# Titan_Servo_v1p01c.net
KiCad netlist of a schematic drawn in EAGLE
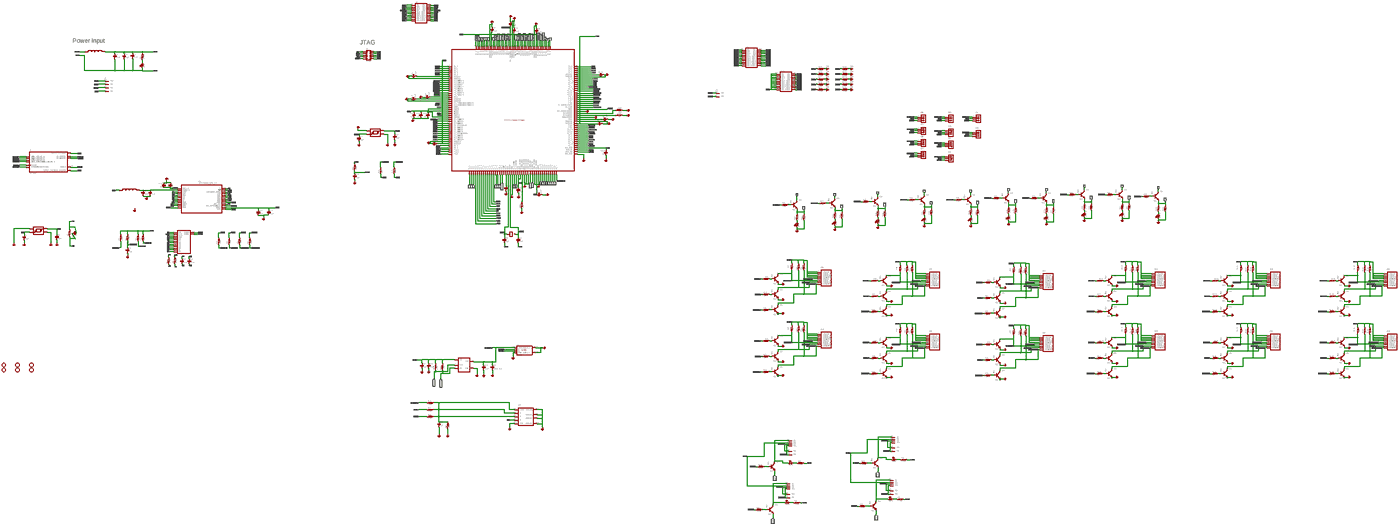
[diagram p0: schematic, sheet 1, overview]
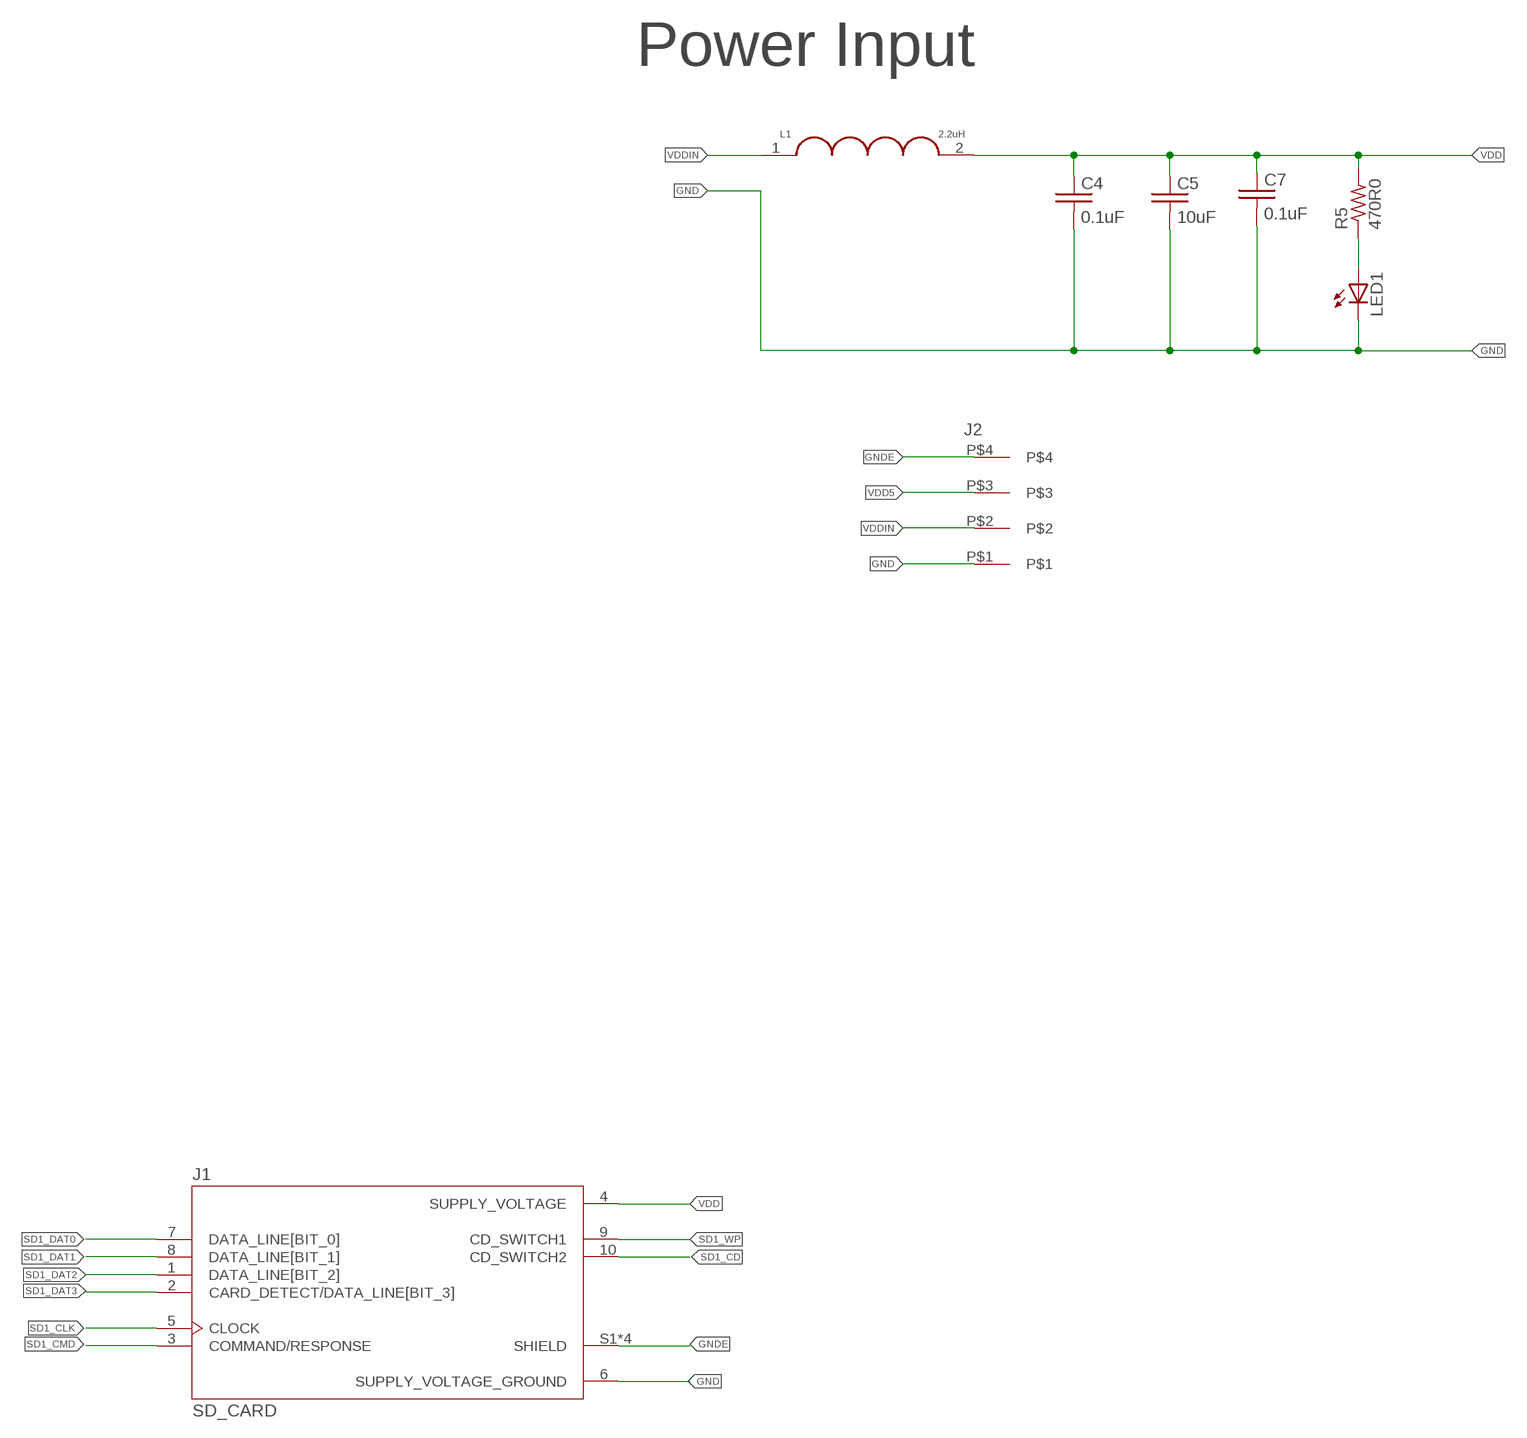
[diagram p1: schematic, sheet 1, part 1 of 9]
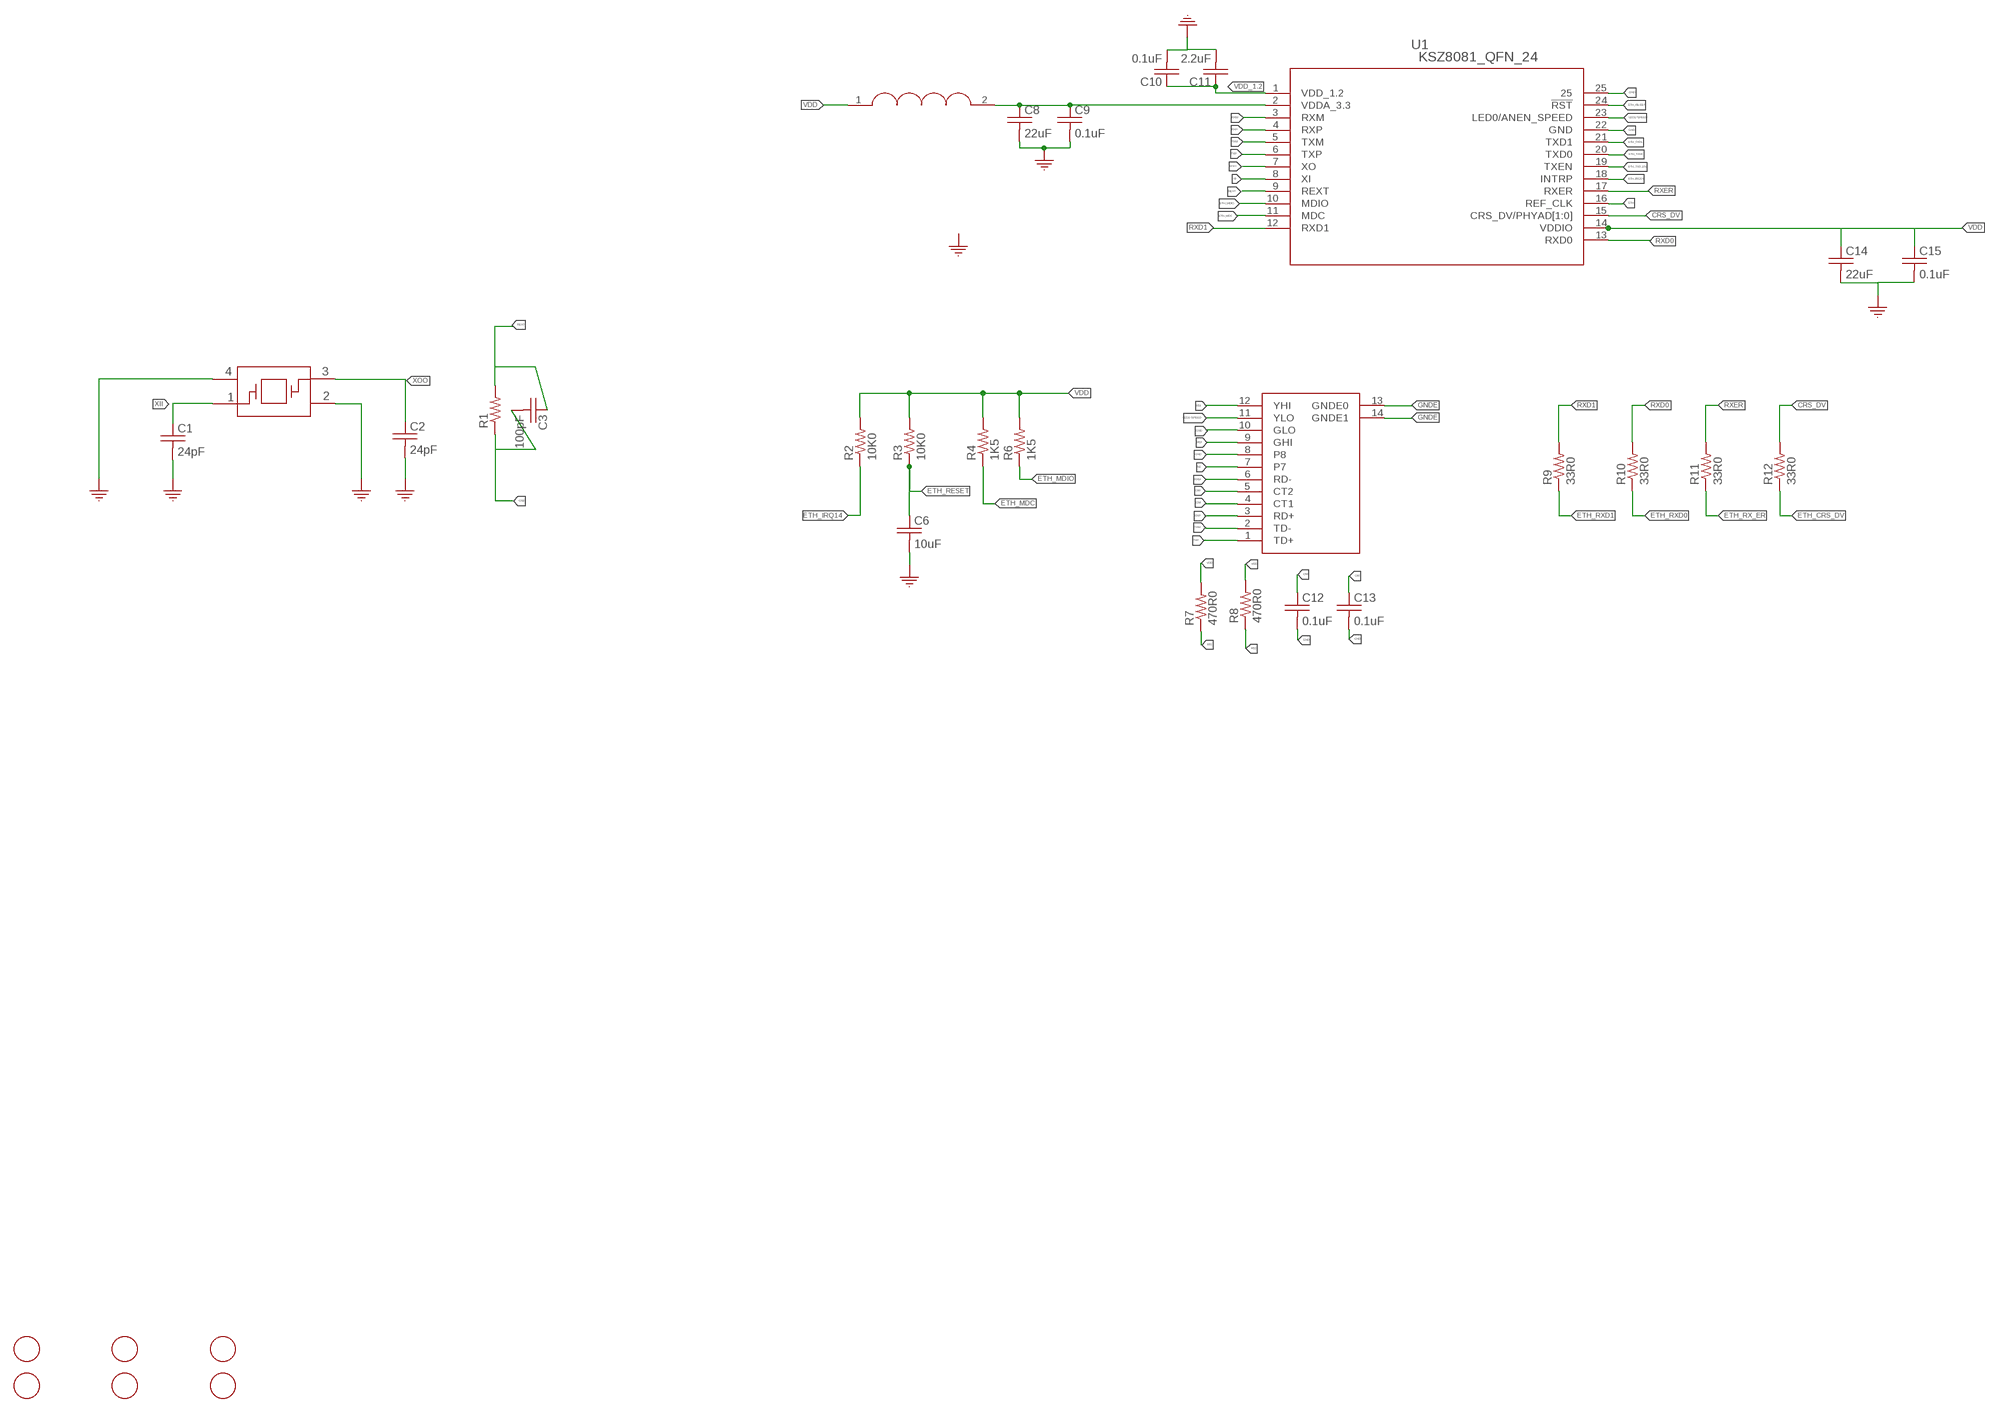
[diagram p2: schematic, sheet 1, part 2 of 9]
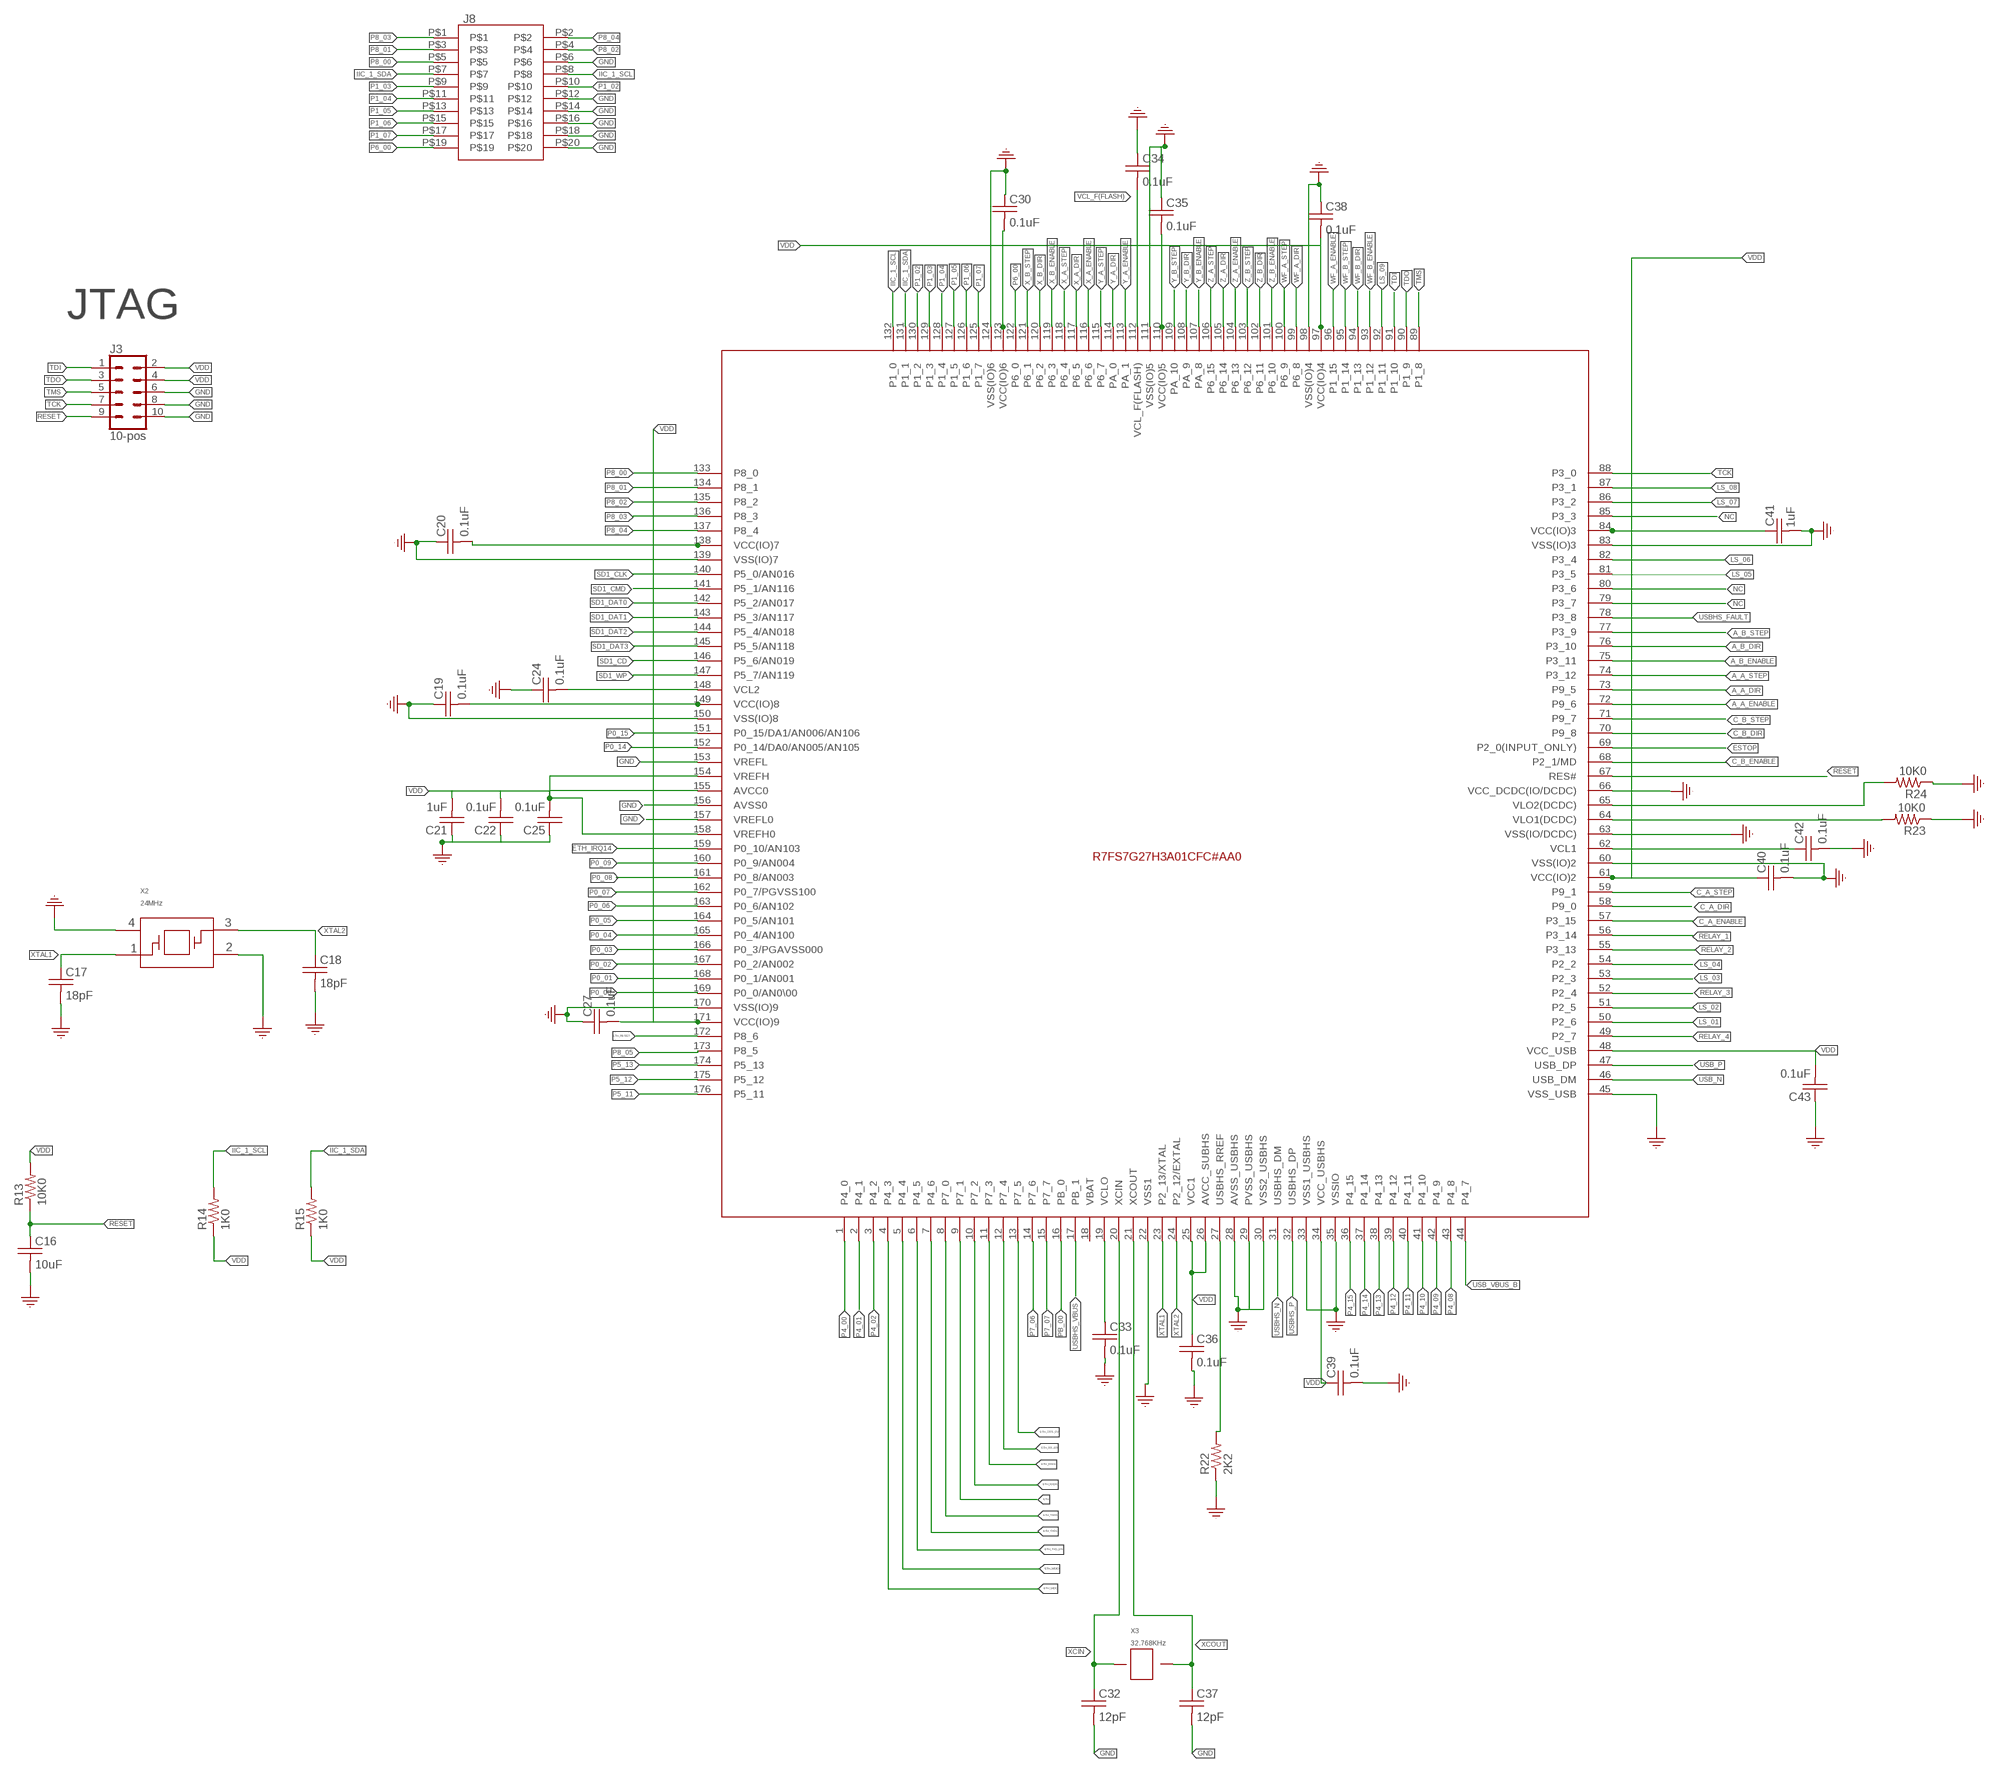
[diagram p3: schematic, sheet 1, part 3 of 9]
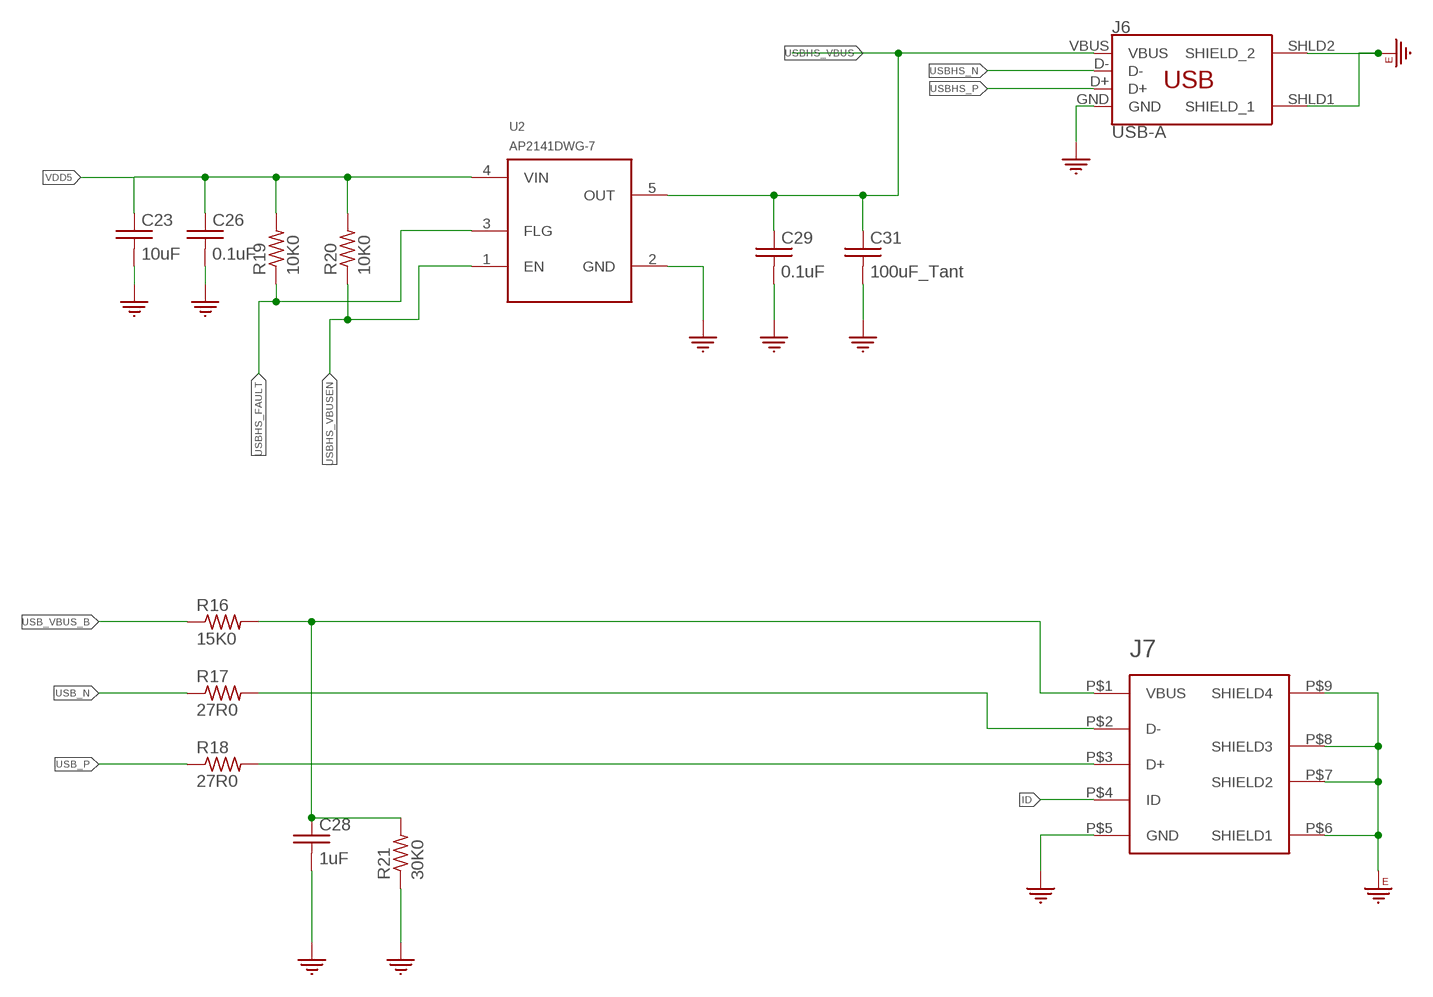
[diagram p4: schematic, sheet 1, part 4 of 9]
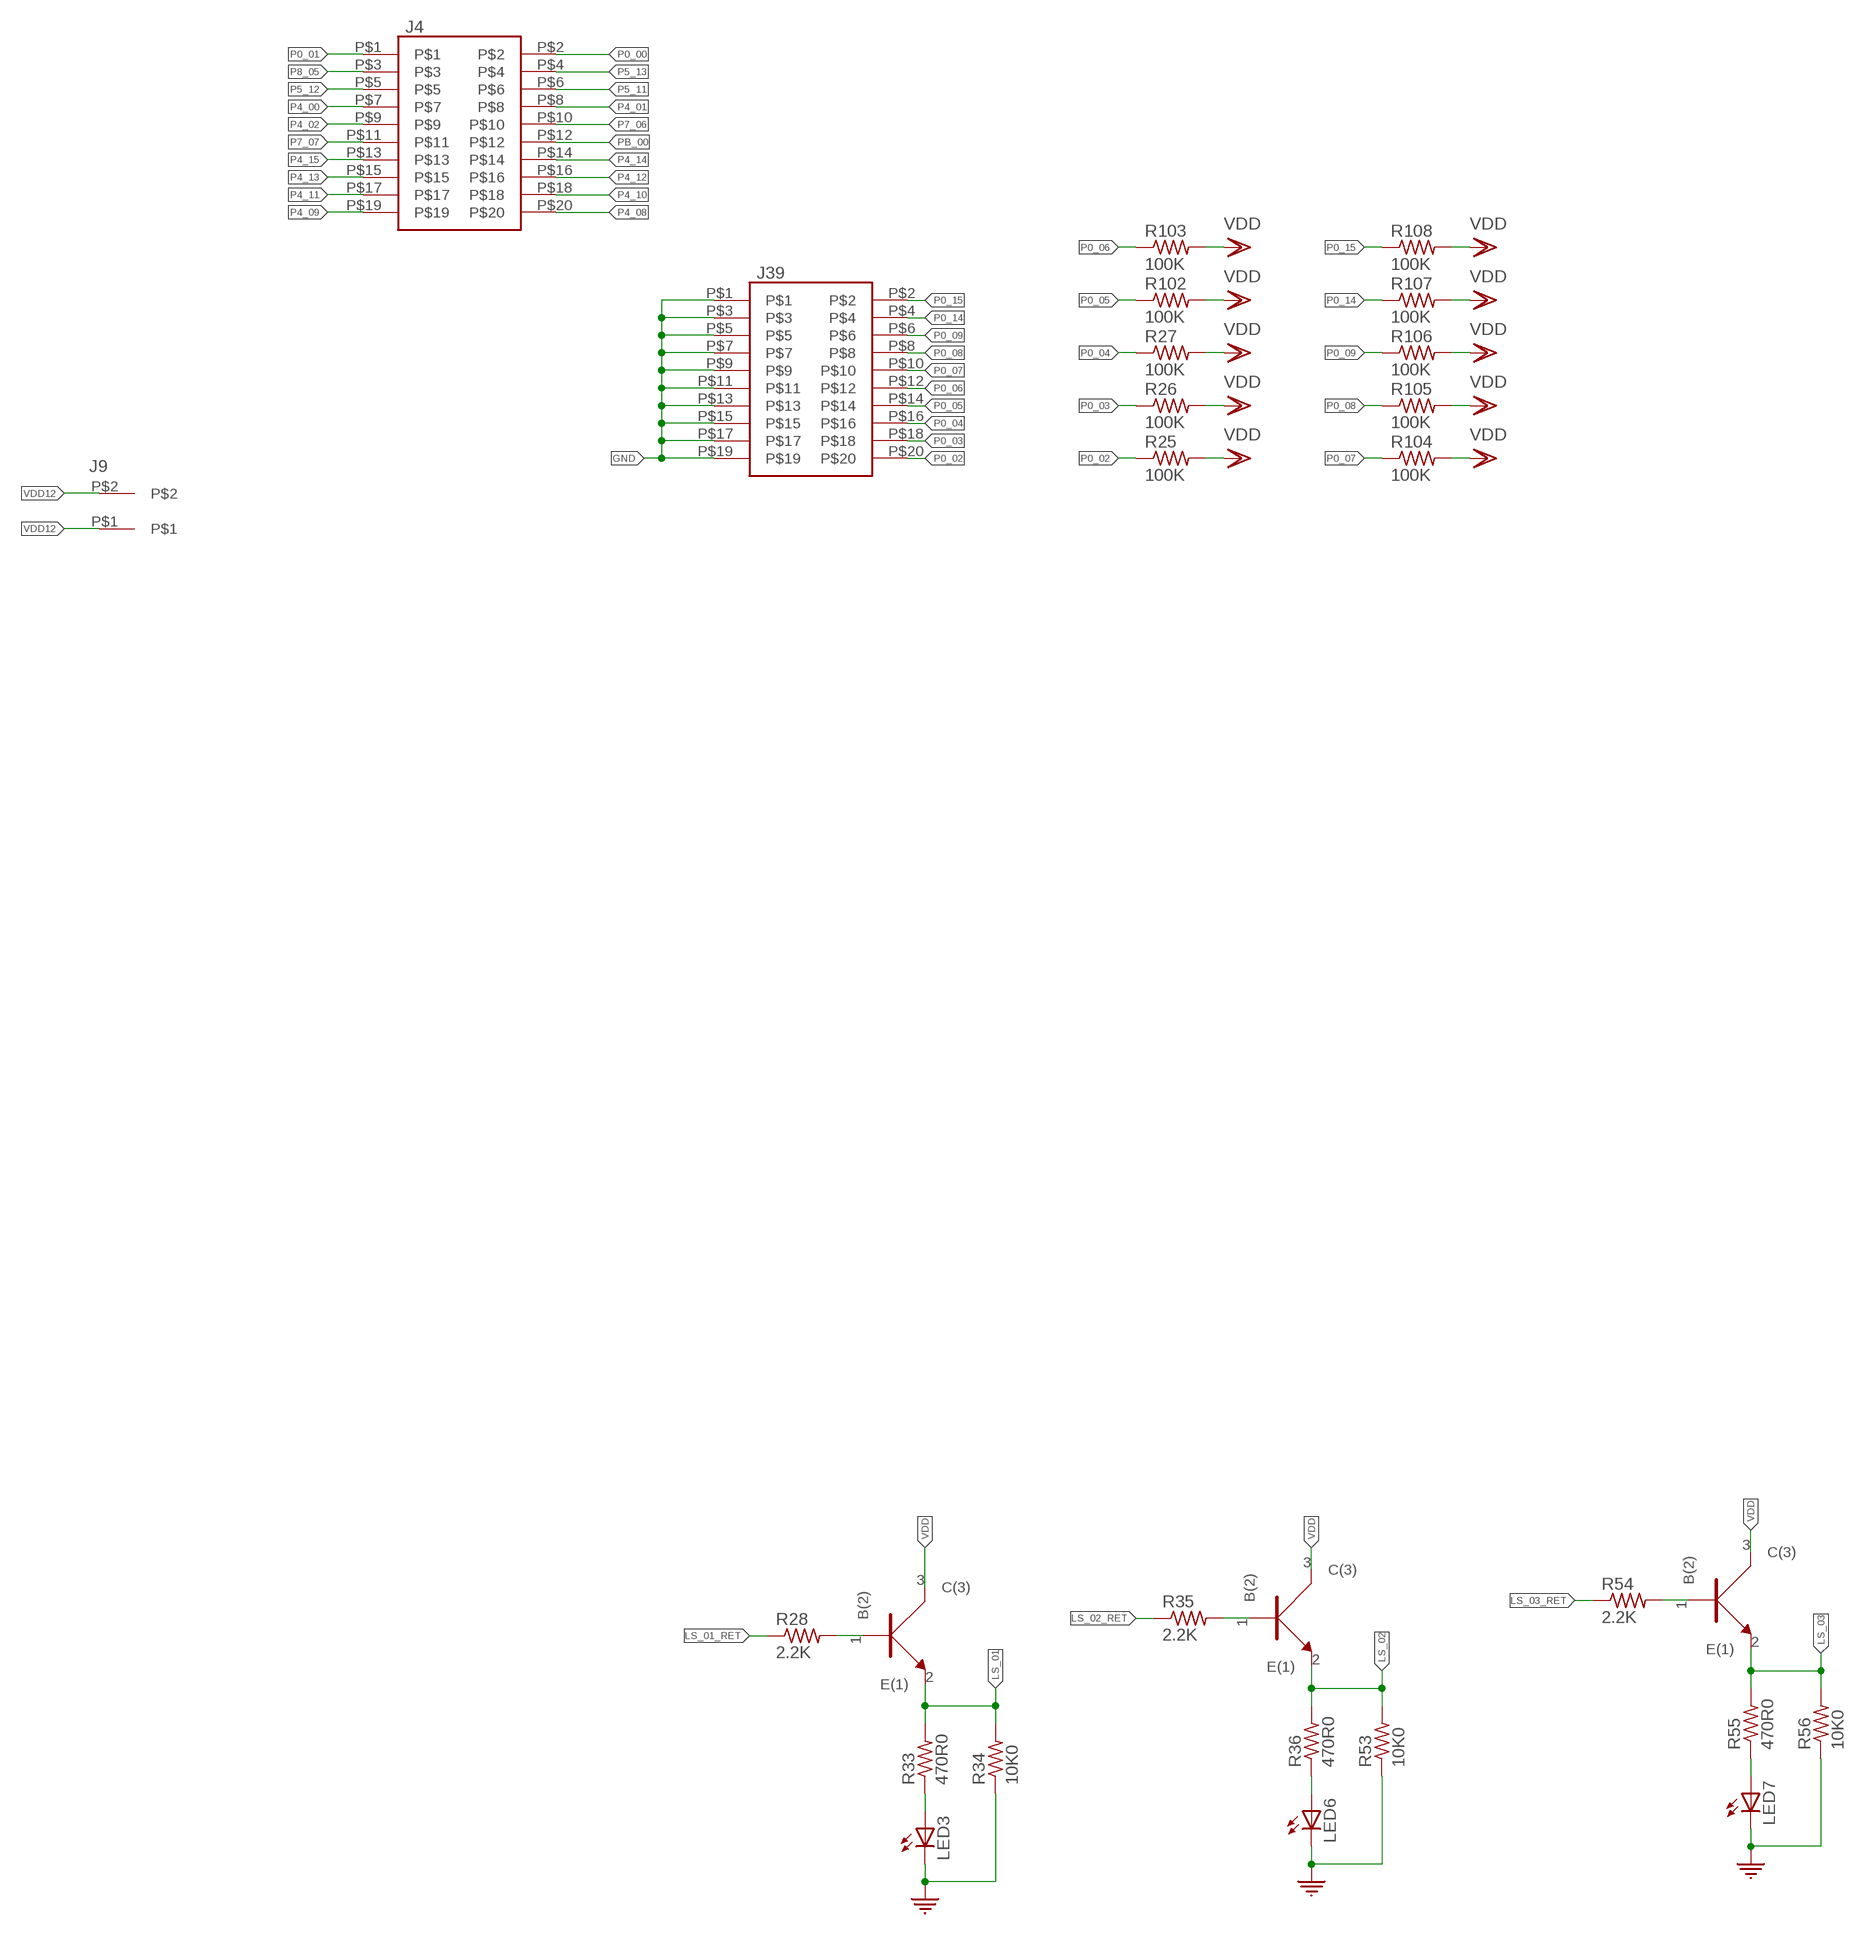
[diagram p5: schematic, sheet 1, part 5 of 9]
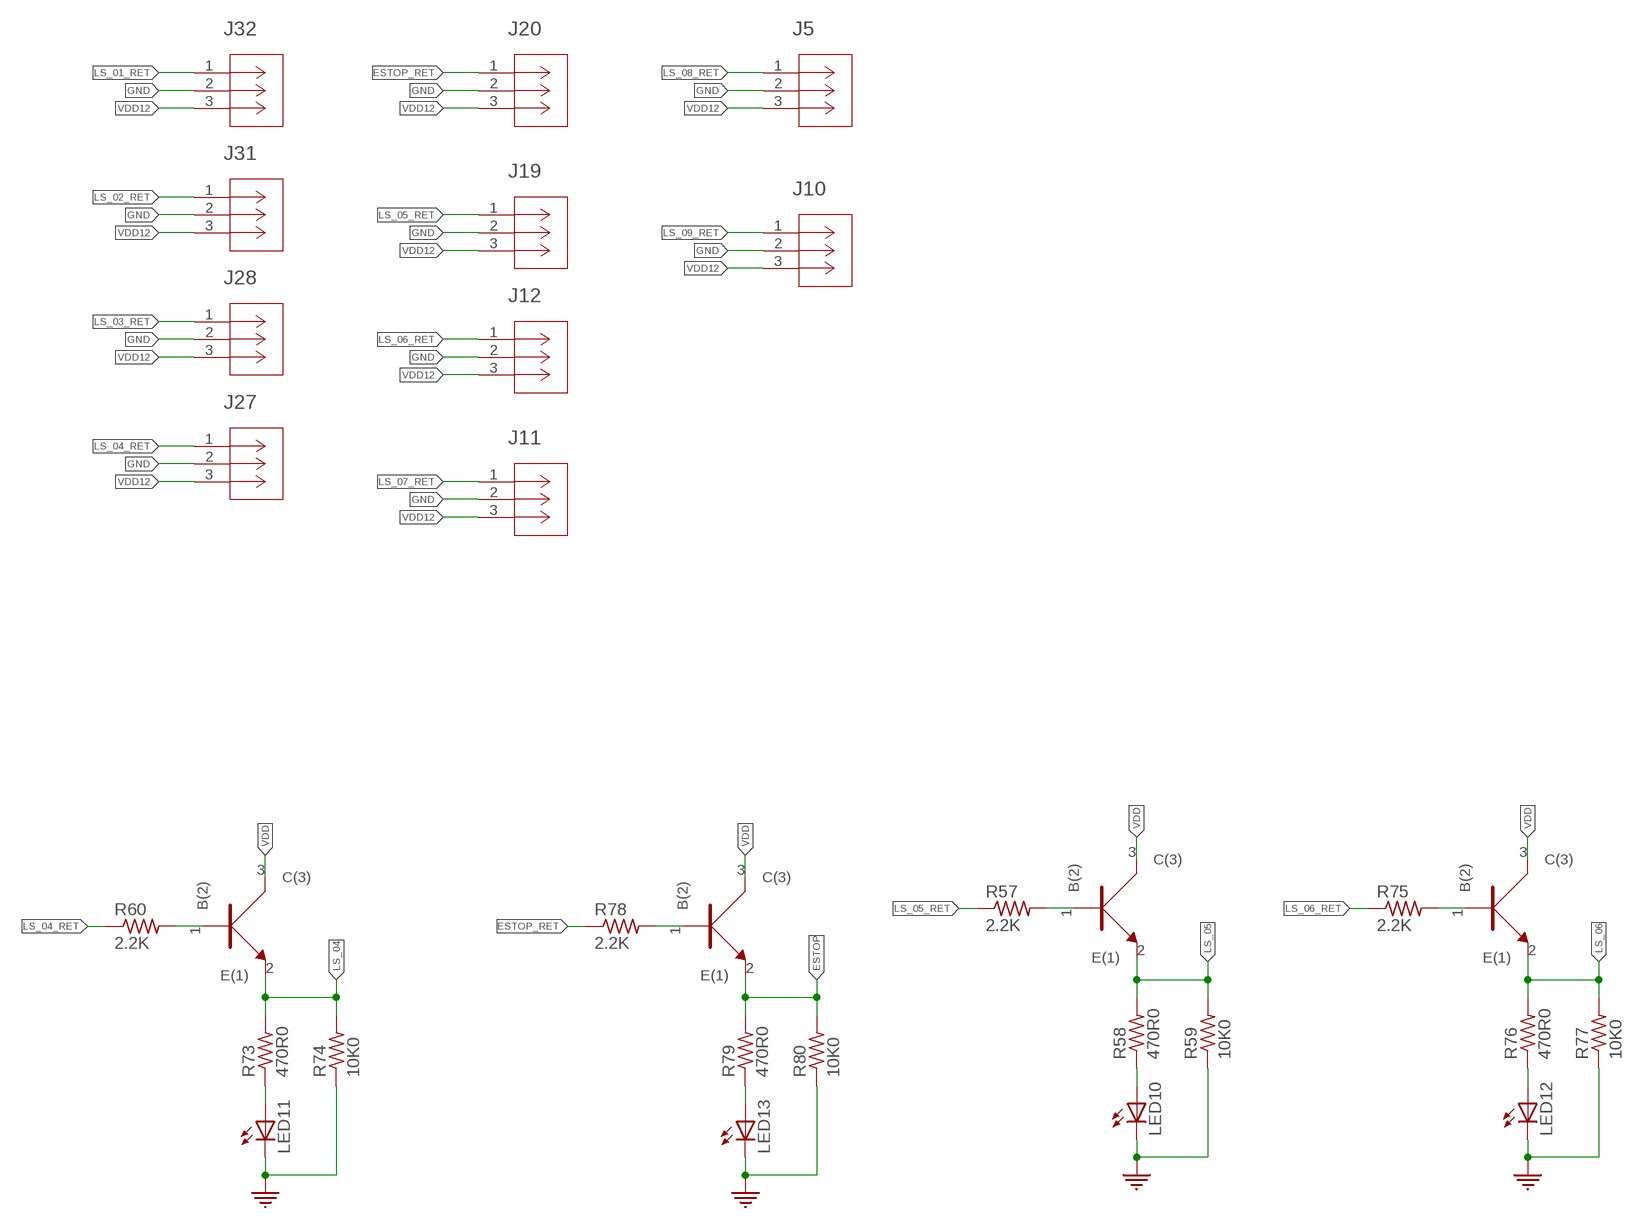
[diagram p6: schematic, sheet 1, part 6 of 9]
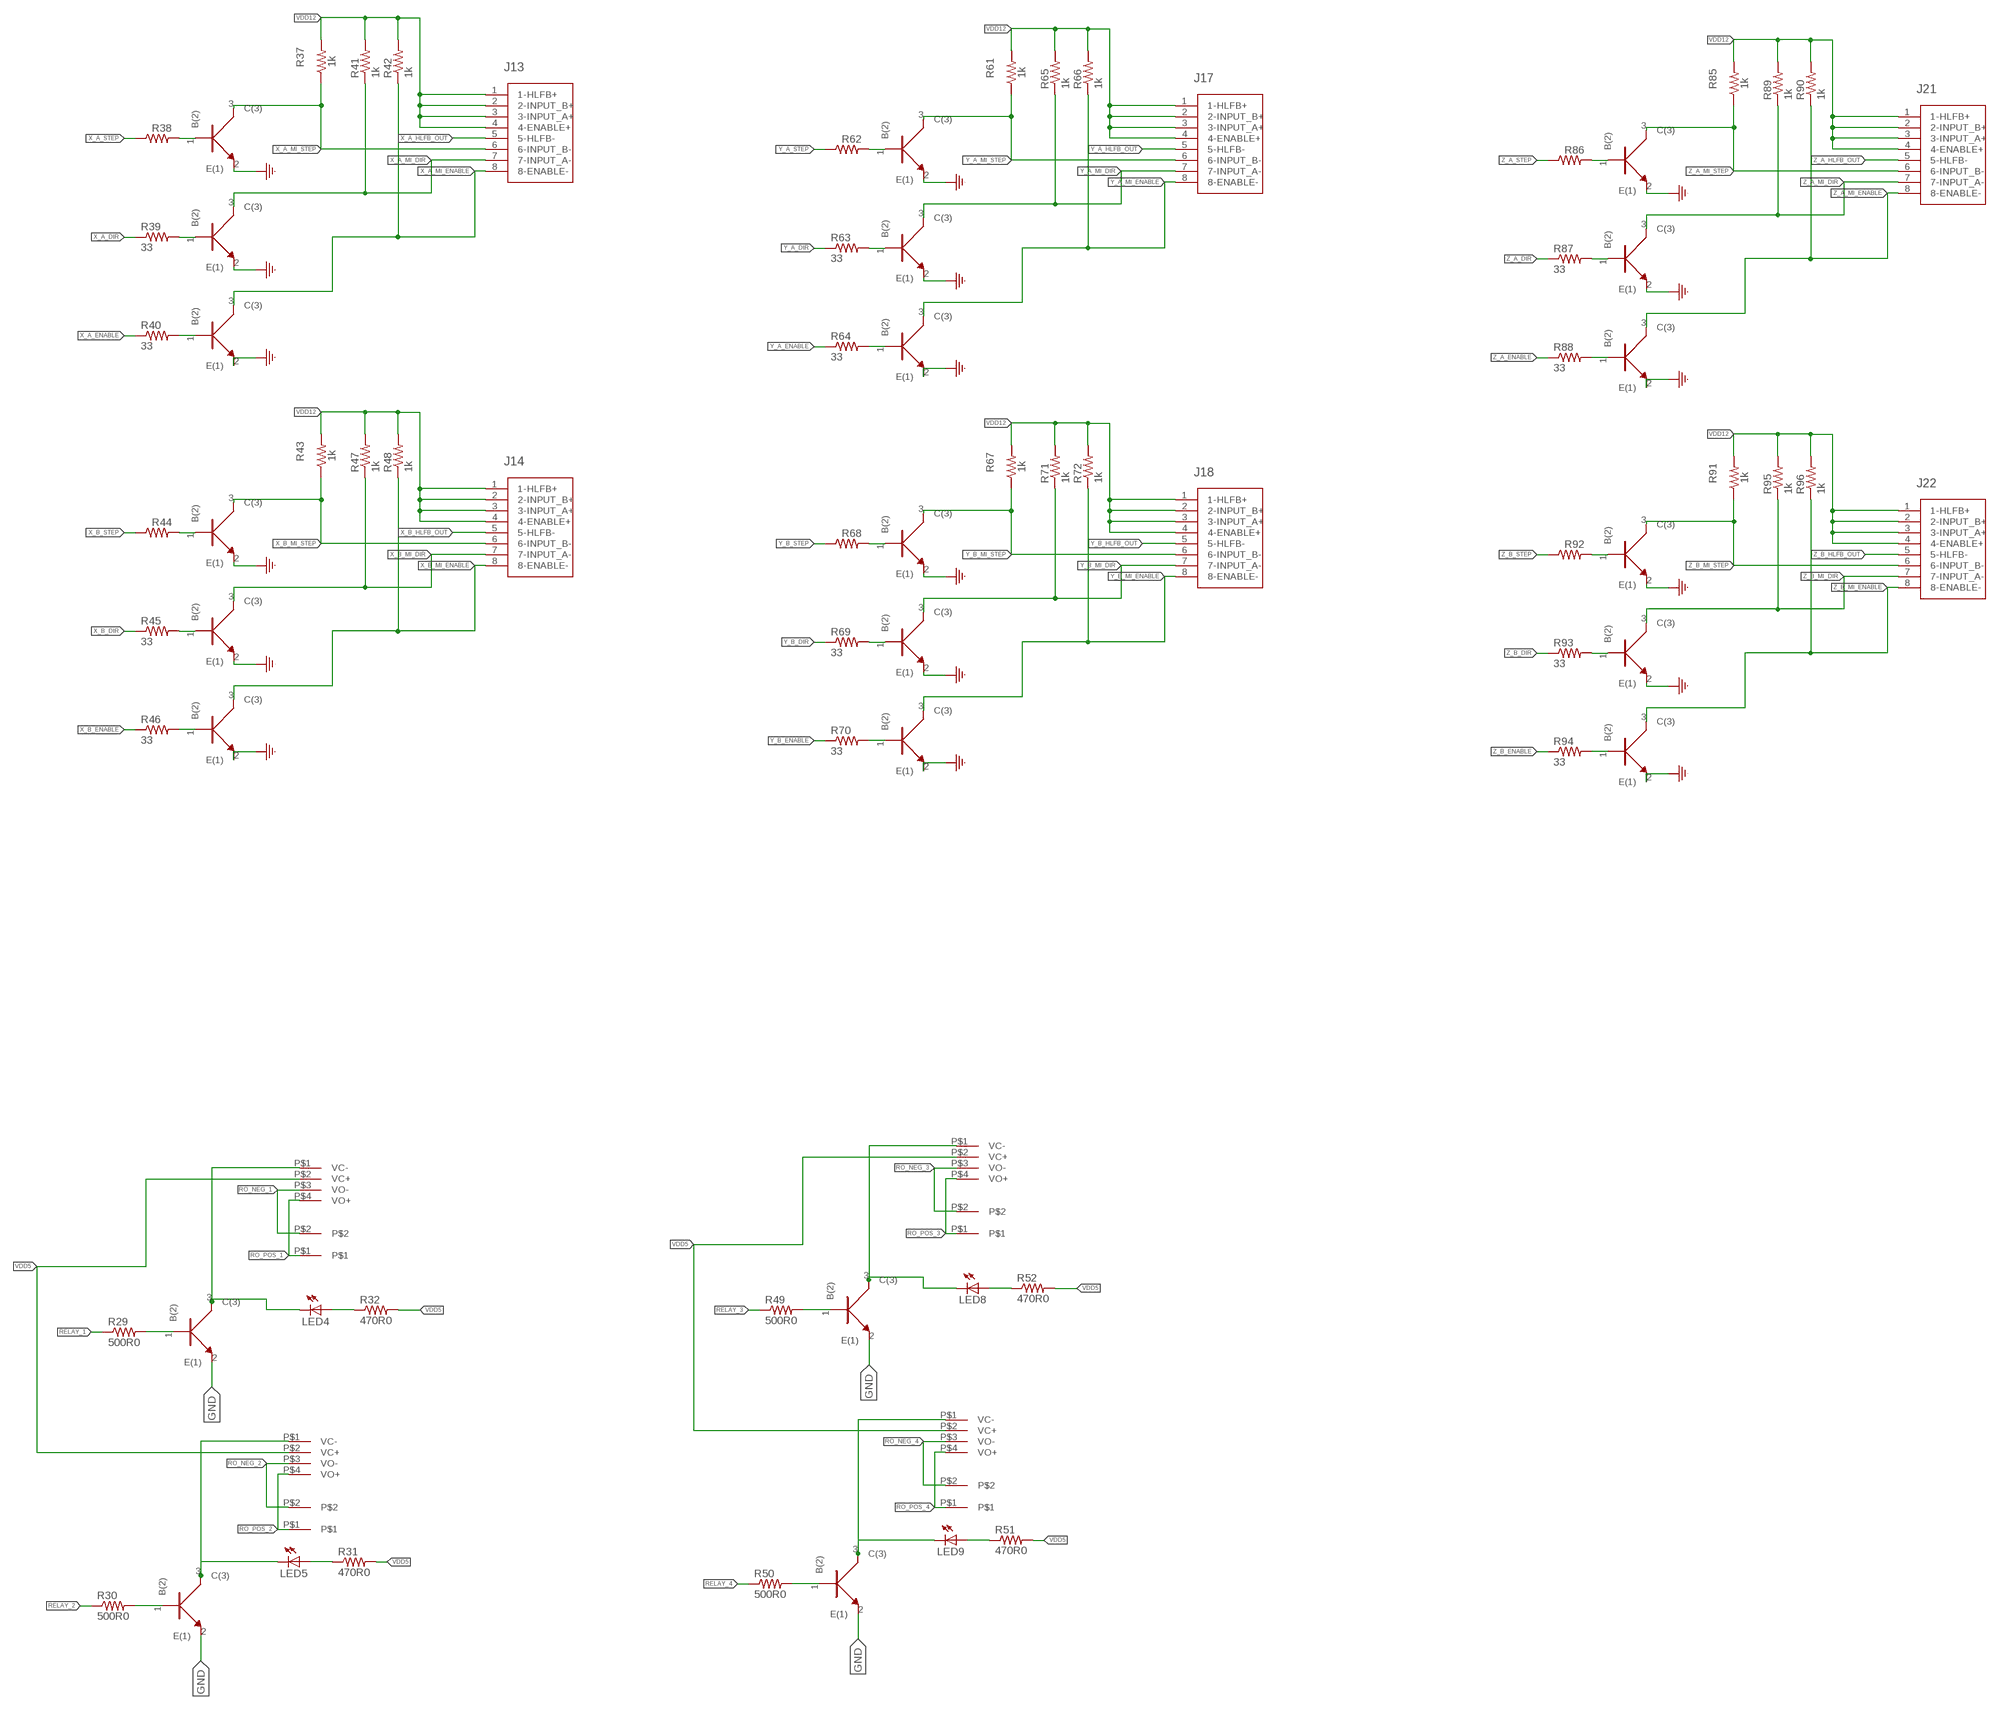
[diagram p7: schematic, sheet 1, part 7 of 9]
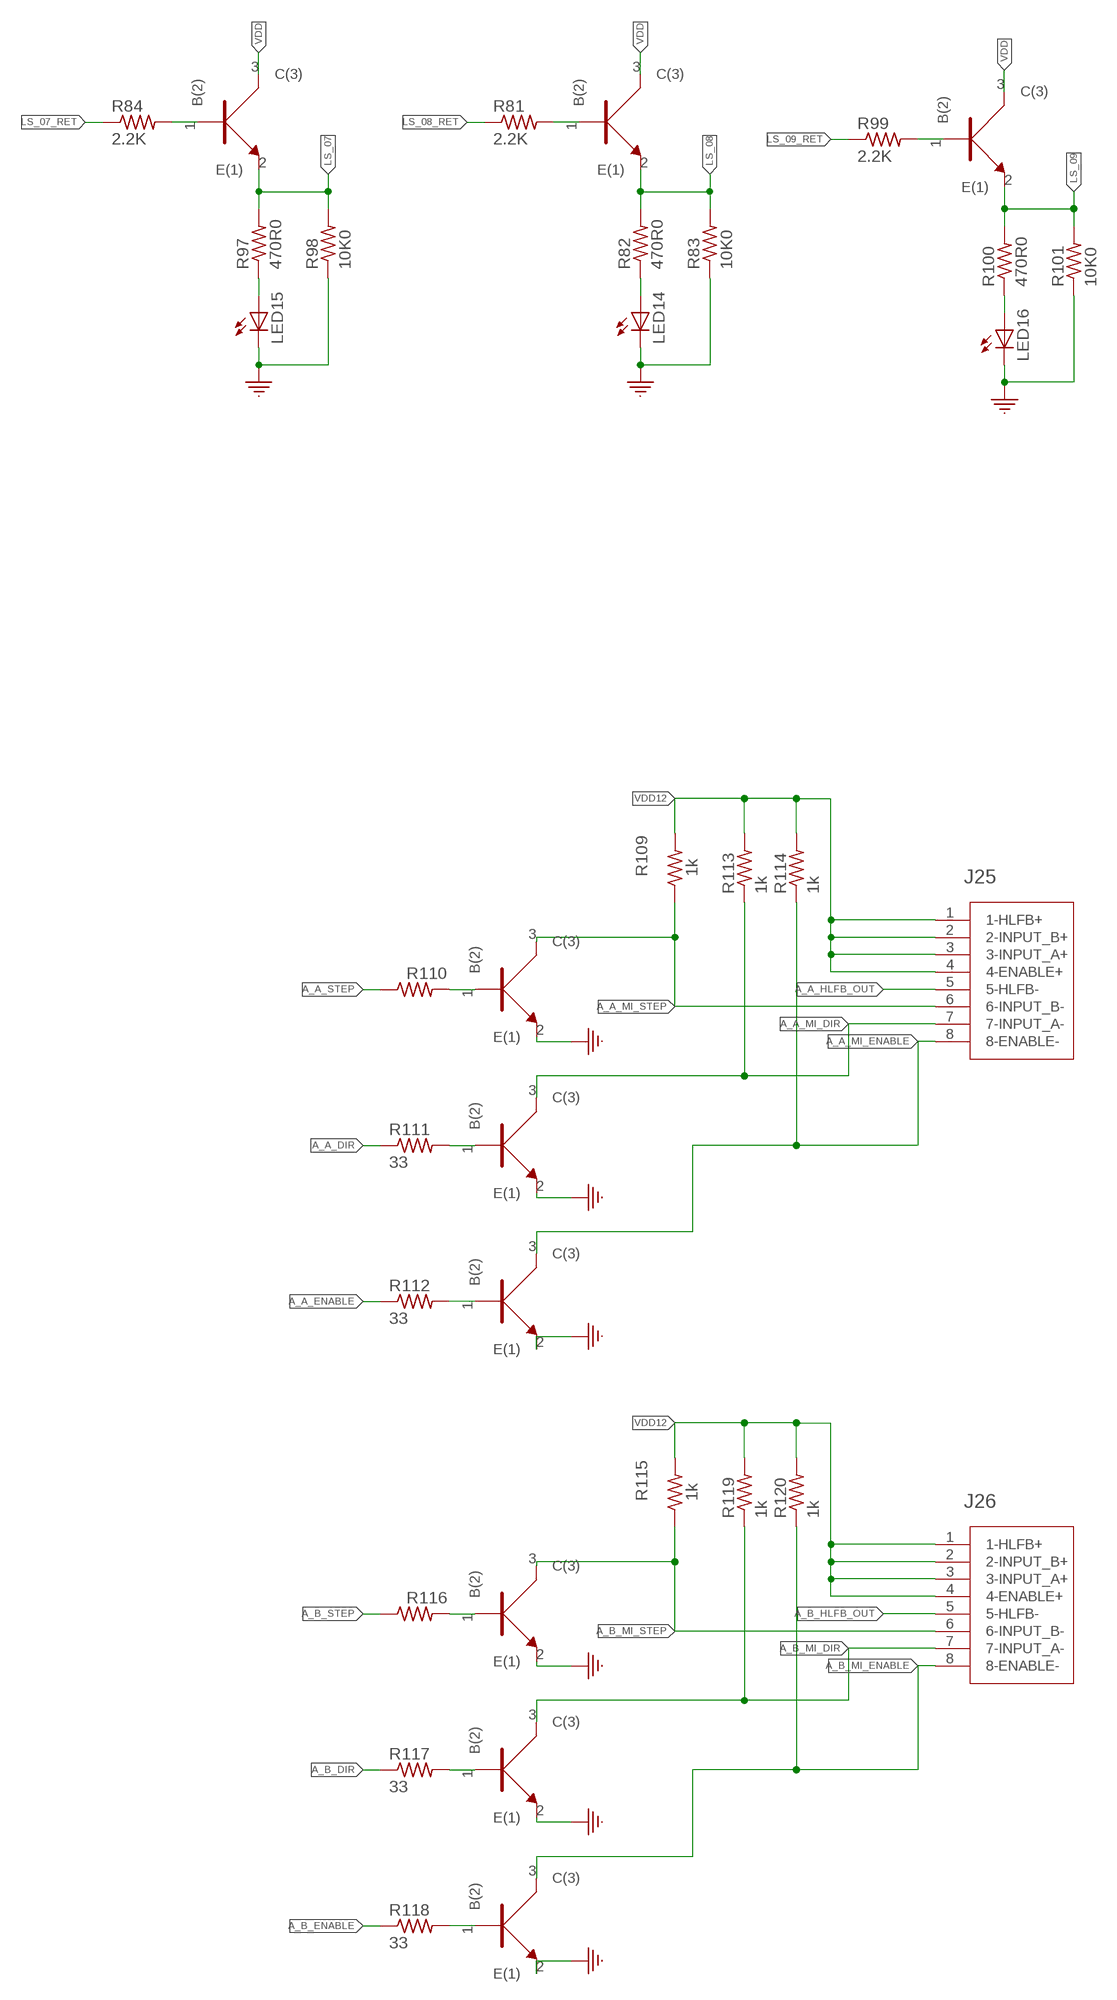
[diagram p8: schematic, sheet 1, part 8 of 9]
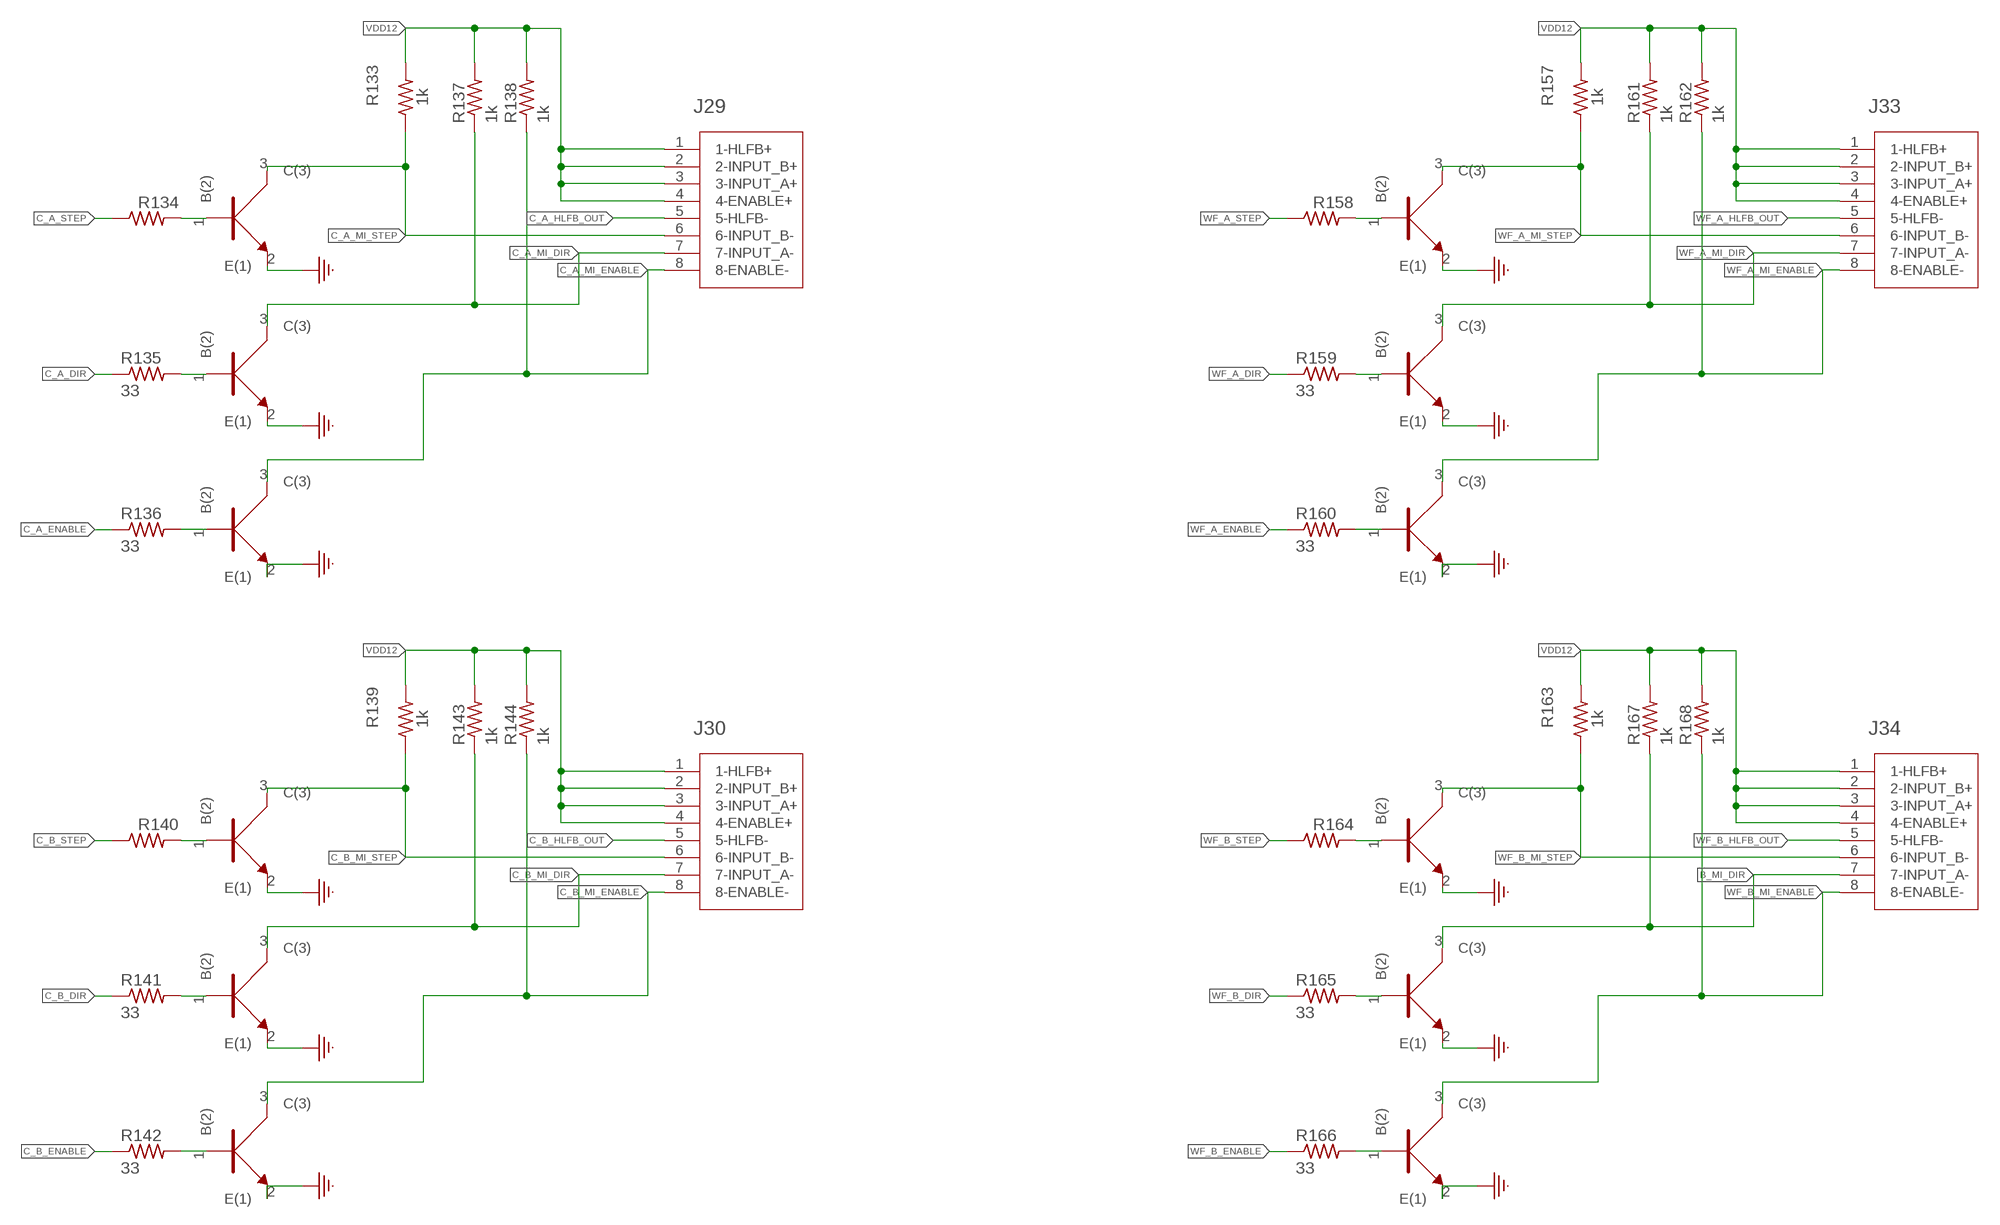
[diagram p9: schematic, sheet 1, part 9 of 9]

(export (version "E")
  (design (tool "Eeschema 10.0.6"))
  (components
    (comp (ref "AFID1")
      (value "FIDUCIAL_1MM")
      (footprint "eagle-import:FIDUCIAL_1MM")
      (libsource (lib "eagle-import") (part "FIDUCIAL_1MM"))
    )
    (comp (ref "AFID2")
      (value "FIDUCIAL_1MM")
      (footprint "eagle-import:FIDUCIAL_1MM")
      (libsource (lib "eagle-import") (part "FIDUCIAL_1MM"))
    )
    (comp (ref "AFID3")
      (value "FIDUCIAL_1MM")
      (footprint "eagle-import:FIDUCIAL_1MM")
      (libsource (lib "eagle-import") (part "FIDUCIAL_1MM"))
    )
    (comp (ref "AFID4")
      (value "FIDUCIAL_1MM")
      (footprint "eagle-import:FIDUCIAL_1MM")
      (libsource (lib "eagle-import") (part "FIDUCIAL_1MM"))
    )
    (comp (ref "AFID5")
      (value "FIDUCIAL_1MM")
      (footprint "eagle-import:FIDUCIAL_1MM")
      (libsource (lib "eagle-import") (part "FIDUCIAL_1MM"))
    )
    (comp (ref "AFID6")
      (value "FIDUCIAL_1MM")
      (footprint "eagle-import:FIDUCIAL_1MM")
      (libsource (lib "eagle-import") (part "FIDUCIAL_1MM"))
    )
    (comp (ref "C1")
      (value "24pF")
      (footprint "eagle-import:0402")
      (fields (field (name "PARTNO") "CC0402GRNPO9BN240"))
      (libsource (lib "eagle-import") (part "C_0402_24PF"))
    )
    (comp (ref "C2")
      (value "24pF")
      (footprint "eagle-import:0402")
      (fields (field (name "PARTNO") "CC0402GRNPO9BN240"))
      (libsource (lib "eagle-import") (part "C_0402_24PF"))
    )
    (comp (ref "C3")
      (value "100pF")
      (footprint "eagle-import:0402")
      (fields (field (name "PARTNO") "CL05C101JB5NNNC"))
      (libsource (lib "eagle-import") (part "C_0402_100PF"))
    )
    (comp (ref "C4")
      (value "0.1uF")
      (footprint "eagle-import:0402")
      (fields (field (name "PARTNO") "CL05F104ZO5NNNC"))
      (libsource (lib "eagle-import") (part "C_0402_0.1UF"))
    )
    (comp (ref "C5")
      (value "10uF")
      (footprint "eagle-import:0402")
      (fields (field (name "PARTNO") "CL05A106MP8NUB8"))
      (libsource (lib "eagle-import") (part "C_0402_10UF"))
    )
    (comp (ref "C6")
      (value "10uF")
      (footprint "eagle-import:0402")
      (fields (field (name "PARTNO") "CL05A106MP8NUB8"))
      (libsource (lib "eagle-import") (part "C_0402_10UF"))
    )
    (comp (ref "C7")
      (value "0.1uF")
      (footprint "eagle-import:0402")
      (fields (field (name "PARTNO") "CL05F104ZO5NNNC"))
      (libsource (lib "eagle-import") (part "C_0402_0.1UF"))
    )
    (comp (ref "C8")
      (value "22uF")
      (footprint "eagle-import:0402")
      (fields (field (name "PARTNO") "CL05A226MQ5N6J8"))
      (libsource (lib "eagle-import") (part "C_0402_22UF"))
    )
    (comp (ref "C9")
      (value "0.1uF")
      (footprint "eagle-import:0402")
      (fields (field (name "PARTNO") "CL05F104ZO5NNNC"))
      (libsource (lib "eagle-import") (part "C_0402_0.1UF"))
    )
    (comp (ref "C10")
      (value "0.1uF")
      (footprint "eagle-import:0402")
      (fields (field (name "PARTNO") "CL05F104ZO5NNNC"))
      (libsource (lib "eagle-import") (part "C_0402_0.1UF"))
    )
    (comp (ref "C11")
      (value "2.2uF")
      (footprint "eagle-import:0402")
      (fields (field (name "PARTNO") "GRM155C81C225ME15D"))
      (libsource (lib "eagle-import") (part "C_0402_2.2UF"))
    )
    (comp (ref "C12")
      (value "0.1uF")
      (footprint "eagle-import:0402")
      (fields (field (name "PARTNO") "CL05F104ZO5NNNC"))
      (libsource (lib "eagle-import") (part "C_0402_0.1UF"))
    )
    (comp (ref "C13")
      (value "0.1uF")
      (footprint "eagle-import:0402")
      (fields (field (name "PARTNO") "CL05F104ZO5NNNC"))
      (libsource (lib "eagle-import") (part "C_0402_0.1UF"))
    )
    (comp (ref "C14")
      (value "22uF")
      (footprint "eagle-import:0402")
      (fields (field (name "PARTNO") "CL05A226MQ5N6J8"))
      (libsource (lib "eagle-import") (part "C_0402_22UF"))
    )
    (comp (ref "C15")
      (value "0.1uF")
      (footprint "eagle-import:0402")
      (fields (field (name "PARTNO") "CL05F104ZO5NNNC"))
      (libsource (lib "eagle-import") (part "C_0402_0.1UF"))
    )
    (comp (ref "C16")
      (value "10uF")
      (footprint "eagle-import:0402")
      (fields (field (name "PARTNO") "CL05A106MP8NUB8"))
      (libsource (lib "eagle-import") (part "C_0402_10UF"))
    )
    (comp (ref "C17")
      (value "18pF")
      (footprint "eagle-import:0402")
      (fields (field (name "PARTNO") "UMK105CG180JV-F"))
      (libsource (lib "eagle-import") (part "C_0402_18PF"))
    )
    (comp (ref "C18")
      (value "18pF")
      (footprint "eagle-import:0402")
      (fields (field (name "PARTNO") "UMK105CG180JV-F"))
      (libsource (lib "eagle-import") (part "C_0402_18PF"))
    )
    (comp (ref "C19")
      (value "0.1uF")
      (footprint "eagle-import:0402")
      (fields (field (name "PARTNO") "CL05F104ZO5NNNC"))
      (libsource (lib "eagle-import") (part "C_0402_0.1UF"))
    )
    (comp (ref "C20")
      (value "0.1uF")
      (footprint "eagle-import:0402")
      (fields (field (name "PARTNO") "CL05F104ZO5NNNC"))
      (libsource (lib "eagle-import") (part "C_0402_0.1UF"))
    )
    (comp (ref "C21")
      (value "1uF")
      (footprint "eagle-import:0402")
      (fields (field (name "PARTNO") "CL05A105KO5NNNC"))
      (libsource (lib "eagle-import") (part "C_0402_1UF"))
    )
    (comp (ref "C22")
      (value "0.1uF")
      (footprint "eagle-import:0402")
      (fields (field (name "PARTNO") "CL05F104ZO5NNNC"))
      (libsource (lib "eagle-import") (part "C_0402_0.1UF"))
    )
    (comp (ref "C23")
      (value "10uF")
      (footprint "eagle-import:0402")
      (fields (field (name "PARTNO") "CL05A106MP8NUB8"))
      (libsource (lib "eagle-import") (part "C_0402_10UF"))
    )
    (comp (ref "C24")
      (value "0.1uF")
      (footprint "eagle-import:0402")
      (fields (field (name "PARTNO") "CL05F104ZO5NNNC"))
      (libsource (lib "eagle-import") (part "C_0402_0.1UF"))
    )
    (comp (ref "C25")
      (value "0.1uF")
      (footprint "eagle-import:0402")
      (fields (field (name "PARTNO") "CL05F104ZO5NNNC"))
      (libsource (lib "eagle-import") (part "C_0402_0.1UF"))
    )
    (comp (ref "C26")
      (value "0.1uF")
      (footprint "eagle-import:0402")
      (fields (field (name "PARTNO") "CL05F104ZO5NNNC"))
      (libsource (lib "eagle-import") (part "C_0402_0.1UF"))
    )
    (comp (ref "C27")
      (value "0.1uF")
      (footprint "eagle-import:0402")
      (fields (field (name "PARTNO") "CL05F104ZO5NNNC"))
      (libsource (lib "eagle-import") (part "C_0402_0.1UF"))
    )
    (comp (ref "C28")
      (value "1uF")
      (footprint "eagle-import:0402")
      (fields (field (name "PARTNO") "CL05A105KO5NNNC"))
      (libsource (lib "eagle-import") (part "C_0402_1UF"))
    )
    (comp (ref "C29")
      (value "0.1uF")
      (footprint "eagle-import:0402")
      (fields (field (name "PARTNO") "CL05F104ZO5NNNC"))
      (libsource (lib "eagle-import") (part "C_0402_0.1UF"))
    )
    (comp (ref "C30")
      (value "0.1uF")
      (footprint "eagle-import:0402")
      (fields (field (name "PARTNO") "CL05F104ZO5NNNC"))
      (libsource (lib "eagle-import") (part "C_0402_0.1UF"))
    )
    (comp (ref "C31")
      (value "100uF_Tant")
      (footprint "eagle-import:C1210")
      (fields (field (name "PARTNO") "TLJT107M010R0900"))
      (libsource (lib "eagle-import") (part "C_1210_100UF_TANT"))
    )
    (comp (ref "C32")
      (value "12pF")
      (footprint "eagle-import:0402")
      (fields (field (name "PARTNO") "CL05C120JB5NNNC"))
      (libsource (lib "eagle-import") (part "C_0402_12PF"))
    )
    (comp (ref "C33")
      (value "0.1uF")
      (footprint "eagle-import:0402")
      (fields (field (name "PARTNO") "CL05F104ZO5NNNC"))
      (libsource (lib "eagle-import") (part "C_0402_0.1UF"))
    )
    (comp (ref "C34")
      (value "0.1uF")
      (footprint "eagle-import:0402")
      (fields (field (name "PARTNO") "CL05F104ZO5NNNC"))
      (libsource (lib "eagle-import") (part "C_0402_0.1UF"))
    )
    (comp (ref "C35")
      (value "0.1uF")
      (footprint "eagle-import:0402")
      (fields (field (name "PARTNO") "CL05F104ZO5NNNC"))
      (libsource (lib "eagle-import") (part "C_0402_0.1UF"))
    )
    (comp (ref "C36")
      (value "0.1uF")
      (footprint "eagle-import:0402")
      (fields (field (name "PARTNO") "CL05F104ZO5NNNC"))
      (libsource (lib "eagle-import") (part "C_0402_0.1UF"))
    )
    (comp (ref "C37")
      (value "12pF")
      (footprint "eagle-import:0402")
      (fields (field (name "PARTNO") "CL05C120JB5NNNC"))
      (libsource (lib "eagle-import") (part "C_0402_12PF"))
    )
    (comp (ref "C38")
      (value "0.1uF")
      (footprint "eagle-import:0402")
      (fields (field (name "PARTNO") "CL05F104ZO5NNNC"))
      (libsource (lib "eagle-import") (part "C_0402_0.1UF"))
    )
    (comp (ref "C39")
      (value "0.1uF")
      (footprint "eagle-import:0402")
      (fields (field (name "PARTNO") "CL05F104ZO5NNNC"))
      (libsource (lib "eagle-import") (part "C_0402_0.1UF"))
    )
    (comp (ref "C40")
      (value "0.1uF")
      (footprint "eagle-import:0402")
      (fields (field (name "PARTNO") "CL05F104ZO5NNNC"))
      (libsource (lib "eagle-import") (part "C_0402_0.1UF"))
    )
    (comp (ref "C41")
      (value "1uF")
      (footprint "eagle-import:0402")
      (fields (field (name "PARTNO") "CL05A105KO5NNNC"))
      (libsource (lib "eagle-import") (part "C_0402_1UF"))
    )
    (comp (ref "C42")
      (value "0.1uF")
      (footprint "eagle-import:0402")
      (fields (field (name "PARTNO") "CL05F104ZO5NNNC"))
      (libsource (lib "eagle-import") (part "C_0402_0.1UF"))
    )
    (comp (ref "C43")
      (value "0.1uF")
      (footprint "eagle-import:0402")
      (fields (field (name "PARTNO") "CL05F104ZO5NNNC"))
      (libsource (lib "eagle-import") (part "C_0402_0.1UF"))
    )
    (comp (ref "FB1")
      (value "FB2_603")
      (footprint "eagle-import:0603")
      (fields (field (name "PARTNO") "BLM18PG121SN1D"))
      (libsource (lib "eagle-import") (part "FB_0603_120_OHM0603"))
    )
    (comp (ref "J1")
      (value "SD_CARD")
      (footprint "eagle-import:SD_CARD")
      (fields (field (name "MF") "Amphenol ICC") (field (name "PARTNO") "114-00841-68"))
      (libsource (lib "eagle-import") (part "SD_CARD_1140084168"))
    )
    (comp (ref "J2")
      (value "4-pos")
      (footprint "eagle-import:1X4_3.81MM_PITCH")
      (fields (field (name "PARTNO") "691322310004"))
      (libsource (lib "eagle-import") (part "3.81MM_1_X_4_RT_ANGLE_PLUG_HEADER"))
    )
    (comp (ref "J3")
      (value "10-pos")
      (footprint "eagle-import:2X5")
      (fields (field (name "PARTNO") "PH2RA-10-UA"))
      (libsource (lib "eagle-import") (part "CONN_05X2_RAPTH"))
    )
    (comp (ref "J4")
      (value "20-pos")
      (footprint "eagle-import:2_X_10_.1_INCH")
      (fields (field (name "PARTNO") "67996-420HLF"))
      (libsource (lib "eagle-import") (part "2_X_10_HEADER_GENERIC"))
    )
    (comp (ref "J5")
      (value "CONN_530470310_PICOBLADE_X_3")
      (footprint "eagle-import:CON_530470310_MOL")
      (fields
        (field (name "MANUFACTURER_PART_NUMBER") "530470310")
        (field (name "COPYRIGHT") "Copyright (C) 2022 Ultra Librarian. All rights reserved.")
      )
      (libsource (lib "eagle-import") (part "CONN_530470310_PICOBLADE_X_3"))
    )
    (comp (ref "J6")
      (value "USB-A")
      (footprint "eagle-import:USB_A_SMT")
      (fields (field (name "PARTNO") "87583-3010RPALF"))
      (libsource (lib "eagle-import") (part "USB_A"))
    )
    (comp (ref "J7")
      (value "USB-B-Micro")
      (footprint "eagle-import:USB_MICRO-B")
      (fields (field (name "PARTNO") "10118192-0002LF"))
      (libsource (lib "eagle-import") (part "USB_MICRO-B"))
    )
    (comp (ref "J8")
      (value "2_X_10_HEADER_GENERIC")
      (footprint "eagle-import:2_X_10_.1_INCH")
      (fields (field (name "PARTNO") "67996-420HLF"))
      (libsource (lib "eagle-import") (part "2_X_10_HEADER_GENERIC"))
    )
    (comp (ref "J9")
      (value "2-pos")
      (footprint "eagle-import:2_3.81MM_PITCH")
      (fields (field (name "PARTNO") "691322310002"))
      (libsource (lib "eagle-import") (part "3.81MM_1_X_2_RT_ANGLE_PLUG_HEADER"))
    )
    (comp (ref "J10")
      (value "CONN_530470310_PICOBLADE_X_3")
      (footprint "eagle-import:CON_530470310_MOL")
      (fields
        (field (name "MANUFACTURER_PART_NUMBER") "530470310")
        (field (name "COPYRIGHT") "Copyright (C) 2022 Ultra Librarian. All rights reserved.")
      )
      (libsource (lib "eagle-import") (part "CONN_530470310_PICOBLADE_X_3"))
    )
    (comp (ref "J11")
      (value "CONN_530470310_PICOBLADE_X_3")
      (footprint "eagle-import:CON_530470310_MOL")
      (fields
        (field (name "MANUFACTURER_PART_NUMBER") "530470310")
        (field (name "COPYRIGHT") "Copyright (C) 2022 Ultra Librarian. All rights reserved.")
      )
      (libsource (lib "eagle-import") (part "CONN_530470310_PICOBLADE_X_3"))
    )
    (comp (ref "J12")
      (value "CONN_530470310_PICOBLADE_X_3")
      (footprint "eagle-import:CON_530470310_MOL")
      (fields
        (field (name "MANUFACTURER_PART_NUMBER") "530470310")
        (field (name "COPYRIGHT") "Copyright (C) 2022 Ultra Librarian. All rights reserved.")
      )
      (libsource (lib "eagle-import") (part "CONN_530470310_PICOBLADE_X_3"))
    )
    (comp (ref "J13")
      (value "TEKNIC_MOTOR_8PIN")
      (footprint "eagle-import:CON_39281083")
      (fields
        (field (name "MANUFACTURER_PART_NUMBER") "39281083")
        (field (name "COPYRIGHT") "Copyright (C) 2022 Ultra Librarian. All rights reserved.")
      )
      (libsource (lib "eagle-import") (part "TEKNIC_MOTOR_8PIN"))
    )
    (comp (ref "J14")
      (value "TEKNIC_MOTOR_8PIN")
      (footprint "eagle-import:CON_39281083")
      (fields
        (field (name "MANUFACTURER_PART_NUMBER") "39281083")
        (field (name "COPYRIGHT") "Copyright (C) 2022 Ultra Librarian. All rights reserved.")
      )
      (libsource (lib "eagle-import") (part "TEKNIC_MOTOR_8PIN"))
    )
    (comp (ref "J15")
      (value "2-pos")
      (footprint "eagle-import:2_3.81MM_PITCH")
      (fields (field (name "PARTNO") "691322310002"))
      (libsource (lib "eagle-import") (part "3.81MM_1_X_2_RT_ANGLE_PLUG_HEADER"))
    )
    (comp (ref "J16")
      (value "2-pos")
      (footprint "eagle-import:2_3.81MM_PITCH")
      (fields (field (name "PARTNO") "691322310002"))
      (libsource (lib "eagle-import") (part "3.81MM_1_X_2_RT_ANGLE_PLUG_HEADER"))
    )
    (comp (ref "J17")
      (value "TEKNIC_MOTOR_8PIN")
      (footprint "eagle-import:CON_39281083")
      (fields
        (field (name "MANUFACTURER_PART_NUMBER") "39281083")
        (field (name "COPYRIGHT") "Copyright (C) 2022 Ultra Librarian. All rights reserved.")
      )
      (libsource (lib "eagle-import") (part "TEKNIC_MOTOR_8PIN"))
    )
    (comp (ref "J18")
      (value "TEKNIC_MOTOR_8PIN")
      (footprint "eagle-import:CON_39281083")
      (fields
        (field (name "MANUFACTURER_PART_NUMBER") "39281083")
        (field (name "COPYRIGHT") "Copyright (C) 2022 Ultra Librarian. All rights reserved.")
      )
      (libsource (lib "eagle-import") (part "TEKNIC_MOTOR_8PIN"))
    )
    (comp (ref "J19")
      (value "CONN_530470310_PICOBLADE_X_3")
      (footprint "eagle-import:CON_530470310_MOL")
      (fields
        (field (name "MANUFACTURER_PART_NUMBER") "530470310")
        (field (name "COPYRIGHT") "Copyright (C) 2022 Ultra Librarian. All rights reserved.")
      )
      (libsource (lib "eagle-import") (part "CONN_530470310_PICOBLADE_X_3"))
    )
    (comp (ref "J20")
      (value "CONN_530470310_PICOBLADE_X_3")
      (footprint "eagle-import:CON_530470310_MOL")
      (fields
        (field (name "MANUFACTURER_PART_NUMBER") "530470310")
        (field (name "COPYRIGHT") "Copyright (C) 2022 Ultra Librarian. All rights reserved.")
      )
      (libsource (lib "eagle-import") (part "CONN_530470310_PICOBLADE_X_3"))
    )
    (comp (ref "J21")
      (value "TEKNIC_MOTOR_8PIN")
      (footprint "eagle-import:CON_39281083")
      (fields
        (field (name "MANUFACTURER_PART_NUMBER") "39281083")
        (field (name "COPYRIGHT") "Copyright (C) 2022 Ultra Librarian. All rights reserved.")
      )
      (libsource (lib "eagle-import") (part "TEKNIC_MOTOR_8PIN"))
    )
    (comp (ref "J22")
      (value "TEKNIC_MOTOR_8PIN")
      (footprint "eagle-import:CON_39281083")
      (fields
        (field (name "MANUFACTURER_PART_NUMBER") "39281083")
        (field (name "COPYRIGHT") "Copyright (C) 2022 Ultra Librarian. All rights reserved.")
      )
      (libsource (lib "eagle-import") (part "TEKNIC_MOTOR_8PIN"))
    )
    (comp (ref "J23")
      (value "2-pos")
      (footprint "eagle-import:2_3.81MM_PITCH")
      (fields (field (name "PARTNO") "691322310002"))
      (libsource (lib "eagle-import") (part "3.81MM_1_X_2_RT_ANGLE_PLUG_HEADER"))
    )
    (comp (ref "J24")
      (value "2-pos")
      (footprint "eagle-import:2_3.81MM_PITCH")
      (fields (field (name "PARTNO") "691322310002"))
      (libsource (lib "eagle-import") (part "3.81MM_1_X_2_RT_ANGLE_PLUG_HEADER"))
    )
    (comp (ref "J25")
      (value "TEKNIC_MOTOR_8PIN")
      (footprint "eagle-import:CON_39281083")
      (fields
        (field (name "MANUFACTURER_PART_NUMBER") "39281083")
        (field (name "COPYRIGHT") "Copyright (C) 2022 Ultra Librarian. All rights reserved.")
      )
      (libsource (lib "eagle-import") (part "TEKNIC_MOTOR_8PIN"))
    )
    (comp (ref "J26")
      (value "TEKNIC_MOTOR_8PIN")
      (footprint "eagle-import:CON_39281083")
      (fields
        (field (name "MANUFACTURER_PART_NUMBER") "39281083")
        (field (name "COPYRIGHT") "Copyright (C) 2022 Ultra Librarian. All rights reserved.")
      )
      (libsource (lib "eagle-import") (part "TEKNIC_MOTOR_8PIN"))
    )
    (comp (ref "J27")
      (value "CONN_530470310_PICOBLADE_X_3")
      (footprint "eagle-import:CON_530470310_MOL")
      (fields
        (field (name "MANUFACTURER_PART_NUMBER") "530470310")
        (field (name "COPYRIGHT") "Copyright (C) 2022 Ultra Librarian. All rights reserved.")
      )
      (libsource (lib "eagle-import") (part "CONN_530470310_PICOBLADE_X_3"))
    )
    (comp (ref "J28")
      (value "CONN_530470310_PICOBLADE_X_3")
      (footprint "eagle-import:CON_530470310_MOL")
      (fields
        (field (name "MANUFACTURER_PART_NUMBER") "530470310")
        (field (name "COPYRIGHT") "Copyright (C) 2022 Ultra Librarian. All rights reserved.")
      )
      (libsource (lib "eagle-import") (part "CONN_530470310_PICOBLADE_X_3"))
    )
    (comp (ref "J29")
      (value "TEKNIC_MOTOR_8PIN")
      (footprint "eagle-import:CON_39281083")
      (fields
        (field (name "MANUFACTURER_PART_NUMBER") "39281083")
        (field (name "COPYRIGHT") "Copyright (C) 2022 Ultra Librarian. All rights reserved.")
      )
      (libsource (lib "eagle-import") (part "TEKNIC_MOTOR_8PIN"))
    )
    (comp (ref "J30")
      (value "TEKNIC_MOTOR_8PIN")
      (footprint "eagle-import:CON_39281083")
      (fields
        (field (name "MANUFACTURER_PART_NUMBER") "39281083")
        (field (name "COPYRIGHT") "Copyright (C) 2022 Ultra Librarian. All rights reserved.")
      )
      (libsource (lib "eagle-import") (part "TEKNIC_MOTOR_8PIN"))
    )
    (comp (ref "J31")
      (value "CONN_530470310_PICOBLADE_X_3")
      (footprint "eagle-import:CON_530470310_MOL")
      (fields
        (field (name "MANUFACTURER_PART_NUMBER") "530470310")
        (field (name "COPYRIGHT") "Copyright (C) 2022 Ultra Librarian. All rights reserved.")
      )
      (libsource (lib "eagle-import") (part "CONN_530470310_PICOBLADE_X_3"))
    )
    (comp (ref "J32")
      (value "CONN_530470310_PICOBLADE_X_3")
      (footprint "eagle-import:CON_530470310_MOL")
      (fields
        (field (name "MANUFACTURER_PART_NUMBER") "530470310")
        (field (name "COPYRIGHT") "Copyright (C) 2022 Ultra Librarian. All rights reserved.")
      )
      (libsource (lib "eagle-import") (part "CONN_530470310_PICOBLADE_X_3"))
    )
    (comp (ref "J33")
      (value "TEKNIC_MOTOR_8PIN")
      (footprint "eagle-import:CON_39281083")
      (fields
        (field (name "MANUFACTURER_PART_NUMBER") "39281083")
        (field (name "COPYRIGHT") "Copyright (C) 2022 Ultra Librarian. All rights reserved.")
      )
      (libsource (lib "eagle-import") (part "TEKNIC_MOTOR_8PIN"))
    )
    (comp (ref "J34")
      (value "TEKNIC_MOTOR_8PIN")
      (footprint "eagle-import:CON_39281083")
      (fields
        (field (name "MANUFACTURER_PART_NUMBER") "39281083")
        (field (name "COPYRIGHT") "Copyright (C) 2022 Ultra Librarian. All rights reserved.")
      )
      (libsource (lib "eagle-import") (part "TEKNIC_MOTOR_8PIN"))
    )
    (comp (ref "J39")
      (value "2_X_10_HEADER_GENERIC")
      (footprint "eagle-import:2_X_10_.1_INCH")
      (fields (field (name "PARTNO") "67996-420HLF"))
      (libsource (lib "eagle-import") (part "2_X_10_HEADER_GENERIC"))
    )
    (comp (ref "L1")
      (value "2.2uH")
      (footprint "eagle-import:1008")
      (fields (field (name "PARTNO") "LQM2HPN2R2MG0L"))
      (libsource (lib "eagle-import") (part "INDUCTOR_1008_2.2_MH_1.3A"))
    )
    (comp (ref "LED1")
      (value "Green")
      (footprint "eagle-import:0805")
      (fields (field (name "PARTNO") "LG R971-KN-1"))
      (libsource (lib "eagle-import") (part "LED_0805_GREEN"))
    )
    (comp (ref "LED3")
      (value "Green")
      (footprint "eagle-import:0805")
      (fields (field (name "PARTNO") "LG R971-KN-1"))
      (libsource (lib "eagle-import") (part "LED_0805_GREEN"))
    )
    (comp (ref "LED4")
      (value "Green")
      (footprint "eagle-import:0805")
      (fields (field (name "PARTNO") "LG R971-KN-1"))
      (libsource (lib "eagle-import") (part "LED_0805_GREEN"))
    )
    (comp (ref "LED5")
      (value "Green")
      (footprint "eagle-import:0805")
      (fields (field (name "PARTNO") "LG R971-KN-1"))
      (libsource (lib "eagle-import") (part "LED_0805_GREEN"))
    )
    (comp (ref "LED6")
      (value "Green")
      (footprint "eagle-import:0805")
      (fields (field (name "PARTNO") "LG R971-KN-1"))
      (libsource (lib "eagle-import") (part "LED_0805_GREEN"))
    )
    (comp (ref "LED7")
      (value "Green")
      (footprint "eagle-import:0805")
      (fields (field (name "PARTNO") "LG R971-KN-1"))
      (libsource (lib "eagle-import") (part "LED_0805_GREEN"))
    )
    (comp (ref "LED8")
      (value "Green")
      (footprint "eagle-import:0805")
      (fields (field (name "PARTNO") "LG R971-KN-1"))
      (libsource (lib "eagle-import") (part "LED_0805_GREEN"))
    )
    (comp (ref "LED9")
      (value "Green")
      (footprint "eagle-import:0805")
      (fields (field (name "PARTNO") "LG R971-KN-1"))
      (libsource (lib "eagle-import") (part "LED_0805_GREEN"))
    )
    (comp (ref "LED10")
      (value "Green")
      (footprint "eagle-import:0805")
      (fields (field (name "PARTNO") "LG R971-KN-1"))
      (libsource (lib "eagle-import") (part "LED_0805_GREEN"))
    )
    (comp (ref "LED11")
      (value "Green")
      (footprint "eagle-import:0805")
      (fields (field (name "PARTNO") "LG R971-KN-1"))
      (libsource (lib "eagle-import") (part "LED_0805_GREEN"))
    )
    (comp (ref "LED12")
      (value "Green")
      (footprint "eagle-import:0805")
      (fields (field (name "PARTNO") "LG R971-KN-1"))
      (libsource (lib "eagle-import") (part "LED_0805_GREEN"))
    )
    (comp (ref "LED13")
      (value "Green")
      (footprint "eagle-import:0805")
      (fields (field (name "PARTNO") "LG R971-KN-1"))
      (libsource (lib "eagle-import") (part "LED_0805_GREEN"))
    )
    (comp (ref "LED14")
      (value "Green")
      (footprint "eagle-import:0805")
      (fields (field (name "PARTNO") "LG R971-KN-1"))
      (libsource (lib "eagle-import") (part "LED_0805_GREEN"))
    )
    (comp (ref "LED15")
      (value "Green")
      (footprint "eagle-import:0805")
      (fields (field (name "PARTNO") "LG R971-KN-1"))
      (libsource (lib "eagle-import") (part "LED_0805_GREEN"))
    )
    (comp (ref "LED16")
      (value "Green")
      (footprint "eagle-import:0805")
      (fields (field (name "PARTNO") "LG R971-KN-1"))
      (libsource (lib "eagle-import") (part "LED_0805_GREEN"))
    )
    (comp (ref "R1")
      (value "6K49")
      (footprint "eagle-import:0402")
      (fields (field (name "PARTNO") "RMCF0402FT6K49"))
      (libsource (lib "eagle-import") (part "R_0402_6K49"))
    )
    (comp (ref "R2")
      (value "10K0")
      (footprint "eagle-import:0402")
      (fields (field (name "PARTNO") "RMCF0402JT10K0"))
      (libsource (lib "eagle-import") (part "R_0402_10K0"))
    )
    (comp (ref "R3")
      (value "10K0")
      (footprint "eagle-import:0402")
      (fields (field (name "PARTNO") "RMCF0402JT10K0"))
      (libsource (lib "eagle-import") (part "R_0402_10K0"))
    )
    (comp (ref "R4")
      (value "1K5")
      (footprint "eagle-import:0402")
      (fields (field (name "PARTNO") "RMCF0402JT1K50"))
      (libsource (lib "eagle-import") (part "R_0402_1K5"))
    )
    (comp (ref "R5")
      (value "470R0")
      (footprint "eagle-import:0402")
      (fields (field (name "PARTNO") "RMCF0402JT470R"))
      (libsource (lib "eagle-import") (part "R_0402_470R0"))
    )
    (comp (ref "R6")
      (value "1K5")
      (footprint "eagle-import:0402")
      (fields (field (name "PARTNO") "RMCF0402JT1K50"))
      (libsource (lib "eagle-import") (part "R_0402_1K5"))
    )
    (comp (ref "R7")
      (value "470R0")
      (footprint "eagle-import:0402")
      (fields (field (name "PARTNO") "RMCF0402JT470R"))
      (libsource (lib "eagle-import") (part "R_0402_470R0"))
    )
    (comp (ref "R8")
      (value "470R0")
      (footprint "eagle-import:0402")
      (fields (field (name "PARTNO") "RMCF0402JT470R"))
      (libsource (lib "eagle-import") (part "R_0402_470R0"))
    )
    (comp (ref "R9")
      (value "33R0")
      (footprint "eagle-import:0402")
      (fields (field (name "PARTNO") "RMCF0402JT33R0"))
      (libsource (lib "eagle-import") (part "R_0402_33R0"))
    )
    (comp (ref "R10")
      (value "33R0")
      (footprint "eagle-import:0402")
      (fields (field (name "PARTNO") "RMCF0402JT33R0"))
      (libsource (lib "eagle-import") (part "R_0402_33R0"))
    )
    (comp (ref "R11")
      (value "33R0")
      (footprint "eagle-import:0402")
      (fields (field (name "PARTNO") "RMCF0402JT33R0"))
      (libsource (lib "eagle-import") (part "R_0402_33R0"))
    )
    (comp (ref "R12")
      (value "33R0")
      (footprint "eagle-import:0402")
      (fields (field (name "PARTNO") "RMCF0402JT33R0"))
      (libsource (lib "eagle-import") (part "R_0402_33R0"))
    )
    (comp (ref "R13")
      (value "10K0")
      (footprint "eagle-import:0402")
      (fields (field (name "PARTNO") "RMCF0402JT10K0"))
      (libsource (lib "eagle-import") (part "R_0402_10K0"))
    )
    (comp (ref "R14")
      (value "1K0")
      (footprint "eagle-import:0402")
      (fields (field (name "PARTNO") "CRG0402J1K0"))
      (libsource (lib "eagle-import") (part "R_0402_1K0"))
    )
    (comp (ref "R15")
      (value "1K0")
      (footprint "eagle-import:0402")
      (fields (field (name "PARTNO") "CRG0402J1K0"))
      (libsource (lib "eagle-import") (part "R_0402_1K0"))
    )
    (comp (ref "R16")
      (value "15K0")
      (footprint "eagle-import:0402")
      (fields (field (name "PARTNO") "RMCF0402JT15K0"))
      (libsource (lib "eagle-import") (part "R_0402_15K0"))
    )
    (comp (ref "R17")
      (value "27R0")
      (footprint "eagle-import:0402")
      (fields (field (name "PARTNO") "RMCF0402JT27R0"))
      (libsource (lib "eagle-import") (part "R_0402_27R0"))
    )
    (comp (ref "R18")
      (value "27R0")
      (footprint "eagle-import:0402")
      (fields (field (name "PARTNO") "RMCF0402JT27R0"))
      (libsource (lib "eagle-import") (part "R_0402_27R0"))
    )
    (comp (ref "R19")
      (value "10K0")
      (footprint "eagle-import:0402")
      (fields (field (name "PARTNO") "RMCF0402JT10K0"))
      (libsource (lib "eagle-import") (part "R_0402_10K0"))
    )
    (comp (ref "R20")
      (value "10K0")
      (footprint "eagle-import:0402")
      (fields (field (name "PARTNO") "RMCF0402JT10K0"))
      (libsource (lib "eagle-import") (part "R_0402_10K0"))
    )
    (comp (ref "R21")
      (value "30K0")
      (footprint "eagle-import:0402")
      (fields (field (name "PARTNO") "RC0402JR-0730KL"))
      (libsource (lib "eagle-import") (part "R_0402_30K0"))
    )
    (comp (ref "R22")
      (value "2K2")
      (footprint "eagle-import:0402")
      (fields (field (name "PARTNO") "RMCF0402JT2K20"))
      (libsource (lib "eagle-import") (part "R_0402_2K2"))
    )
    (comp (ref "R23")
      (value "10K0")
      (footprint "eagle-import:0402")
      (fields (field (name "PARTNO") "RMCF0402JT10K0"))
      (libsource (lib "eagle-import") (part "R_0402_10K0"))
    )
    (comp (ref "R24")
      (value "10K0")
      (footprint "eagle-import:0402")
      (fields (field (name "PARTNO") "RMCF0402JT10K0"))
      (libsource (lib "eagle-import") (part "R_0402_10K0"))
    )
    (comp (ref "R25")
      (value "100K")
      (footprint "eagle-import:0402")
      (libsource (lib "eagle-import") (part "R_0402"))
    )
    (comp (ref "R26")
      (value "100K")
      (footprint "eagle-import:0402")
      (libsource (lib "eagle-import") (part "R_0402"))
    )
    (comp (ref "R27")
      (value "100K")
      (footprint "eagle-import:0402")
      (libsource (lib "eagle-import") (part "R_0402"))
    )
    (comp (ref "R28")
      (value "2.2K")
      (footprint "eagle-import:0402")
      (libsource (lib "eagle-import") (part "R_0402"))
    )
    (comp (ref "R29")
      (value "500R0")
      (footprint "eagle-import:0402")
      (libsource (lib "eagle-import") (part "R_0402"))
    )
    (comp (ref "R30")
      (value "500R0")
      (footprint "eagle-import:0402")
      (libsource (lib "eagle-import") (part "R_0402"))
    )
    (comp (ref "R31")
      (value "470R0")
      (footprint "eagle-import:0402")
      (fields (field (name "PARTNO") "RMCF0402JT470R"))
      (libsource (lib "eagle-import") (part "R_0402_470R0"))
    )
    (comp (ref "R32")
      (value "470R0")
      (footprint "eagle-import:0402")
      (fields (field (name "PARTNO") "RMCF0402JT470R"))
      (libsource (lib "eagle-import") (part "R_0402_470R0"))
    )
    (comp (ref "R33")
      (value "470R0")
      (footprint "eagle-import:0402")
      (fields (field (name "PARTNO") "RMCF0402JT470R"))
      (libsource (lib "eagle-import") (part "R_0402_470R0"))
    )
    (comp (ref "R34")
      (value "10K0")
      (footprint "eagle-import:0402")
      (fields (field (name "PARTNO") "RMCF0402JT10K0"))
      (libsource (lib "eagle-import") (part "R_0402_10K0"))
    )
    (comp (ref "R35")
      (value "2.2K")
      (footprint "eagle-import:0402")
      (libsource (lib "eagle-import") (part "R_0402"))
    )
    (comp (ref "R36")
      (value "470R0")
      (footprint "eagle-import:0402")
      (fields (field (name "PARTNO") "RMCF0402JT470R"))
      (libsource (lib "eagle-import") (part "R_0402_470R0"))
    )
    (comp (ref "R37")
      (value "1k")
      (footprint "eagle-import:0805")
      (libsource (lib "eagle-import") (part "R_0805"))
    )
    (comp (ref "R38")
      (value "33")
      (footprint "eagle-import:0805")
      (libsource (lib "eagle-import") (part "R_0805"))
    )
    (comp (ref "R39")
      (value "33")
      (footprint "eagle-import:0805")
      (libsource (lib "eagle-import") (part "R_0805"))
    )
    (comp (ref "R40")
      (value "33")
      (footprint "eagle-import:0805")
      (libsource (lib "eagle-import") (part "R_0805"))
    )
    (comp (ref "R41")
      (value "1k")
      (footprint "eagle-import:0805")
      (libsource (lib "eagle-import") (part "R_0805"))
    )
    (comp (ref "R42")
      (value "1k")
      (footprint "eagle-import:0805")
      (libsource (lib "eagle-import") (part "R_0805"))
    )
    (comp (ref "R43")
      (value "1k")
      (footprint "eagle-import:0805")
      (libsource (lib "eagle-import") (part "R_0805"))
    )
    (comp (ref "R44")
      (value "33")
      (footprint "eagle-import:0805")
      (libsource (lib "eagle-import") (part "R_0805"))
    )
    (comp (ref "R45")
      (value "33")
      (footprint "eagle-import:0805")
      (libsource (lib "eagle-import") (part "R_0805"))
    )
    (comp (ref "R46")
      (value "33")
      (footprint "eagle-import:0805")
      (libsource (lib "eagle-import") (part "R_0805"))
    )
    (comp (ref "R47")
      (value "1k")
      (footprint "eagle-import:0805")
      (libsource (lib "eagle-import") (part "R_0805"))
    )
    (comp (ref "R48")
      (value "1k")
      (footprint "eagle-import:0805")
      (libsource (lib "eagle-import") (part "R_0805"))
    )
    (comp (ref "R49")
      (value "500R0")
      (footprint "eagle-import:0402")
      (libsource (lib "eagle-import") (part "R_0402"))
    )
    (comp (ref "R50")
      (value "500R0")
      (footprint "eagle-import:0402")
      (libsource (lib "eagle-import") (part "R_0402"))
    )
    (comp (ref "R51")
      (value "470R0")
      (footprint "eagle-import:0402")
      (fields (field (name "PARTNO") "RMCF0402JT470R"))
      (libsource (lib "eagle-import") (part "R_0402_470R0"))
    )
    (comp (ref "R52")
      (value "470R0")
      (footprint "eagle-import:0402")
      (fields (field (name "PARTNO") "RMCF0402JT470R"))
      (libsource (lib "eagle-import") (part "R_0402_470R0"))
    )
    (comp (ref "R53")
      (value "10K0")
      (footprint "eagle-import:0402")
      (fields (field (name "PARTNO") "RMCF0402JT10K0"))
      (libsource (lib "eagle-import") (part "R_0402_10K0"))
    )
    (comp (ref "R54")
      (value "2.2K")
      (footprint "eagle-import:0402")
      (libsource (lib "eagle-import") (part "R_0402"))
    )
    (comp (ref "R55")
      (value "470R0")
      (footprint "eagle-import:0402")
      (fields (field (name "PARTNO") "RMCF0402JT470R"))
      (libsource (lib "eagle-import") (part "R_0402_470R0"))
    )
    (comp (ref "R56")
      (value "10K0")
      (footprint "eagle-import:0402")
      (fields (field (name "PARTNO") "RMCF0402JT10K0"))
      (libsource (lib "eagle-import") (part "R_0402_10K0"))
    )
    (comp (ref "R57")
      (value "2.2K")
      (footprint "eagle-import:0402")
      (libsource (lib "eagle-import") (part "R_0402"))
    )
    (comp (ref "R58")
      (value "470R0")
      (footprint "eagle-import:0402")
      (fields (field (name "PARTNO") "RMCF0402JT470R"))
      (libsource (lib "eagle-import") (part "R_0402_470R0"))
    )
    (comp (ref "R59")
      (value "10K0")
      (footprint "eagle-import:0402")
      (fields (field (name "PARTNO") "RMCF0402JT10K0"))
      (libsource (lib "eagle-import") (part "R_0402_10K0"))
    )
    (comp (ref "R60")
      (value "2.2K")
      (footprint "eagle-import:0402")
      (libsource (lib "eagle-import") (part "R_0402"))
    )
    (comp (ref "R61")
      (value "1k")
      (footprint "eagle-import:0805")
      (libsource (lib "eagle-import") (part "R_0805"))
    )
    (comp (ref "R62")
      (value "33")
      (footprint "eagle-import:0805")
      (libsource (lib "eagle-import") (part "R_0805"))
    )
    (comp (ref "R63")
      (value "33")
      (footprint "eagle-import:0805")
      (libsource (lib "eagle-import") (part "R_0805"))
    )
    (comp (ref "R64")
      (value "33")
      (footprint "eagle-import:0805")
      (libsource (lib "eagle-import") (part "R_0805"))
    )
    (comp (ref "R65")
      (value "1k")
      (footprint "eagle-import:0805")
      (libsource (lib "eagle-import") (part "R_0805"))
    )
    (comp (ref "R66")
      (value "1k")
      (footprint "eagle-import:0805")
      (libsource (lib "eagle-import") (part "R_0805"))
    )
    (comp (ref "R67")
      (value "1k")
      (footprint "eagle-import:0805")
      (libsource (lib "eagle-import") (part "R_0805"))
    )
    (comp (ref "R68")
      (value "33")
      (footprint "eagle-import:0805")
      (libsource (lib "eagle-import") (part "R_0805"))
    )
    (comp (ref "R69")
      (value "33")
      (footprint "eagle-import:0805")
      (libsource (lib "eagle-import") (part "R_0805"))
    )
    (comp (ref "R70")
      (value "33")
      (footprint "eagle-import:0805")
      (libsource (lib "eagle-import") (part "R_0805"))
    )
    (comp (ref "R71")
      (value "1k")
      (footprint "eagle-import:0805")
      (libsource (lib "eagle-import") (part "R_0805"))
    )
    (comp (ref "R72")
      (value "1k")
      (footprint "eagle-import:0805")
      (libsource (lib "eagle-import") (part "R_0805"))
    )
    (comp (ref "R73")
      (value "470R0")
      (footprint "eagle-import:0402")
      (fields (field (name "PARTNO") "RMCF0402JT470R"))
      (libsource (lib "eagle-import") (part "R_0402_470R0"))
    )
    (comp (ref "R74")
      (value "10K0")
      (footprint "eagle-import:0402")
      (fields (field (name "PARTNO") "RMCF0402JT10K0"))
      (libsource (lib "eagle-import") (part "R_0402_10K0"))
    )
    (comp (ref "R75")
      (value "2.2K")
      (footprint "eagle-import:0402")
      (libsource (lib "eagle-import") (part "R_0402"))
    )
    (comp (ref "R76")
      (value "470R0")
      (footprint "eagle-import:0402")
      (fields (field (name "PARTNO") "RMCF0402JT470R"))
      (libsource (lib "eagle-import") (part "R_0402_470R0"))
    )
    (comp (ref "R77")
      (value "10K0")
      (footprint "eagle-import:0402")
      (fields (field (name "PARTNO") "RMCF0402JT10K0"))
      (libsource (lib "eagle-import") (part "R_0402_10K0"))
    )
    (comp (ref "R78")
      (value "2.2K")
      (footprint "eagle-import:0402")
      (libsource (lib "eagle-import") (part "R_0402"))
    )
    (comp (ref "R79")
      (value "470R0")
      (footprint "eagle-import:0402")
      (fields (field (name "PARTNO") "RMCF0402JT470R"))
      (libsource (lib "eagle-import") (part "R_0402_470R0"))
    )
    (comp (ref "R80")
      (value "10K0")
      (footprint "eagle-import:0402")
      (fields (field (name "PARTNO") "RMCF0402JT10K0"))
      (libsource (lib "eagle-import") (part "R_0402_10K0"))
    )
    (comp (ref "R81")
      (value "2.2K")
      (footprint "eagle-import:0402")
      (libsource (lib "eagle-import") (part "R_0402"))
    )
    (comp (ref "R82")
      (value "470R0")
      (footprint "eagle-import:0402")
      (fields (field (name "PARTNO") "RMCF0402JT470R"))
      (libsource (lib "eagle-import") (part "R_0402_470R0"))
    )
    (comp (ref "R83")
      (value "10K0")
      (footprint "eagle-import:0402")
      (fields (field (name "PARTNO") "RMCF0402JT10K0"))
      (libsource (lib "eagle-import") (part "R_0402_10K0"))
    )
    (comp (ref "R84")
      (value "2.2K")
      (footprint "eagle-import:0402")
      (libsource (lib "eagle-import") (part "R_0402"))
    )
    (comp (ref "R85")
      (value "1k")
      (footprint "eagle-import:0805")
      (libsource (lib "eagle-import") (part "R_0805"))
    )
    (comp (ref "R86")
      (value "33")
      (footprint "eagle-import:0805")
      (libsource (lib "eagle-import") (part "R_0805"))
    )
    (comp (ref "R87")
      (value "33")
      (footprint "eagle-import:0805")
      (libsource (lib "eagle-import") (part "R_0805"))
    )
    (comp (ref "R88")
      (value "33")
      (footprint "eagle-import:0805")
      (libsource (lib "eagle-import") (part "R_0805"))
    )
    (comp (ref "R89")
      (value "1k")
      (footprint "eagle-import:0805")
      (libsource (lib "eagle-import") (part "R_0805"))
    )
    (comp (ref "R90")
      (value "1k")
      (footprint "eagle-import:0805")
      (libsource (lib "eagle-import") (part "R_0805"))
    )
    (comp (ref "R91")
      (value "1k")
      (footprint "eagle-import:0805")
      (libsource (lib "eagle-import") (part "R_0805"))
    )
    (comp (ref "R92")
      (value "33")
      (footprint "eagle-import:0805")
      (libsource (lib "eagle-import") (part "R_0805"))
    )
    (comp (ref "R93")
      (value "33")
      (footprint "eagle-import:0805")
      (libsource (lib "eagle-import") (part "R_0805"))
    )
    (comp (ref "R94")
      (value "33")
      (footprint "eagle-import:0805")
      (libsource (lib "eagle-import") (part "R_0805"))
    )
    (comp (ref "R95")
      (value "1k")
      (footprint "eagle-import:0805")
      (libsource (lib "eagle-import") (part "R_0805"))
    )
    (comp (ref "R96")
      (value "1k")
      (footprint "eagle-import:0805")
      (libsource (lib "eagle-import") (part "R_0805"))
    )
    (comp (ref "R97")
      (value "470R0")
      (footprint "eagle-import:0402")
      (fields (field (name "PARTNO") "RMCF0402JT470R"))
      (libsource (lib "eagle-import") (part "R_0402_470R0"))
    )
    (comp (ref "R98")
      (value "10K0")
      (footprint "eagle-import:0402")
      (fields (field (name "PARTNO") "RMCF0402JT10K0"))
      (libsource (lib "eagle-import") (part "R_0402_10K0"))
    )
    (comp (ref "R99")
      (value "2.2K")
      (footprint "eagle-import:0402")
      (libsource (lib "eagle-import") (part "R_0402"))
    )
    (comp (ref "R100")
      (value "470R0")
      (footprint "eagle-import:0402")
      (fields (field (name "PARTNO") "RMCF0402JT470R"))
      (libsource (lib "eagle-import") (part "R_0402_470R0"))
    )
    (comp (ref "R101")
      (value "10K0")
      (footprint "eagle-import:0402")
      (fields (field (name "PARTNO") "RMCF0402JT10K0"))
      (libsource (lib "eagle-import") (part "R_0402_10K0"))
    )
    (comp (ref "R102")
      (value "100K")
      (footprint "eagle-import:0402")
      (libsource (lib "eagle-import") (part "R_0402"))
    )
    (comp (ref "R103")
      (value "100K")
      (footprint "eagle-import:0402")
      (libsource (lib "eagle-import") (part "R_0402"))
    )
    (comp (ref "R104")
      (value "100K")
      (footprint "eagle-import:0402")
      (libsource (lib "eagle-import") (part "R_0402"))
    )
    (comp (ref "R105")
      (value "100K")
      (footprint "eagle-import:0402")
      (libsource (lib "eagle-import") (part "R_0402"))
    )
    (comp (ref "R106")
      (value "100K")
      (footprint "eagle-import:0402")
      (libsource (lib "eagle-import") (part "R_0402"))
    )
    (comp (ref "R107")
      (value "100K")
      (footprint "eagle-import:0402")
      (libsource (lib "eagle-import") (part "R_0402"))
    )
    (comp (ref "R108")
      (value "100K")
      (footprint "eagle-import:0402")
      (libsource (lib "eagle-import") (part "R_0402"))
    )
    (comp (ref "R109")
      (value "1k")
      (footprint "eagle-import:0805")
      (libsource (lib "eagle-import") (part "R_0805"))
    )
    (comp (ref "R110")
      (value "33")
      (footprint "eagle-import:0805")
      (libsource (lib "eagle-import") (part "R_0805"))
    )
    (comp (ref "R111")
      (value "33")
      (footprint "eagle-import:0805")
      (libsource (lib "eagle-import") (part "R_0805"))
    )
    (comp (ref "R112")
      (value "33")
      (footprint "eagle-import:0805")
      (libsource (lib "eagle-import") (part "R_0805"))
    )
    (comp (ref "R113")
      (value "1k")
      (footprint "eagle-import:0805")
      (libsource (lib "eagle-import") (part "R_0805"))
    )
    (comp (ref "R114")
      (value "1k")
      (footprint "eagle-import:0805")
      (libsource (lib "eagle-import") (part "R_0805"))
    )
    (comp (ref "R115")
      (value "1k")
      (footprint "eagle-import:0805")
      (libsource (lib "eagle-import") (part "R_0805"))
    )
    (comp (ref "R116")
      (value "33")
      (footprint "eagle-import:0805")
      (libsource (lib "eagle-import") (part "R_0805"))
    )
    (comp (ref "R117")
      (value "33")
      (footprint "eagle-import:0805")
      (libsource (lib "eagle-import") (part "R_0805"))
    )
    (comp (ref "R118")
      (value "33")
      (footprint "eagle-import:0805")
      (libsource (lib "eagle-import") (part "R_0805"))
    )
    (comp (ref "R119")
      (value "1k")
      (footprint "eagle-import:0805")
      (libsource (lib "eagle-import") (part "R_0805"))
    )
    (comp (ref "R120")
      (value "1k")
      (footprint "eagle-import:0805")
      (libsource (lib "eagle-import") (part "R_0805"))
    )
    (comp (ref "R133")
      (value "1k")
      (footprint "eagle-import:0805")
      (libsource (lib "eagle-import") (part "R_0805"))
    )
    (comp (ref "R134")
      (value "33")
      (footprint "eagle-import:0805")
      (libsource (lib "eagle-import") (part "R_0805"))
    )
    (comp (ref "R135")
      (value "33")
      (footprint "eagle-import:0805")
      (libsource (lib "eagle-import") (part "R_0805"))
    )
    (comp (ref "R136")
      (value "33")
      (footprint "eagle-import:0805")
      (libsource (lib "eagle-import") (part "R_0805"))
    )
    (comp (ref "R137")
      (value "1k")
      (footprint "eagle-import:0805")
      (libsource (lib "eagle-import") (part "R_0805"))
    )
    (comp (ref "R138")
      (value "1k")
      (footprint "eagle-import:0805")
      (libsource (lib "eagle-import") (part "R_0805"))
    )
    (comp (ref "R139")
      (value "1k")
      (footprint "eagle-import:0805")
      (libsource (lib "eagle-import") (part "R_0805"))
    )
    (comp (ref "R140")
      (value "33")
      (footprint "eagle-import:0805")
      (libsource (lib "eagle-import") (part "R_0805"))
    )
    (comp (ref "R141")
      (value "33")
      (footprint "eagle-import:0805")
      (libsource (lib "eagle-import") (part "R_0805"))
    )
    (comp (ref "R142")
      (value "33")
      (footprint "eagle-import:0805")
      (libsource (lib "eagle-import") (part "R_0805"))
    )
    (comp (ref "R143")
      (value "1k")
      (footprint "eagle-import:0805")
      (libsource (lib "eagle-import") (part "R_0805"))
    )
    (comp (ref "R144")
      (value "1k")
      (footprint "eagle-import:0805")
      (libsource (lib "eagle-import") (part "R_0805"))
    )
    (comp (ref "R157")
      (value "1k")
      (footprint "eagle-import:0805")
      (libsource (lib "eagle-import") (part "R_0805"))
    )
    (comp (ref "R158")
      (value "33")
      (footprint "eagle-import:0805")
      (libsource (lib "eagle-import") (part "R_0805"))
    )
    (comp (ref "R159")
      (value "33")
      (footprint "eagle-import:0805")
      (libsource (lib "eagle-import") (part "R_0805"))
    )
    (comp (ref "R160")
      (value "33")
      (footprint "eagle-import:0805")
      (libsource (lib "eagle-import") (part "R_0805"))
    )
    (comp (ref "R161")
      (value "1k")
      (footprint "eagle-import:0805")
      (libsource (lib "eagle-import") (part "R_0805"))
    )
    (comp (ref "R162")
      (value "1k")
      (footprint "eagle-import:0805")
      (libsource (lib "eagle-import") (part "R_0805"))
    )
    (comp (ref "R163")
      (value "1k")
      (footprint "eagle-import:0805")
      (libsource (lib "eagle-import") (part "R_0805"))
    )
    (comp (ref "R164")
      (value "33")
      (footprint "eagle-import:0805")
      (libsource (lib "eagle-import") (part "R_0805"))
    )
    (comp (ref "R165")
      (value "33")
      (footprint "eagle-import:0805")
      (libsource (lib "eagle-import") (part "R_0805"))
    )
    (comp (ref "R166")
      (value "33")
      (footprint "eagle-import:0805")
      (libsource (lib "eagle-import") (part "R_0805"))
    )
    (comp (ref "R167")
      (value "1k")
      (footprint "eagle-import:0805")
      (libsource (lib "eagle-import") (part "R_0805"))
    )
    (comp (ref "R168")
      (value "1k")
      (footprint "eagle-import:0805")
      (libsource (lib "eagle-import") (part "R_0805"))
    )
    (comp (ref "RJ1")
      (value "RJ45")
      (footprint "eagle-import:RJ45_TH_ELEC")
      (fields (field (name "PARTNO") "13F-64GYD2PL2NL"))
      (libsource (lib "eagle-import") (part "RJ45_WITH_ELEC"))
    )
    (comp (ref "U$1")
      (value "RELAY_KYOTO_KF0604D")
      (footprint "eagle-import:RELAY_KYOTO_KF0604D")
      (libsource (lib "eagle-import") (part "RELAY_KYOTO_KF0604D"))
    )
    (comp (ref "U$2")
      (value "RELAY_KYOTO_KF0604D")
      (footprint "eagle-import:RELAY_KYOTO_KF0604D")
      (libsource (lib "eagle-import") (part "RELAY_KYOTO_KF0604D"))
    )
    (comp (ref "U$7")
      (value "RELAY_KYOTO_KF0604D")
      (footprint "eagle-import:RELAY_KYOTO_KF0604D")
      (libsource (lib "eagle-import") (part "RELAY_KYOTO_KF0604D"))
    )
    (comp (ref "U$8")
      (value "RELAY_KYOTO_KF0604D")
      (footprint "eagle-import:RELAY_KYOTO_KF0604D")
      (libsource (lib "eagle-import") (part "RELAY_KYOTO_KF0604D"))
    )
    (comp (ref "U1")
      (value "KSZ8081_QFN_24")
      (footprint "eagle-import:QFN-24-M")
      (fields (field (name "PARTNO") "KSZ8081RNACA"))
      (libsource (lib "eagle-import") (part "KSZ8081RNACAQFN-24-M"))
    )
    (comp (ref "U2")
      (value "AP2151DWG-7")
      (footprint "eagle-import:SOT-23-5")
      (fields (field (name "PARTNO") "AP2151WG-7"))
      (libsource (lib "eagle-import") (part "AP2151DWG-7"))
    )
    (comp (ref "U3")
      (value "S7G2LQFP176")
      (footprint "eagle-import:LQFP176_24X24")
      (fields (field (name "PARTNO") "R7FS7G27H3A01CFC#AA0"))
      (libsource (lib "eagle-import") (part "RENESAS_S7G2_X_176"))
    )
    (comp (ref "U5")
      (value "NPN")
      (footprint "eagle-import:SOT323")
      (fields (field (name "PARTNO") "BC846BW_NPN"))
      (libsource (lib "eagle-import") (part "BC846BW"))
    )
    (comp (ref "U6")
      (value "NPN")
      (footprint "eagle-import:SOT323")
      (fields (field (name "PARTNO") "BC846BW_NPN"))
      (libsource (lib "eagle-import") (part "BC846BW"))
    )
    (comp (ref "U7")
      (value "NPN")
      (footprint "eagle-import:SOT323")
      (fields (field (name "PARTNO") "BC846BW_NPN"))
      (libsource (lib "eagle-import") (part "BC846BW"))
    )
    (comp (ref "U8")
      (value "NPN")
      (footprint "eagle-import:SOT323")
      (fields (field (name "PARTNO") "BC846BW_NPN"))
      (libsource (lib "eagle-import") (part "BC846BW"))
    )
    (comp (ref "U9")
      (value "NPN")
      (footprint "eagle-import:SOT323")
      (fields (field (name "PARTNO") "BC846BW_NPN"))
      (libsource (lib "eagle-import") (part "BC846BW"))
    )
    (comp (ref "U10")
      (value "NPN")
      (footprint "eagle-import:SOT323")
      (fields (field (name "PARTNO") "BC846BW_NPN"))
      (libsource (lib "eagle-import") (part "BC846BW"))
    )
    (comp (ref "U11")
      (value "NPN")
      (footprint "eagle-import:SOT323")
      (fields (field (name "PARTNO") "BC846BW_NPN"))
      (libsource (lib "eagle-import") (part "BC846BW"))
    )
    (comp (ref "U12")
      (value "NPN")
      (footprint "eagle-import:SOT323")
      (fields (field (name "PARTNO") "BC846BW_NPN"))
      (libsource (lib "eagle-import") (part "BC846BW"))
    )
    (comp (ref "U13")
      (value "NPN")
      (footprint "eagle-import:SOT323")
      (fields (field (name "PARTNO") "BC846BW_NPN"))
      (libsource (lib "eagle-import") (part "BC846BW"))
    )
    (comp (ref "U14")
      (value "NPN")
      (footprint "eagle-import:SOT323")
      (fields (field (name "PARTNO") "BC846BW_NPN"))
      (libsource (lib "eagle-import") (part "BC846BW"))
    )
    (comp (ref "U15")
      (value "NPN")
      (footprint "eagle-import:SOT323")
      (fields (field (name "PARTNO") "BC846BW_NPN"))
      (libsource (lib "eagle-import") (part "BC846BW"))
    )
    (comp (ref "U16")
      (value "NPN")
      (footprint "eagle-import:SOT323")
      (fields (field (name "PARTNO") "BC846BW_NPN"))
      (libsource (lib "eagle-import") (part "BC846BW"))
    )
    (comp (ref "U17")
      (value "NPN")
      (footprint "eagle-import:SOT323")
      (fields (field (name "PARTNO") "BC846BW_NPN"))
      (libsource (lib "eagle-import") (part "BC846BW"))
    )
    (comp (ref "U18")
      (value "NPN")
      (footprint "eagle-import:SOT323")
      (fields (field (name "PARTNO") "BC846BW_NPN"))
      (libsource (lib "eagle-import") (part "BC846BW"))
    )
    (comp (ref "U19")
      (value "NPN")
      (footprint "eagle-import:SOT323")
      (fields (field (name "PARTNO") "BC846BW_NPN"))
      (libsource (lib "eagle-import") (part "BC846BW"))
    )
    (comp (ref "U20")
      (value "NPN")
      (footprint "eagle-import:SOT323")
      (fields (field (name "PARTNO") "BC846BW_NPN"))
      (libsource (lib "eagle-import") (part "BC846BW"))
    )
    (comp (ref "U21")
      (value "NPN")
      (footprint "eagle-import:SOT323")
      (fields (field (name "PARTNO") "BC846BW_NPN"))
      (libsource (lib "eagle-import") (part "BC846BW"))
    )
    (comp (ref "U22")
      (value "NPN")
      (footprint "eagle-import:SOT323")
      (fields (field (name "PARTNO") "BC846BW_NPN"))
      (libsource (lib "eagle-import") (part "BC846BW"))
    )
    (comp (ref "U23")
      (value "NPN")
      (footprint "eagle-import:SOT323")
      (fields (field (name "PARTNO") "BC846BW_NPN"))
      (libsource (lib "eagle-import") (part "BC846BW"))
    )
    (comp (ref "U24")
      (value "NPN")
      (footprint "eagle-import:SOT323")
      (fields (field (name "PARTNO") "BC846BW_NPN"))
      (libsource (lib "eagle-import") (part "BC846BW"))
    )
    (comp (ref "U25")
      (value "NPN")
      (footprint "eagle-import:SOT323")
      (fields (field (name "PARTNO") "BC846BW_NPN"))
      (libsource (lib "eagle-import") (part "BC846BW"))
    )
    (comp (ref "U26")
      (value "NPN")
      (footprint "eagle-import:SOT323")
      (fields (field (name "PARTNO") "BC846BW_NPN"))
      (libsource (lib "eagle-import") (part "BC846BW"))
    )
    (comp (ref "U27")
      (value "NPN")
      (footprint "eagle-import:SOT323")
      (fields (field (name "PARTNO") "BC846BW_NPN"))
      (libsource (lib "eagle-import") (part "BC846BW"))
    )
    (comp (ref "U28")
      (value "NPN")
      (footprint "eagle-import:SOT323")
      (fields (field (name "PARTNO") "BC846BW_NPN"))
      (libsource (lib "eagle-import") (part "BC846BW"))
    )
    (comp (ref "U29")
      (value "NPN")
      (footprint "eagle-import:SOT323")
      (fields (field (name "PARTNO") "BC846BW_NPN"))
      (libsource (lib "eagle-import") (part "BC846BW"))
    )
    (comp (ref "U30")
      (value "NPN")
      (footprint "eagle-import:SOT323")
      (fields (field (name "PARTNO") "BC846BW_NPN"))
      (libsource (lib "eagle-import") (part "BC846BW"))
    )
    (comp (ref "U34")
      (value "NPN")
      (footprint "eagle-import:SOT323")
      (fields (field (name "PARTNO") "BC846BW_NPN"))
      (libsource (lib "eagle-import") (part "BC846BW"))
    )
    (comp (ref "U35")
      (value "NPN")
      (footprint "eagle-import:SOT323")
      (fields (field (name "PARTNO") "BC846BW_NPN"))
      (libsource (lib "eagle-import") (part "BC846BW"))
    )
    (comp (ref "U36")
      (value "NPN")
      (footprint "eagle-import:SOT323")
      (fields (field (name "PARTNO") "BC846BW_NPN"))
      (libsource (lib "eagle-import") (part "BC846BW"))
    )
    (comp (ref "U37")
      (value "NPN")
      (footprint "eagle-import:SOT323")
      (fields (field (name "PARTNO") "BC846BW_NPN"))
      (libsource (lib "eagle-import") (part "BC846BW"))
    )
    (comp (ref "U38")
      (value "NPN")
      (footprint "eagle-import:SOT323")
      (fields (field (name "PARTNO") "BC846BW_NPN"))
      (libsource (lib "eagle-import") (part "BC846BW"))
    )
    (comp (ref "U39")
      (value "NPN")
      (footprint "eagle-import:SOT323")
      (fields (field (name "PARTNO") "BC846BW_NPN"))
      (libsource (lib "eagle-import") (part "BC846BW"))
    )
    (comp (ref "U46")
      (value "NPN")
      (footprint "eagle-import:SOT323")
      (fields (field (name "PARTNO") "BC846BW_NPN"))
      (libsource (lib "eagle-import") (part "BC846BW"))
    )
    (comp (ref "U47")
      (value "NPN")
      (footprint "eagle-import:SOT323")
      (fields (field (name "PARTNO") "BC846BW_NPN"))
      (libsource (lib "eagle-import") (part "BC846BW"))
    )
    (comp (ref "U48")
      (value "NPN")
      (footprint "eagle-import:SOT323")
      (fields (field (name "PARTNO") "BC846BW_NPN"))
      (libsource (lib "eagle-import") (part "BC846BW"))
    )
    (comp (ref "U49")
      (value "NPN")
      (footprint "eagle-import:SOT323")
      (fields (field (name "PARTNO") "BC846BW_NPN"))
      (libsource (lib "eagle-import") (part "BC846BW"))
    )
    (comp (ref "U50")
      (value "NPN")
      (footprint "eagle-import:SOT323")
      (fields (field (name "PARTNO") "BC846BW_NPN"))
      (libsource (lib "eagle-import") (part "BC846BW"))
    )
    (comp (ref "U51")
      (value "NPN")
      (footprint "eagle-import:SOT323")
      (fields (field (name "PARTNO") "BC846BW_NPN"))
      (libsource (lib "eagle-import") (part "BC846BW"))
    )
    (comp (ref "U58")
      (value "NPN")
      (footprint "eagle-import:SOT323")
      (fields (field (name "PARTNO") "BC846BW_NPN"))
      (libsource (lib "eagle-import") (part "BC846BW"))
    )
    (comp (ref "U59")
      (value "NPN")
      (footprint "eagle-import:SOT323")
      (fields (field (name "PARTNO") "BC846BW_NPN"))
      (libsource (lib "eagle-import") (part "BC846BW"))
    )
    (comp (ref "U60")
      (value "NPN")
      (footprint "eagle-import:SOT323")
      (fields (field (name "PARTNO") "BC846BW_NPN"))
      (libsource (lib "eagle-import") (part "BC846BW"))
    )
    (comp (ref "U61")
      (value "NPN")
      (footprint "eagle-import:SOT323")
      (fields (field (name "PARTNO") "BC846BW_NPN"))
      (libsource (lib "eagle-import") (part "BC846BW"))
    )
    (comp (ref "U62")
      (value "NPN")
      (footprint "eagle-import:SOT323")
      (fields (field (name "PARTNO") "BC846BW_NPN"))
      (libsource (lib "eagle-import") (part "BC846BW"))
    )
    (comp (ref "U63")
      (value "NPN")
      (footprint "eagle-import:SOT323")
      (fields (field (name "PARTNO") "BC846BW_NPN"))
      (libsource (lib "eagle-import") (part "BC846BW"))
    )
    (comp (ref "U70")
      (value "NPN")
      (footprint "eagle-import:SOT323")
      (fields (field (name "PARTNO") "BC846BW_NPN"))
      (libsource (lib "eagle-import") (part "BC846BW"))
    )
    (comp (ref "U71")
      (value "NPN")
      (footprint "eagle-import:SOT323")
      (fields (field (name "PARTNO") "BC846BW_NPN"))
      (libsource (lib "eagle-import") (part "BC846BW"))
    )
    (comp (ref "U72")
      (value "NPN")
      (footprint "eagle-import:SOT323")
      (fields (field (name "PARTNO") "BC846BW_NPN"))
      (libsource (lib "eagle-import") (part "BC846BW"))
    )
    (comp (ref "U73")
      (value "NPN")
      (footprint "eagle-import:SOT323")
      (fields (field (name "PARTNO") "BC846BW_NPN"))
      (libsource (lib "eagle-import") (part "BC846BW"))
    )
    (comp (ref "U74")
      (value "NPN")
      (footprint "eagle-import:SOT323")
      (fields (field (name "PARTNO") "BC846BW_NPN"))
      (libsource (lib "eagle-import") (part "BC846BW"))
    )
    (comp (ref "U75")
      (value "NPN")
      (footprint "eagle-import:SOT323")
      (fields (field (name "PARTNO") "BC846BW_NPN"))
      (libsource (lib "eagle-import") (part "BC846BW"))
    )
    (comp (ref "X1")
      (value "25MHz")
      (footprint "eagle-import:SMD_3225")
      (fields (field (name "PARTNO") "FA-238 25.0000MB-B3"))
      (libsource (lib "eagle-import") (part "XTAL_25_MHZ"))
    )
    (comp (ref "X2")
      (value "24MHz")
      (footprint "eagle-import:SMD_3225")
      (fields (field (name "PARTNO") "FA-238 24.0000MB-C3 "))
      (libsource (lib "eagle-import") (part "XTAL_24_MHZ"))
    )
    (comp (ref "X3")
      (value "32.768KHz")
      (footprint "eagle-import:SMD_X_2_PADS")
      (fields (field (name "PARTNO") "ABS07-32.768KHZ-T"))
      (libsource (lib "eagle-import") (part "XTAL_32.768KHZ"))
    )
  )
  (nets
    (net (code "1") (name "A_A_DIR") (class "Default")
      (node (ref "R111") (pin "1") (pinfunction "1_1") (pintype "passive"))
      (node (ref "U3") (pin "73") (pinfunction "P9_5_73") (pintype "bidirectional"))
    )
    (net (code "2") (name "A_A_ENABLE") (class "Default")
      (node (ref "R112") (pin "1") (pinfunction "1_1") (pintype "passive"))
      (node (ref "U3") (pin "72") (pinfunction "P9_6_72") (pintype "bidirectional"))
    )
    (net (code "3") (name "A_A_HLFB_OUT") (class "Default")
      (node (ref "J25") (pin "5") (pinfunction "5-HLFB-_5") (pintype "passive"))
    )
    (net (code "4") (name "A_A_MI_DIR") (class "Default")
      (node (ref "J25") (pin "7") (pinfunction "7-INPUT_A-_7") (pintype "passive"))
      (node (ref "R113") (pin "1") (pinfunction "1_1") (pintype "passive"))
      (node (ref "U47") (pin "3") (pinfunction "C(3)_3") (pintype "input"))
    )
    (net (code "5") (name "A_A_MI_ENABLE") (class "Default")
      (node (ref "J25") (pin "8") (pinfunction "8-ENABLE-_8") (pintype "passive"))
      (node (ref "R114") (pin "1") (pinfunction "1_1") (pintype "passive"))
      (node (ref "U48") (pin "3") (pinfunction "C(3)_3") (pintype "input"))
    )
    (net (code "6") (name "A_A_MI_STEP") (class "Default")
      (node (ref "J25") (pin "6") (pinfunction "6-INPUT_B-_6") (pintype "passive"))
      (node (ref "R109") (pin "1") (pinfunction "1_1") (pintype "passive"))
      (node (ref "U46") (pin "3") (pinfunction "C(3)_3") (pintype "input"))
    )
    (net (code "7") (name "A_A_STEP") (class "Default")
      (node (ref "R110") (pin "1") (pinfunction "1_1") (pintype "passive"))
      (node (ref "U3") (pin "74") (pinfunction "P3_12_74") (pintype "bidirectional"))
    )
    (net (code "8") (name "A_B_DIR") (class "Default")
      (node (ref "R117") (pin "1") (pinfunction "1_1") (pintype "passive"))
      (node (ref "U3") (pin "76") (pinfunction "P3_10_76") (pintype "bidirectional"))
    )
    (net (code "9") (name "A_B_ENABLE") (class "Default")
      (node (ref "R118") (pin "1") (pinfunction "1_1") (pintype "passive"))
      (node (ref "U3") (pin "75") (pinfunction "P3_11_75") (pintype "bidirectional"))
    )
    (net (code "10") (name "A_B_HLFB_OUT") (class "Default")
      (node (ref "J26") (pin "5") (pinfunction "5-HLFB-_5") (pintype "passive"))
    )
    (net (code "11") (name "A_B_MI_DIR") (class "Default")
      (node (ref "J26") (pin "7") (pinfunction "7-INPUT_A-_7") (pintype "passive"))
      (node (ref "R119") (pin "1") (pinfunction "1_1") (pintype "passive"))
      (node (ref "U50") (pin "3") (pinfunction "C(3)_3") (pintype "input"))
    )
    (net (code "12") (name "A_B_MI_ENABLE") (class "Default")
      (node (ref "J26") (pin "8") (pinfunction "8-ENABLE-_8") (pintype "passive"))
      (node (ref "R120") (pin "1") (pinfunction "1_1") (pintype "passive"))
      (node (ref "U51") (pin "3") (pinfunction "C(3)_3") (pintype "input"))
    )
    (net (code "13") (name "A_B_MI_STEP") (class "Default")
      (node (ref "J26") (pin "6") (pinfunction "6-INPUT_B-_6") (pintype "passive"))
      (node (ref "R115") (pin "1") (pinfunction "1_1") (pintype "passive"))
      (node (ref "U49") (pin "3") (pinfunction "C(3)_3") (pintype "input"))
    )
    (net (code "14") (name "A_B_STEP") (class "Default")
      (node (ref "R116") (pin "1") (pinfunction "1_1") (pintype "passive"))
      (node (ref "U3") (pin "77") (pinfunction "P3_9_77") (pintype "bidirectional"))
    )
    (net (code "15") (name "B_MI_DIR") (class "Default")
      (node (ref "J34") (pin "7") (pinfunction "7-INPUT_A-_7") (pintype "passive"))
      (node (ref "R167") (pin "1") (pinfunction "1_1") (pintype "passive"))
      (node (ref "U74") (pin "3") (pinfunction "C(3)_3") (pintype "input"))
    )
    (net (code "16") (name "C58") (class "Default")
      (node (ref "C12") (pin "P$1") (pinfunction "1_P$1") (pintype "passive"))
      (node (ref "RJ1") (pin "4") (pinfunction "CT1_4") (pintype "bidirectional"))
    )
    (net (code "17") (name "C60") (class "Default")
      (node (ref "C13") (pin "P$1") (pinfunction "1_P$1") (pintype "passive"))
      (node (ref "RJ1") (pin "5") (pinfunction "CT2_5") (pintype "bidirectional"))
    )
    (net (code "18") (name "CRS_DV") (class "Default")
      (node (ref "R12") (pin "P$2") (pinfunction "2_P$2") (pintype "passive"))
      (node (ref "U1") (pin "15") (pinfunction "CRS_DV/PHYAD[1:0]_15") (pintype "bidirectional"))
    )
    (net (code "19") (name "C_A_DIR") (class "Default")
      (node (ref "R135") (pin "1") (pinfunction "1_1") (pintype "passive"))
      (node (ref "U3") (pin "58") (pinfunction "P9_0_58") (pintype "bidirectional"))
    )
    (net (code "20") (name "C_A_ENABLE") (class "Default")
      (node (ref "R136") (pin "1") (pinfunction "1_1") (pintype "passive"))
      (node (ref "U3") (pin "57") (pinfunction "P3_15_57") (pintype "bidirectional"))
    )
    (net (code "21") (name "C_A_HLFB_OUT") (class "Default")
      (node (ref "J29") (pin "5") (pinfunction "5-HLFB-_5") (pintype "passive"))
    )
    (net (code "22") (name "C_A_MI_DIR") (class "Default")
      (node (ref "J29") (pin "7") (pinfunction "7-INPUT_A-_7") (pintype "passive"))
      (node (ref "R137") (pin "1") (pinfunction "1_1") (pintype "passive"))
      (node (ref "U59") (pin "3") (pinfunction "C(3)_3") (pintype "input"))
    )
    (net (code "23") (name "C_A_MI_ENABLE") (class "Default")
      (node (ref "J29") (pin "8") (pinfunction "8-ENABLE-_8") (pintype "passive"))
      (node (ref "R138") (pin "1") (pinfunction "1_1") (pintype "passive"))
      (node (ref "U60") (pin "3") (pinfunction "C(3)_3") (pintype "input"))
    )
    (net (code "24") (name "C_A_MI_STEP") (class "Default")
      (node (ref "J29") (pin "6") (pinfunction "6-INPUT_B-_6") (pintype "passive"))
      (node (ref "R133") (pin "1") (pinfunction "1_1") (pintype "passive"))
      (node (ref "U58") (pin "3") (pinfunction "C(3)_3") (pintype "input"))
    )
    (net (code "25") (name "C_A_STEP") (class "Default")
      (node (ref "R134") (pin "1") (pinfunction "1_1") (pintype "passive"))
      (node (ref "U3") (pin "59") (pinfunction "P9_1_59") (pintype "bidirectional"))
    )
    (net (code "26") (name "C_B_DIR") (class "Default")
      (node (ref "R141") (pin "1") (pinfunction "1_1") (pintype "passive"))
      (node (ref "U3") (pin "70") (pinfunction "P9_8_70") (pintype "bidirectional"))
    )
    (net (code "27") (name "C_B_ENABLE") (class "Default")
      (node (ref "R142") (pin "1") (pinfunction "1_1") (pintype "passive"))
      (node (ref "U3") (pin "68") (pinfunction "P2_1/MD_68") (pintype "bidirectional"))
    )
    (net (code "28") (name "C_B_HLFB_OUT") (class "Default")
      (node (ref "J30") (pin "5") (pinfunction "5-HLFB-_5") (pintype "passive"))
    )
    (net (code "29") (name "C_B_MI_DIR") (class "Default")
      (node (ref "J30") (pin "7") (pinfunction "7-INPUT_A-_7") (pintype "passive"))
      (node (ref "R143") (pin "1") (pinfunction "1_1") (pintype "passive"))
      (node (ref "U62") (pin "3") (pinfunction "C(3)_3") (pintype "input"))
    )
    (net (code "30") (name "C_B_MI_ENABLE") (class "Default")
      (node (ref "J30") (pin "8") (pinfunction "8-ENABLE-_8") (pintype "passive"))
      (node (ref "R144") (pin "1") (pinfunction "1_1") (pintype "passive"))
      (node (ref "U63") (pin "3") (pinfunction "C(3)_3") (pintype "input"))
    )
    (net (code "31") (name "C_B_MI_STEP") (class "Default")
      (node (ref "J30") (pin "6") (pinfunction "6-INPUT_B-_6") (pintype "passive"))
      (node (ref "R139") (pin "1") (pinfunction "1_1") (pintype "passive"))
      (node (ref "U61") (pin "3") (pinfunction "C(3)_3") (pintype "input"))
    )
    (net (code "32") (name "C_B_STEP") (class "Default")
      (node (ref "R140") (pin "1") (pinfunction "1_1") (pintype "passive"))
      (node (ref "U3") (pin "71") (pinfunction "P9_7_71") (pintype "bidirectional"))
    )
    (net (code "33") (name "ESTOP") (class "Default")
      (node (ref "R79") (pin "P$2") (pinfunction "2_P$2") (pintype "passive"))
      (node (ref "R80") (pin "P$2") (pinfunction "2_P$2") (pintype "passive"))
      (node (ref "U21") (pin "2") (pinfunction "E(1)_2") (pintype "output"))
      (node (ref "U3") (pin "69") (pinfunction "P2_0(INPUT_ONLY)_69") (pintype "bidirectional"))
    )
    (net (code "34") (name "ESTOP_RET") (class "Default")
      (node (ref "J20") (pin "1") (pinfunction "1_1") (pintype "passive"))
      (node (ref "R78") (pin "P$1") (pinfunction "1_P$1") (pintype "passive"))
    )
    (net (code "35") (name "ETH") (class "Default")
      (node (ref "U1") (pin "16") (pinfunction "REF_CLK_16") (pintype "bidirectional"))
      (node (ref "U3") (pin "9") (pinfunction "P7_1_9") (pintype "bidirectional"))
    )
    (net (code "36") (name "ETH_CRS_DV") (class "Default")
      (node (ref "R12") (pin "P$1") (pinfunction "1_P$1") (pintype "passive"))
      (node (ref "U3") (pin "13") (pinfunction "P7_5_13") (pintype "bidirectional"))
    )
    (net (code "37") (name "ETH_IRQ14") (class "Default")
      (node (ref "R2") (pin "P$1") (pinfunction "1_P$1") (pintype "passive"))
      (node (ref "U1") (pin "18") (pinfunction "INTRP_18") (pintype "bidirectional"))
      (node (ref "U3") (pin "159") (pinfunction "P0_10/AN103_159") (pintype "bidirectional"))
    )
    (net (code "38") (name "ETH_MDC") (class "Default")
      (node (ref "R4") (pin "P$1") (pinfunction "1_P$1") (pintype "passive"))
      (node (ref "U1") (pin "11") (pinfunction "MDC_11") (pintype "input"))
      (node (ref "U3") (pin "4") (pinfunction "P4_3_4") (pintype "bidirectional"))
    )
    (net (code "39") (name "ETH_MDIO") (class "Default")
      (node (ref "R6") (pin "P$1") (pinfunction "1_P$1") (pintype "passive"))
      (node (ref "U1") (pin "10") (pinfunction "MDIO_10") (pintype "bidirectional"))
      (node (ref "U3") (pin "5") (pinfunction "P4_4_5") (pintype "bidirectional"))
    )
    (net (code "40") (name "ETH_RESET") (class "Default")
      (node (ref "C6") (pin "P$1") (pinfunction "1_P$1") (pintype "passive"))
      (node (ref "R3") (pin "P$1") (pinfunction "1_P$1") (pintype "passive"))
      (node (ref "U1") (pin "24") (pinfunction "~{RST}_24") (pintype "input"))
      (node (ref "U3") (pin "172") (pinfunction "P8_6_172") (pintype "bidirectional"))
    )
    (net (code "41") (name "ETH_RXD0") (class "Default")
      (node (ref "R10") (pin "P$1") (pinfunction "1_P$1") (pintype "passive"))
      (node (ref "U3") (pin "10") (pinfunction "P7_2_10") (pintype "bidirectional"))
    )
    (net (code "42") (name "ETH_RXD1") (class "Default")
      (node (ref "R9") (pin "P$1") (pinfunction "1_P$1") (pintype "passive"))
      (node (ref "U3") (pin "11") (pinfunction "P7_3_11") (pintype "bidirectional"))
    )
    (net (code "43") (name "ETH_RX_ER") (class "Default")
      (node (ref "R11") (pin "P$1") (pinfunction "1_P$1") (pintype "passive"))
      (node (ref "U3") (pin "12") (pinfunction "P7_4_12") (pintype "bidirectional"))
    )
    (net (code "44") (name "ETH_TXD0") (class "Default")
      (node (ref "U1") (pin "20") (pinfunction "TXD0_20") (pintype "input"))
      (node (ref "U3") (pin "8") (pinfunction "P7_0_8") (pintype "bidirectional"))
    )
    (net (code "45") (name "ETH_TXD1") (class "Default")
      (node (ref "U1") (pin "21") (pinfunction "TXD1_21") (pintype "bidirectional"))
      (node (ref "U3") (pin "7") (pinfunction "P4_6_7") (pintype "bidirectional"))
    )
    (net (code "46") (name "ETH_TXD_EN") (class "Default")
      (node (ref "U1") (pin "19") (pinfunction "TXEN_19") (pintype "input"))
      (node (ref "U3") (pin "6") (pinfunction "P4_5_6") (pintype "bidirectional"))
    )
    (net (code "47") (name "GND") (class "Default")
      (node (ref "C1") (pin "P$2") (pinfunction "2_P$2") (pintype "passive"))
      (node (ref "C10") (pin "P$2") (pinfunction "2_P$2") (pintype "passive"))
      (node (ref "C11") (pin "P$2") (pinfunction "2_P$2") (pintype "passive"))
      (node (ref "C12") (pin "P$2") (pinfunction "2_P$2") (pintype "passive"))
      (node (ref "C13") (pin "P$2") (pinfunction "2_P$2") (pintype "passive"))
      (node (ref "C14") (pin "P$2") (pinfunction "2_P$2") (pintype "passive"))
      (node (ref "C15") (pin "P$2") (pinfunction "2_P$2") (pintype "passive"))
      (node (ref "C16") (pin "P$2") (pinfunction "2_P$2") (pintype "passive"))
      (node (ref "C17") (pin "P$2") (pinfunction "2_P$2") (pintype "passive"))
      (node (ref "C18") (pin "P$2") (pinfunction "2_P$2") (pintype "passive"))
      (node (ref "C19") (pin "P$1") (pinfunction "1_P$1") (pintype "passive"))
      (node (ref "C2") (pin "P$2") (pinfunction "2_P$2") (pintype "passive"))
      (node (ref "C20") (pin "P$1") (pinfunction "1_P$1") (pintype "passive"))
      (node (ref "C21") (pin "P$1") (pinfunction "1_P$1") (pintype "passive"))
      (node (ref "C22") (pin "P$1") (pinfunction "1_P$1") (pintype "passive"))
      (node (ref "C23") (pin "P$2") (pinfunction "2_P$2") (pintype "passive"))
      (node (ref "C24") (pin "P$1") (pinfunction "1_P$1") (pintype "passive"))
      (node (ref "C25") (pin "P$1") (pinfunction "1_P$1") (pintype "passive"))
      (node (ref "C26") (pin "P$2") (pinfunction "2_P$2") (pintype "passive"))
      (node (ref "C27") (pin "P$1") (pinfunction "1_P$1") (pintype "passive"))
      (node (ref "C28") (pin "P$2") (pinfunction "2_P$2") (pintype "passive"))
      (node (ref "C29") (pin "P$2") (pinfunction "2_P$2") (pintype "passive"))
      (node (ref "C3") (pin "P$2") (pinfunction "2_P$2") (pintype "passive"))
      (node (ref "C30") (pin "P$1") (pinfunction "1_P$1") (pintype "passive"))
      (node (ref "C31") (pin "2") (pinfunction "2_2") (pintype "passive"))
      (node (ref "C32") (pin "P$2") (pinfunction "2_P$2") (pintype "passive"))
      (node (ref "C33") (pin "P$2") (pinfunction "2_P$2") (pintype "passive"))
      (node (ref "C34") (pin "P$1") (pinfunction "1_P$1") (pintype "passive"))
      (node (ref "C35") (pin "P$1") (pinfunction "1_P$1") (pintype "passive"))
      (node (ref "C36") (pin "P$2") (pinfunction "2_P$2") (pintype "passive"))
      (node (ref "C37") (pin "P$2") (pinfunction "2_P$2") (pintype "passive"))
      (node (ref "C38") (pin "P$1") (pinfunction "1_P$1") (pintype "passive"))
      (node (ref "C39") (pin "P$2") (pinfunction "2_P$2") (pintype "passive"))
      (node (ref "C4") (pin "P$2") (pinfunction "2_P$2") (pintype "passive"))
      (node (ref "C40") (pin "P$2") (pinfunction "2_P$2") (pintype "passive"))
      (node (ref "C41") (pin "P$2") (pinfunction "2_P$2") (pintype "passive"))
      (node (ref "C42") (pin "P$2") (pinfunction "2_P$2") (pintype "passive"))
      (node (ref "C43") (pin "P$1") (pinfunction "1_P$1") (pintype "passive"))
      (node (ref "C5") (pin "P$2") (pinfunction "2_P$2") (pintype "passive"))
      (node (ref "C6") (pin "P$2") (pinfunction "2_P$2") (pintype "passive"))
      (node (ref "C7") (pin "P$2") (pinfunction "2_P$2") (pintype "passive"))
      (node (ref "C8") (pin "P$2") (pinfunction "2_P$2") (pintype "passive"))
      (node (ref "C9") (pin "P$2") (pinfunction "2_P$2") (pintype "passive"))
      (node (ref "J1") (pin "6") (pinfunction "SUPPLY_VOLTAGE_GROUND_6") (pintype "power_in"))
      (node (ref "J10") (pin "2") (pinfunction "2_2") (pintype "passive"))
      (node (ref "J11") (pin "2") (pinfunction "2_2") (pintype "passive"))
      (node (ref "J12") (pin "2") (pinfunction "2_2") (pintype "passive"))
      (node (ref "J19") (pin "2") (pinfunction "2_2") (pintype "passive"))
      (node (ref "J2") (pin "P$1") (pinfunction "P$1_P$1") (pintype "bidirectional"))
      (node (ref "J20") (pin "2") (pinfunction "2_2") (pintype "passive"))
      (node (ref "J27") (pin "2") (pinfunction "2_2") (pintype "passive"))
      (node (ref "J28") (pin "2") (pinfunction "2_2") (pintype "passive"))
      (node (ref "J3") (pin "10") (pinfunction "10_10") (pintype "passive"))
      (node (ref "J3") (pin "6") (pinfunction "6_6") (pintype "passive"))
      (node (ref "J3") (pin "8") (pinfunction "8_8") (pintype "passive"))
      (node (ref "J31") (pin "2") (pinfunction "2_2") (pintype "passive"))
      (node (ref "J32") (pin "2") (pinfunction "2_2") (pintype "passive"))
      (node (ref "J39") (pin "P$1") (pinfunction "P$1_P$1") (pintype "bidirectional"))
      (node (ref "J39") (pin "P$11") (pinfunction "P$11_P$11") (pintype "bidirectional"))
      (node (ref "J39") (pin "P$13") (pinfunction "P$13_P$13") (pintype "bidirectional"))
      (node (ref "J39") (pin "P$15") (pinfunction "P$15_P$15") (pintype "bidirectional"))
      (node (ref "J39") (pin "P$17") (pinfunction "P$17_P$17") (pintype "bidirectional"))
      (node (ref "J39") (pin "P$19") (pinfunction "P$19_P$19") (pintype "bidirectional"))
      (node (ref "J39") (pin "P$3") (pinfunction "P$3_P$3") (pintype "bidirectional"))
      (node (ref "J39") (pin "P$5") (pinfunction "P$5_P$5") (pintype "bidirectional"))
      (node (ref "J39") (pin "P$7") (pinfunction "P$7_P$7") (pintype "bidirectional"))
      (node (ref "J39") (pin "P$9") (pinfunction "P$9_P$9") (pintype "bidirectional"))
      (node (ref "J5") (pin "2") (pinfunction "2_2") (pintype "passive"))
      (node (ref "J6") (pin "GND") (pinfunction "GND_GND") (pintype "power_in"))
      (node (ref "J7") (pin "P$5") (pinfunction "GND_P$5") (pintype "bidirectional"))
      (node (ref "J8") (pin "P$12") (pinfunction "P$12_P$12") (pintype "bidirectional"))
      (node (ref "J8") (pin "P$14") (pinfunction "P$14_P$14") (pintype "bidirectional"))
      (node (ref "J8") (pin "P$16") (pinfunction "P$16_P$16") (pintype "bidirectional"))
      (node (ref "J8") (pin "P$18") (pinfunction "P$18_P$18") (pintype "bidirectional"))
      (node (ref "J8") (pin "P$20") (pinfunction "P$20_P$20") (pintype "bidirectional"))
      (node (ref "J8") (pin "P$6") (pinfunction "P$6_P$6") (pintype "bidirectional"))
      (node (ref "LED1") (pin "2") (pinfunction "C_2") (pintype "passive"))
      (node (ref "LED10") (pin "2") (pinfunction "C_2") (pintype "passive"))
      (node (ref "LED11") (pin "2") (pinfunction "C_2") (pintype "passive"))
      (node (ref "LED12") (pin "2") (pinfunction "C_2") (pintype "passive"))
      (node (ref "LED13") (pin "2") (pinfunction "C_2") (pintype "passive"))
      (node (ref "LED14") (pin "2") (pinfunction "C_2") (pintype "passive"))
      (node (ref "LED15") (pin "2") (pinfunction "C_2") (pintype "passive"))
      (node (ref "LED16") (pin "2") (pinfunction "C_2") (pintype "passive"))
      (node (ref "LED3") (pin "2") (pinfunction "C_2") (pintype "passive"))
      (node (ref "LED6") (pin "2") (pinfunction "C_2") (pintype "passive"))
      (node (ref "LED7") (pin "2") (pinfunction "C_2") (pintype "passive"))
      (node (ref "R1") (pin "P$1") (pinfunction "1_P$1") (pintype "passive"))
      (node (ref "R101") (pin "P$1") (pinfunction "1_P$1") (pintype "passive"))
      (node (ref "R21") (pin "P$1") (pinfunction "1_P$1") (pintype "passive"))
      (node (ref "R22") (pin "P$1") (pinfunction "1_P$1") (pintype "passive"))
      (node (ref "R23") (pin "P$1") (pinfunction "1_P$1") (pintype "passive"))
      (node (ref "R24") (pin "P$1") (pinfunction "1_P$1") (pintype "passive"))
      (node (ref "R34") (pin "P$1") (pinfunction "1_P$1") (pintype "passive"))
      (node (ref "R53") (pin "P$1") (pinfunction "1_P$1") (pintype "passive"))
      (node (ref "R56") (pin "P$1") (pinfunction "1_P$1") (pintype "passive"))
      (node (ref "R59") (pin "P$1") (pinfunction "1_P$1") (pintype "passive"))
      (node (ref "R74") (pin "P$1") (pinfunction "1_P$1") (pintype "passive"))
      (node (ref "R77") (pin "P$1") (pinfunction "1_P$1") (pintype "passive"))
      (node (ref "R80") (pin "P$1") (pinfunction "1_P$1") (pintype "passive"))
      (node (ref "R83") (pin "P$1") (pinfunction "1_P$1") (pintype "passive"))
      (node (ref "R98") (pin "P$1") (pinfunction "1_P$1") (pintype "passive"))
      (node (ref "RJ1") (pin "10") (pinfunction "GLO_10") (pintype "bidirectional"))
      (node (ref "RJ1") (pin "8") (pinfunction "P8_8") (pintype "bidirectional"))
      (node (ref "U1") (pin "22") (pinfunction "GND_22") (pintype "power_in"))
      (node (ref "U1") (pin "25") (pinfunction "25_25") (pintype "passive"))
      (node (ref "U10") (pin "2") (pinfunction "E(1)_2") (pintype "output"))
      (node (ref "U11") (pin "2") (pinfunction "E(1)_2") (pintype "output"))
      (node (ref "U12") (pin "2") (pinfunction "E(1)_2") (pintype "output"))
      (node (ref "U13") (pin "2") (pinfunction "E(1)_2") (pintype "output"))
      (node (ref "U14") (pin "2") (pinfunction "E(1)_2") (pintype "output"))
      (node (ref "U15") (pin "2") (pinfunction "E(1)_2") (pintype "output"))
      (node (ref "U16") (pin "2") (pinfunction "E(1)_2") (pintype "output"))
      (node (ref "U17") (pin "2") (pinfunction "E(1)_2") (pintype "output"))
      (node (ref "U2") (pin "2") (pinfunction "GND_2") (pintype "input"))
      (node (ref "U22") (pin "2") (pinfunction "E(1)_2") (pintype "output"))
      (node (ref "U23") (pin "2") (pinfunction "E(1)_2") (pintype "output"))
      (node (ref "U24") (pin "2") (pinfunction "E(1)_2") (pintype "output"))
      (node (ref "U25") (pin "2") (pinfunction "E(1)_2") (pintype "output"))
      (node (ref "U26") (pin "2") (pinfunction "E(1)_2") (pintype "output"))
      (node (ref "U27") (pin "2") (pinfunction "E(1)_2") (pintype "output"))
      (node (ref "U3") (pin "111") (pinfunction "VSS(IO)5_111") (pintype "bidirectional"))
      (node (ref "U3") (pin "124") (pinfunction "VSS(IO)6_124") (pintype "bidirectional"))
      (node (ref "U3") (pin "139") (pinfunction "VSS(IO)7_139") (pintype "bidirectional"))
      (node (ref "U3") (pin "150") (pinfunction "VSS(IO)8_150") (pintype "bidirectional"))
      (node (ref "U3") (pin "153") (pinfunction "VREFL_153") (pintype "bidirectional"))
      (node (ref "U3") (pin "156") (pinfunction "AVSS0_156") (pintype "bidirectional"))
      (node (ref "U3") (pin "157") (pinfunction "VREFL0_157") (pintype "bidirectional"))
      (node (ref "U3") (pin "170") (pinfunction "VSS(IO)9_170") (pintype "bidirectional"))
      (node (ref "U3") (pin "22") (pinfunction "VSS1_22") (pintype "bidirectional"))
      (node (ref "U3") (pin "28") (pinfunction "AVSS_USBHS_28") (pintype "bidirectional"))
      (node (ref "U3") (pin "29") (pinfunction "PVSS_USBHS_29") (pintype "bidirectional"))
      (node (ref "U3") (pin "30") (pinfunction "VSS2_USBHS_30") (pintype "bidirectional"))
      (node (ref "U3") (pin "33") (pinfunction "VSS1_USBHS_33") (pintype "bidirectional"))
      (node (ref "U3") (pin "35") (pinfunction "VSSIO_35") (pintype "bidirectional"))
      (node (ref "U3") (pin "45") (pinfunction "VSS_USB_45") (pintype "bidirectional"))
      (node (ref "U3") (pin "60") (pinfunction "VSS(IO)2_60") (pintype "bidirectional"))
      (node (ref "U3") (pin "63") (pinfunction "VSS(IO/DCDC)_63") (pintype "bidirectional"))
      (node (ref "U3") (pin "66") (pinfunction "VCC_DCDC(IO/DCDC)_66") (pintype "bidirectional"))
      (node (ref "U3") (pin "83") (pinfunction "VSS(IO)3_83") (pintype "bidirectional"))
      (node (ref "U3") (pin "98") (pinfunction "VSS(IO)4_98") (pintype "bidirectional"))
      (node (ref "U34") (pin "2") (pinfunction "E(1)_2") (pintype "output"))
      (node (ref "U35") (pin "2") (pinfunction "E(1)_2") (pintype "output"))
      (node (ref "U36") (pin "2") (pinfunction "E(1)_2") (pintype "output"))
      (node (ref "U37") (pin "2") (pinfunction "E(1)_2") (pintype "output"))
      (node (ref "U38") (pin "2") (pinfunction "E(1)_2") (pintype "output"))
      (node (ref "U39") (pin "2") (pinfunction "E(1)_2") (pintype "output"))
      (node (ref "U46") (pin "2") (pinfunction "E(1)_2") (pintype "output"))
      (node (ref "U47") (pin "2") (pinfunction "E(1)_2") (pintype "output"))
      (node (ref "U48") (pin "2") (pinfunction "E(1)_2") (pintype "output"))
      (node (ref "U49") (pin "2") (pinfunction "E(1)_2") (pintype "output"))
      (node (ref "U50") (pin "2") (pinfunction "E(1)_2") (pintype "output"))
      (node (ref "U51") (pin "2") (pinfunction "E(1)_2") (pintype "output"))
      (node (ref "U58") (pin "2") (pinfunction "E(1)_2") (pintype "output"))
      (node (ref "U59") (pin "2") (pinfunction "E(1)_2") (pintype "output"))
      (node (ref "U6") (pin "2") (pinfunction "E(1)_2") (pintype "output"))
      (node (ref "U60") (pin "2") (pinfunction "E(1)_2") (pintype "output"))
      (node (ref "U61") (pin "2") (pinfunction "E(1)_2") (pintype "output"))
      (node (ref "U62") (pin "2") (pinfunction "E(1)_2") (pintype "output"))
      (node (ref "U63") (pin "2") (pinfunction "E(1)_2") (pintype "output"))
      (node (ref "U7") (pin "2") (pinfunction "E(1)_2") (pintype "output"))
      (node (ref "U70") (pin "2") (pinfunction "E(1)_2") (pintype "output"))
      (node (ref "U71") (pin "2") (pinfunction "E(1)_2") (pintype "output"))
      (node (ref "U72") (pin "2") (pinfunction "E(1)_2") (pintype "output"))
      (node (ref "U73") (pin "2") (pinfunction "E(1)_2") (pintype "output"))
      (node (ref "U74") (pin "2") (pinfunction "E(1)_2") (pintype "output"))
      (node (ref "U75") (pin "2") (pinfunction "E(1)_2") (pintype "output"))
      (node (ref "X1") (pin "2") (pinfunction "2_2") (pintype "bidirectional"))
      (node (ref "X1") (pin "4") (pinfunction "4_4") (pintype "bidirectional"))
      (node (ref "X2") (pin "2") (pinfunction "2_2") (pintype "bidirectional"))
      (node (ref "X2") (pin "4") (pinfunction "4_4") (pintype "bidirectional"))
    )
    (net (code "48") (name "GNDE") (class "Default")
      (node (ref "J1") (pin "S1") (pinfunction "SHIELD_S1") (pintype "passive"))
      (node (ref "J1") (pin "S2") (pinfunction "SHIELD_S2") (pintype "passive"))
      (node (ref "J1") (pin "S3") (pinfunction "SHIELD_S3") (pintype "passive"))
      (node (ref "J1") (pin "S4") (pinfunction "SHIELD_S4") (pintype "passive"))
      (node (ref "J2") (pin "P$4") (pinfunction "P$4_P$4") (pintype "bidirectional"))
      (node (ref "J6") (pin "SHLD1") (pinfunction "SHIELD_1_SHLD1") (pintype "bidirectional"))
      (node (ref "J6") (pin "SHLD2") (pinfunction "SHIELD_2_SHLD2") (pintype "bidirectional"))
      (node (ref "J7") (pin "P$6") (pinfunction "SHIELD1_P$6") (pintype "bidirectional"))
      (node (ref "J7") (pin "P$7") (pinfunction "SHIELD2_P$7") (pintype "bidirectional"))
      (node (ref "J7") (pin "P$8") (pinfunction "SHIELD3_P$8") (pintype "bidirectional"))
      (node (ref "J7") (pin "P$9") (pinfunction "SHIELD4_P$9") (pintype "bidirectional"))
      (node (ref "RJ1") (pin "13") (pinfunction "GNDE0_13") (pintype "bidirectional"))
      (node (ref "RJ1") (pin "14") (pinfunction "GNDE1_14") (pintype "bidirectional"))
    )
    (net (code "49") (name "ID") (class "Default")
      (node (ref "J7") (pin "P$4") (pinfunction "ID_P$4") (pintype "bidirectional"))
    )
    (net (code "50") (name "IIC_1_SCL") (class "Default")
      (node (ref "J8") (pin "P$8") (pinfunction "P$8_P$8") (pintype "bidirectional"))
      (node (ref "R14") (pin "P$2") (pinfunction "2_P$2") (pintype "passive"))
      (node (ref "U3") (pin "132") (pinfunction "P1_0_132") (pintype "bidirectional"))
    )
    (net (code "51") (name "IIC_1_SDA") (class "Default")
      (node (ref "J8") (pin "P$7") (pinfunction "P$7_P$7") (pintype "bidirectional"))
      (node (ref "R15") (pin "P$2") (pinfunction "2_P$2") (pintype "passive"))
      (node (ref "U3") (pin "131") (pinfunction "P1_1_131") (pintype "bidirectional"))
    )
    (net (code "52") (name "LED1{slash}SPEED") (class "Default")
      (node (ref "RJ1") (pin "11") (pinfunction "YLO_11") (pintype "bidirectional"))
      (node (ref "U1") (pin "23") (pinfunction "LED0/ANEN_SPEED_23") (pintype "bidirectional"))
    )
    (net (code "53") (name "LS_01") (class "Default")
      (node (ref "R33") (pin "P$2") (pinfunction "2_P$2") (pintype "passive"))
      (node (ref "R34") (pin "P$2") (pinfunction "2_P$2") (pintype "passive"))
      (node (ref "U3") (pin "50") (pinfunction "P2_6_50") (pintype "bidirectional"))
      (node (ref "U5") (pin "2") (pinfunction "E(1)_2") (pintype "output"))
    )
    (net (code "54") (name "LS_01_RET") (class "Default")
      (node (ref "J32") (pin "1") (pinfunction "1_1") (pintype "passive"))
      (node (ref "R28") (pin "P$1") (pinfunction "1_P$1") (pintype "passive"))
    )
    (net (code "55") (name "LS_02") (class "Default")
      (node (ref "R36") (pin "P$2") (pinfunction "2_P$2") (pintype "passive"))
      (node (ref "R53") (pin "P$2") (pinfunction "2_P$2") (pintype "passive"))
      (node (ref "U3") (pin "51") (pinfunction "P2_5_51") (pintype "bidirectional"))
      (node (ref "U8") (pin "2") (pinfunction "E(1)_2") (pintype "output"))
    )
    (net (code "56") (name "LS_02_RET") (class "Default")
      (node (ref "J31") (pin "1") (pinfunction "1_1") (pintype "passive"))
      (node (ref "R35") (pin "P$1") (pinfunction "1_P$1") (pintype "passive"))
    )
    (net (code "57") (name "LS_03") (class "Default")
      (node (ref "R55") (pin "P$2") (pinfunction "2_P$2") (pintype "passive"))
      (node (ref "R56") (pin "P$2") (pinfunction "2_P$2") (pintype "passive"))
      (node (ref "U3") (pin "53") (pinfunction "P2_3_53") (pintype "bidirectional"))
      (node (ref "U9") (pin "2") (pinfunction "E(1)_2") (pintype "output"))
    )
    (net (code "58") (name "LS_03_RET") (class "Default")
      (node (ref "J28") (pin "1") (pinfunction "1_1") (pintype "passive"))
      (node (ref "R54") (pin "P$1") (pinfunction "1_P$1") (pintype "passive"))
    )
    (net (code "59") (name "LS_04") (class "Default")
      (node (ref "R73") (pin "P$2") (pinfunction "2_P$2") (pintype "passive"))
      (node (ref "R74") (pin "P$2") (pinfunction "2_P$2") (pintype "passive"))
      (node (ref "U19") (pin "2") (pinfunction "E(1)_2") (pintype "output"))
      (node (ref "U3") (pin "54") (pinfunction "P2_2_54") (pintype "bidirectional"))
    )
    (net (code "60") (name "LS_04_RET") (class "Default")
      (node (ref "J27") (pin "1") (pinfunction "1_1") (pintype "passive"))
      (node (ref "R60") (pin "P$1") (pinfunction "1_P$1") (pintype "passive"))
    )
    (net (code "61") (name "LS_05") (class "Default")
      (node (ref "R58") (pin "P$2") (pinfunction "2_P$2") (pintype "passive"))
      (node (ref "R59") (pin "P$2") (pinfunction "2_P$2") (pintype "passive"))
      (node (ref "U18") (pin "2") (pinfunction "E(1)_2") (pintype "output"))
      (node (ref "U3") (pin "81") (pinfunction "P3_5_81") (pintype "bidirectional"))
    )
    (net (code "62") (name "LS_05_RET") (class "Default")
      (node (ref "J19") (pin "1") (pinfunction "1_1") (pintype "passive"))
      (node (ref "R57") (pin "P$1") (pinfunction "1_P$1") (pintype "passive"))
    )
    (net (code "63") (name "LS_06") (class "Default")
      (node (ref "R76") (pin "P$2") (pinfunction "2_P$2") (pintype "passive"))
      (node (ref "R77") (pin "P$2") (pinfunction "2_P$2") (pintype "passive"))
      (node (ref "U20") (pin "2") (pinfunction "E(1)_2") (pintype "output"))
      (node (ref "U3") (pin "82") (pinfunction "P3_4_82") (pintype "bidirectional"))
    )
    (net (code "64") (name "LS_06_RET") (class "Default")
      (node (ref "J12") (pin "1") (pinfunction "1_1") (pintype "passive"))
      (node (ref "R75") (pin "P$1") (pinfunction "1_P$1") (pintype "passive"))
    )
    (net (code "65") (name "LS_07") (class "Default")
      (node (ref "R97") (pin "P$2") (pinfunction "2_P$2") (pintype "passive"))
      (node (ref "R98") (pin "P$2") (pinfunction "2_P$2") (pintype "passive"))
      (node (ref "U29") (pin "2") (pinfunction "E(1)_2") (pintype "output"))
      (node (ref "U3") (pin "86") (pinfunction "P3_2_86") (pintype "bidirectional"))
    )
    (net (code "66") (name "LS_07_RET") (class "Default")
      (node (ref "J11") (pin "1") (pinfunction "1_1") (pintype "passive"))
      (node (ref "R84") (pin "P$1") (pinfunction "1_P$1") (pintype "passive"))
    )
    (net (code "67") (name "LS_08") (class "Default")
      (node (ref "R82") (pin "P$2") (pinfunction "2_P$2") (pintype "passive"))
      (node (ref "R83") (pin "P$2") (pinfunction "2_P$2") (pintype "passive"))
      (node (ref "U28") (pin "2") (pinfunction "E(1)_2") (pintype "output"))
      (node (ref "U3") (pin "87") (pinfunction "P3_1_87") (pintype "bidirectional"))
    )
    (net (code "68") (name "LS_08_RET") (class "Default")
      (node (ref "J5") (pin "1") (pinfunction "1_1") (pintype "passive"))
      (node (ref "R81") (pin "P$1") (pinfunction "1_P$1") (pintype "passive"))
    )
    (net (code "69") (name "LS_09") (class "Default")
      (node (ref "R100") (pin "P$2") (pinfunction "2_P$2") (pintype "passive"))
      (node (ref "R101") (pin "P$2") (pinfunction "2_P$2") (pintype "passive"))
      (node (ref "U3") (pin "92") (pinfunction "P1_11_92") (pintype "bidirectional"))
      (node (ref "U30") (pin "2") (pinfunction "E(1)_2") (pintype "output"))
    )
    (net (code "70") (name "LS_09_RET") (class "Default")
      (node (ref "J10") (pin "1") (pinfunction "1_1") (pintype "passive"))
      (node (ref "R99") (pin "P$1") (pinfunction "1_P$1") (pintype "passive"))
    )
    (net (code "71") (name "NC") (class "Default")
      (node (ref "RJ1") (pin "7") (pinfunction "P7_7") (pintype "bidirectional"))
      (node (ref "U3") (pin "79") (pinfunction "P3_7_79") (pintype "bidirectional"))
      (node (ref "U3") (pin "80") (pinfunction "P3_6_80") (pintype "bidirectional"))
      (node (ref "U3") (pin "85") (pinfunction "P3_3_85") (pintype "bidirectional"))
    )
    (net (code "72") (name "Net-(C8-1)") (class "Default")
      (node (ref "C8") (pin "P$1") (pinfunction "1_P$1") (pintype "passive"))
      (node (ref "C9") (pin "P$1") (pinfunction "1_P$1") (pintype "passive"))
      (node (ref "FB1") (pin "2") (pinfunction "P$2_2") (pintype "bidirectional"))
      (node (ref "U1") (pin "2") (pinfunction "VDDA_3.3_2") (pintype "power_in"))
    )
    (net (code "73") (name "Net-(C24-2)") (class "Default")
      (node (ref "C24") (pin "P$2") (pinfunction "2_P$2") (pintype "passive"))
      (node (ref "U3") (pin "148") (pinfunction "VCL2_148") (pintype "bidirectional"))
    )
    (net (code "74") (name "Net-(C28-1)") (class "Default")
      (node (ref "C28") (pin "P$1") (pinfunction "1_P$1") (pintype "passive"))
      (node (ref "J7") (pin "P$1") (pinfunction "VBUS_P$1") (pintype "bidirectional"))
      (node (ref "R16") (pin "P$2") (pinfunction "2_P$2") (pintype "passive"))
      (node (ref "R21") (pin "P$2") (pinfunction "2_P$2") (pintype "passive"))
    )
    (net (code "75") (name "Net-(C33-1)") (class "Default")
      (node (ref "C33") (pin "P$1") (pinfunction "1_P$1") (pintype "passive"))
      (node (ref "U3") (pin "19") (pinfunction "VCLO_19") (pintype "bidirectional"))
    )
    (net (code "76") (name "Net-(C42-1)") (class "Default")
      (node (ref "C42") (pin "P$1") (pinfunction "1_P$1") (pintype "passive"))
      (node (ref "U3") (pin "62") (pinfunction "VCL1_62") (pintype "bidirectional"))
    )
    (net (code "77") (name "Net-(J7-D+)") (class "Default")
      (node (ref "J7") (pin "P$3") (pinfunction "D+_P$3") (pintype "bidirectional"))
      (node (ref "R18") (pin "P$2") (pinfunction "2_P$2") (pintype "passive"))
    )
    (net (code "78") (name "Net-(J7-D-)") (class "Default")
      (node (ref "J7") (pin "P$2") (pinfunction "D-_P$2") (pintype "bidirectional"))
      (node (ref "R17") (pin "P$2") (pinfunction "2_P$2") (pintype "passive"))
    )
    (net (code "79") (name "Net-(LED1-A)") (class "Default")
      (node (ref "LED1") (pin "1") (pinfunction "A_1") (pintype "passive"))
      (node (ref "R5") (pin "P$1") (pinfunction "1_P$1") (pintype "passive"))
    )
    (net (code "80") (name "Net-(LED3-A)") (class "Default")
      (node (ref "LED3") (pin "1") (pinfunction "A_1") (pintype "passive"))
      (node (ref "R33") (pin "P$1") (pinfunction "1_P$1") (pintype "passive"))
    )
    (net (code "81") (name "Net-(LED4-A)") (class "Default")
      (node (ref "LED4") (pin "1") (pinfunction "A_1") (pintype "passive"))
      (node (ref "R32") (pin "P$1") (pinfunction "1_P$1") (pintype "passive"))
    )
    (net (code "82") (name "Net-(LED4-C)") (class "Default")
      (node (ref "LED4") (pin "2") (pinfunction "C_2") (pintype "passive"))
      (node (ref "U$1") (pin "P$1") (pinfunction "VC-_P$1") (pintype "bidirectional"))
      (node (ref "U6") (pin "3") (pinfunction "C(3)_3") (pintype "input"))
    )
    (net (code "83") (name "Net-(LED5-A)") (class "Default")
      (node (ref "LED5") (pin "1") (pinfunction "A_1") (pintype "passive"))
      (node (ref "R31") (pin "P$1") (pinfunction "1_P$1") (pintype "passive"))
    )
    (net (code "84") (name "Net-(LED5-C)") (class "Default")
      (node (ref "LED5") (pin "2") (pinfunction "C_2") (pintype "passive"))
      (node (ref "U$2") (pin "P$1") (pinfunction "VC-_P$1") (pintype "bidirectional"))
      (node (ref "U7") (pin "3") (pinfunction "C(3)_3") (pintype "input"))
    )
    (net (code "85") (name "Net-(LED6-A)") (class "Default")
      (node (ref "LED6") (pin "1") (pinfunction "A_1") (pintype "passive"))
      (node (ref "R36") (pin "P$1") (pinfunction "1_P$1") (pintype "passive"))
    )
    (net (code "86") (name "Net-(LED7-A)") (class "Default")
      (node (ref "LED7") (pin "1") (pinfunction "A_1") (pintype "passive"))
      (node (ref "R55") (pin "P$1") (pinfunction "1_P$1") (pintype "passive"))
    )
    (net (code "87") (name "Net-(LED8-A)") (class "Default")
      (node (ref "LED8") (pin "1") (pinfunction "A_1") (pintype "passive"))
      (node (ref "R52") (pin "P$1") (pinfunction "1_P$1") (pintype "passive"))
    )
    (net (code "88") (name "Net-(LED8-C)") (class "Default")
      (node (ref "LED8") (pin "2") (pinfunction "C_2") (pintype "passive"))
      (node (ref "U$7") (pin "P$1") (pinfunction "VC-_P$1") (pintype "bidirectional"))
      (node (ref "U16") (pin "3") (pinfunction "C(3)_3") (pintype "input"))
    )
    (net (code "89") (name "Net-(LED9-A)") (class "Default")
      (node (ref "LED9") (pin "1") (pinfunction "A_1") (pintype "passive"))
      (node (ref "R51") (pin "P$1") (pinfunction "1_P$1") (pintype "passive"))
    )
    (net (code "90") (name "Net-(LED9-C)") (class "Default")
      (node (ref "LED9") (pin "2") (pinfunction "C_2") (pintype "passive"))
      (node (ref "U$8") (pin "P$1") (pinfunction "VC-_P$1") (pintype "bidirectional"))
      (node (ref "U17") (pin "3") (pinfunction "C(3)_3") (pintype "input"))
    )
    (net (code "91") (name "Net-(LED10-A)") (class "Default")
      (node (ref "LED10") (pin "1") (pinfunction "A_1") (pintype "passive"))
      (node (ref "R58") (pin "P$1") (pinfunction "1_P$1") (pintype "passive"))
    )
    (net (code "92") (name "Net-(LED11-A)") (class "Default")
      (node (ref "LED11") (pin "1") (pinfunction "A_1") (pintype "passive"))
      (node (ref "R73") (pin "P$1") (pinfunction "1_P$1") (pintype "passive"))
    )
    (net (code "93") (name "Net-(LED12-A)") (class "Default")
      (node (ref "LED12") (pin "1") (pinfunction "A_1") (pintype "passive"))
      (node (ref "R76") (pin "P$1") (pinfunction "1_P$1") (pintype "passive"))
    )
    (net (code "94") (name "Net-(LED13-A)") (class "Default")
      (node (ref "LED13") (pin "1") (pinfunction "A_1") (pintype "passive"))
      (node (ref "R79") (pin "P$1") (pinfunction "1_P$1") (pintype "passive"))
    )
    (net (code "95") (name "Net-(LED14-A)") (class "Default")
      (node (ref "LED14") (pin "1") (pinfunction "A_1") (pintype "passive"))
      (node (ref "R82") (pin "P$1") (pinfunction "1_P$1") (pintype "passive"))
    )
    (net (code "96") (name "Net-(LED15-A)") (class "Default")
      (node (ref "LED15") (pin "1") (pinfunction "A_1") (pintype "passive"))
      (node (ref "R97") (pin "P$1") (pinfunction "1_P$1") (pintype "passive"))
    )
    (net (code "97") (name "Net-(LED16-A)") (class "Default")
      (node (ref "LED16") (pin "1") (pinfunction "A_1") (pintype "passive"))
      (node (ref "R100") (pin "P$1") (pinfunction "1_P$1") (pintype "passive"))
    )
    (net (code "98") (name "Net-(R22-2)") (class "Default")
      (node (ref "R22") (pin "P$2") (pinfunction "2_P$2") (pintype "passive"))
      (node (ref "U3") (pin "27") (pinfunction "USBHS_RREF_27") (pintype "bidirectional"))
    )
    (net (code "99") (name "Net-(R23-2)") (class "Default")
      (node (ref "R23") (pin "P$2") (pinfunction "2_P$2") (pintype "passive"))
      (node (ref "U3") (pin "64") (pinfunction "VLO1(DCDC)_64") (pintype "bidirectional"))
    )
    (net (code "100") (name "Net-(R24-2)") (class "Default")
      (node (ref "R24") (pin "P$2") (pinfunction "2_P$2") (pintype "passive"))
      (node (ref "U3") (pin "65") (pinfunction "VLO2(DCDC)_65") (pintype "bidirectional"))
    )
    (net (code "101") (name "Net-(R28-2)") (class "Default")
      (node (ref "R28") (pin "P$2") (pinfunction "2_P$2") (pintype "passive"))
      (node (ref "U5") (pin "1") (pinfunction "B(2)_1") (pintype "input"))
    )
    (net (code "102") (name "Net-(R29-2)") (class "Default")
      (node (ref "R29") (pin "P$2") (pinfunction "2_P$2") (pintype "passive"))
      (node (ref "U6") (pin "1") (pinfunction "B(2)_1") (pintype "input"))
    )
    (net (code "103") (name "Net-(R30-2)") (class "Default")
      (node (ref "R30") (pin "P$2") (pinfunction "2_P$2") (pintype "passive"))
      (node (ref "U7") (pin "1") (pinfunction "B(2)_1") (pintype "input"))
    )
    (net (code "104") (name "Net-(R35-2)") (class "Default")
      (node (ref "R35") (pin "P$2") (pinfunction "2_P$2") (pintype "passive"))
      (node (ref "U8") (pin "1") (pinfunction "B(2)_1") (pintype "input"))
    )
    (net (code "105") (name "Net-(R49-2)") (class "Default")
      (node (ref "R49") (pin "P$2") (pinfunction "2_P$2") (pintype "passive"))
      (node (ref "U16") (pin "1") (pinfunction "B(2)_1") (pintype "input"))
    )
    (net (code "106") (name "Net-(R50-2)") (class "Default")
      (node (ref "R50") (pin "P$2") (pinfunction "2_P$2") (pintype "passive"))
      (node (ref "U17") (pin "1") (pinfunction "B(2)_1") (pintype "input"))
    )
    (net (code "107") (name "Net-(R54-2)") (class "Default")
      (node (ref "R54") (pin "P$2") (pinfunction "2_P$2") (pintype "passive"))
      (node (ref "U9") (pin "1") (pinfunction "B(2)_1") (pintype "input"))
    )
    (net (code "108") (name "Net-(R57-2)") (class "Default")
      (node (ref "R57") (pin "P$2") (pinfunction "2_P$2") (pintype "passive"))
      (node (ref "U18") (pin "1") (pinfunction "B(2)_1") (pintype "input"))
    )
    (net (code "109") (name "Net-(R60-2)") (class "Default")
      (node (ref "R60") (pin "P$2") (pinfunction "2_P$2") (pintype "passive"))
      (node (ref "U19") (pin "1") (pinfunction "B(2)_1") (pintype "input"))
    )
    (net (code "110") (name "Net-(R75-2)") (class "Default")
      (node (ref "R75") (pin "P$2") (pinfunction "2_P$2") (pintype "passive"))
      (node (ref "U20") (pin "1") (pinfunction "B(2)_1") (pintype "input"))
    )
    (net (code "111") (name "Net-(R78-2)") (class "Default")
      (node (ref "R78") (pin "P$2") (pinfunction "2_P$2") (pintype "passive"))
      (node (ref "U21") (pin "1") (pinfunction "B(2)_1") (pintype "input"))
    )
    (net (code "112") (name "Net-(R81-2)") (class "Default")
      (node (ref "R81") (pin "P$2") (pinfunction "2_P$2") (pintype "passive"))
      (node (ref "U28") (pin "1") (pinfunction "B(2)_1") (pintype "input"))
    )
    (net (code "113") (name "Net-(R84-2)") (class "Default")
      (node (ref "R84") (pin "P$2") (pinfunction "2_P$2") (pintype "passive"))
      (node (ref "U29") (pin "1") (pinfunction "B(2)_1") (pintype "input"))
    )
    (net (code "114") (name "Net-(R99-2)") (class "Default")
      (node (ref "R99") (pin "P$2") (pinfunction "2_P$2") (pintype "passive"))
      (node (ref "U30") (pin "1") (pinfunction "B(2)_1") (pintype "input"))
    )
    (net (code "115") (name "Net-(U10-B(2))") (class "Default")
      (node (ref "R38") (pin "2") (pinfunction "2_2") (pintype "passive"))
      (node (ref "U10") (pin "1") (pinfunction "B(2)_1") (pintype "input"))
    )
    (net (code "116") (name "Net-(U11-B(2))") (class "Default")
      (node (ref "R39") (pin "2") (pinfunction "2_2") (pintype "passive"))
      (node (ref "U11") (pin "1") (pinfunction "B(2)_1") (pintype "input"))
    )
    (net (code "117") (name "Net-(U12-B(2))") (class "Default")
      (node (ref "R40") (pin "2") (pinfunction "2_2") (pintype "passive"))
      (node (ref "U12") (pin "1") (pinfunction "B(2)_1") (pintype "input"))
    )
    (net (code "118") (name "Net-(U13-B(2))") (class "Default")
      (node (ref "R44") (pin "2") (pinfunction "2_2") (pintype "passive"))
      (node (ref "U13") (pin "1") (pinfunction "B(2)_1") (pintype "input"))
    )
    (net (code "119") (name "Net-(U14-B(2))") (class "Default")
      (node (ref "R45") (pin "2") (pinfunction "2_2") (pintype "passive"))
      (node (ref "U14") (pin "1") (pinfunction "B(2)_1") (pintype "input"))
    )
    (net (code "120") (name "Net-(U15-B(2))") (class "Default")
      (node (ref "R46") (pin "2") (pinfunction "2_2") (pintype "passive"))
      (node (ref "U15") (pin "1") (pinfunction "B(2)_1") (pintype "input"))
    )
    (net (code "121") (name "Net-(U22-B(2))") (class "Default")
      (node (ref "R62") (pin "2") (pinfunction "2_2") (pintype "passive"))
      (node (ref "U22") (pin "1") (pinfunction "B(2)_1") (pintype "input"))
    )
    (net (code "122") (name "Net-(U23-B(2))") (class "Default")
      (node (ref "R63") (pin "2") (pinfunction "2_2") (pintype "passive"))
      (node (ref "U23") (pin "1") (pinfunction "B(2)_1") (pintype "input"))
    )
    (net (code "123") (name "Net-(U24-B(2))") (class "Default")
      (node (ref "R64") (pin "2") (pinfunction "2_2") (pintype "passive"))
      (node (ref "U24") (pin "1") (pinfunction "B(2)_1") (pintype "input"))
    )
    (net (code "124") (name "Net-(U25-B(2))") (class "Default")
      (node (ref "R68") (pin "2") (pinfunction "2_2") (pintype "passive"))
      (node (ref "U25") (pin "1") (pinfunction "B(2)_1") (pintype "input"))
    )
    (net (code "125") (name "Net-(U26-B(2))") (class "Default")
      (node (ref "R69") (pin "2") (pinfunction "2_2") (pintype "passive"))
      (node (ref "U26") (pin "1") (pinfunction "B(2)_1") (pintype "input"))
    )
    (net (code "126") (name "Net-(U27-B(2))") (class "Default")
      (node (ref "R70") (pin "2") (pinfunction "2_2") (pintype "passive"))
      (node (ref "U27") (pin "1") (pinfunction "B(2)_1") (pintype "input"))
    )
    (net (code "127") (name "Net-(U34-B(2))") (class "Default")
      (node (ref "R86") (pin "2") (pinfunction "2_2") (pintype "passive"))
      (node (ref "U34") (pin "1") (pinfunction "B(2)_1") (pintype "input"))
    )
    (net (code "128") (name "Net-(U35-B(2))") (class "Default")
      (node (ref "R87") (pin "2") (pinfunction "2_2") (pintype "passive"))
      (node (ref "U35") (pin "1") (pinfunction "B(2)_1") (pintype "input"))
    )
    (net (code "129") (name "Net-(U36-B(2))") (class "Default")
      (node (ref "R88") (pin "2") (pinfunction "2_2") (pintype "passive"))
      (node (ref "U36") (pin "1") (pinfunction "B(2)_1") (pintype "input"))
    )
    (net (code "130") (name "Net-(U37-B(2))") (class "Default")
      (node (ref "R92") (pin "2") (pinfunction "2_2") (pintype "passive"))
      (node (ref "U37") (pin "1") (pinfunction "B(2)_1") (pintype "input"))
    )
    (net (code "131") (name "Net-(U38-B(2))") (class "Default")
      (node (ref "R93") (pin "2") (pinfunction "2_2") (pintype "passive"))
      (node (ref "U38") (pin "1") (pinfunction "B(2)_1") (pintype "input"))
    )
    (net (code "132") (name "Net-(U39-B(2))") (class "Default")
      (node (ref "R94") (pin "2") (pinfunction "2_2") (pintype "passive"))
      (node (ref "U39") (pin "1") (pinfunction "B(2)_1") (pintype "input"))
    )
    (net (code "133") (name "Net-(U46-B(2))") (class "Default")
      (node (ref "R110") (pin "2") (pinfunction "2_2") (pintype "passive"))
      (node (ref "U46") (pin "1") (pinfunction "B(2)_1") (pintype "input"))
    )
    (net (code "134") (name "Net-(U47-B(2))") (class "Default")
      (node (ref "R111") (pin "2") (pinfunction "2_2") (pintype "passive"))
      (node (ref "U47") (pin "1") (pinfunction "B(2)_1") (pintype "input"))
    )
    (net (code "135") (name "Net-(U48-B(2))") (class "Default")
      (node (ref "R112") (pin "2") (pinfunction "2_2") (pintype "passive"))
      (node (ref "U48") (pin "1") (pinfunction "B(2)_1") (pintype "input"))
    )
    (net (code "136") (name "Net-(U49-B(2))") (class "Default")
      (node (ref "R116") (pin "2") (pinfunction "2_2") (pintype "passive"))
      (node (ref "U49") (pin "1") (pinfunction "B(2)_1") (pintype "input"))
    )
    (net (code "137") (name "Net-(U50-B(2))") (class "Default")
      (node (ref "R117") (pin "2") (pinfunction "2_2") (pintype "passive"))
      (node (ref "U50") (pin "1") (pinfunction "B(2)_1") (pintype "input"))
    )
    (net (code "138") (name "Net-(U51-B(2))") (class "Default")
      (node (ref "R118") (pin "2") (pinfunction "2_2") (pintype "passive"))
      (node (ref "U51") (pin "1") (pinfunction "B(2)_1") (pintype "input"))
    )
    (net (code "139") (name "Net-(U58-B(2))") (class "Default")
      (node (ref "R134") (pin "2") (pinfunction "2_2") (pintype "passive"))
      (node (ref "U58") (pin "1") (pinfunction "B(2)_1") (pintype "input"))
    )
    (net (code "140") (name "Net-(U59-B(2))") (class "Default")
      (node (ref "R135") (pin "2") (pinfunction "2_2") (pintype "passive"))
      (node (ref "U59") (pin "1") (pinfunction "B(2)_1") (pintype "input"))
    )
    (net (code "141") (name "Net-(U60-B(2))") (class "Default")
      (node (ref "R136") (pin "2") (pinfunction "2_2") (pintype "passive"))
      (node (ref "U60") (pin "1") (pinfunction "B(2)_1") (pintype "input"))
    )
    (net (code "142") (name "Net-(U61-B(2))") (class "Default")
      (node (ref "R140") (pin "2") (pinfunction "2_2") (pintype "passive"))
      (node (ref "U61") (pin "1") (pinfunction "B(2)_1") (pintype "input"))
    )
    (net (code "143") (name "Net-(U62-B(2))") (class "Default")
      (node (ref "R141") (pin "2") (pinfunction "2_2") (pintype "passive"))
      (node (ref "U62") (pin "1") (pinfunction "B(2)_1") (pintype "input"))
    )
    (net (code "144") (name "Net-(U63-B(2))") (class "Default")
      (node (ref "R142") (pin "2") (pinfunction "2_2") (pintype "passive"))
      (node (ref "U63") (pin "1") (pinfunction "B(2)_1") (pintype "input"))
    )
    (net (code "145") (name "Net-(U70-B(2))") (class "Default")
      (node (ref "R158") (pin "2") (pinfunction "2_2") (pintype "passive"))
      (node (ref "U70") (pin "1") (pinfunction "B(2)_1") (pintype "input"))
    )
    (net (code "146") (name "Net-(U71-B(2))") (class "Default")
      (node (ref "R159") (pin "2") (pinfunction "2_2") (pintype "passive"))
      (node (ref "U71") (pin "1") (pinfunction "B(2)_1") (pintype "input"))
    )
    (net (code "147") (name "Net-(U72-B(2))") (class "Default")
      (node (ref "R160") (pin "2") (pinfunction "2_2") (pintype "passive"))
      (node (ref "U72") (pin "1") (pinfunction "B(2)_1") (pintype "input"))
    )
    (net (code "148") (name "Net-(U73-B(2))") (class "Default")
      (node (ref "R164") (pin "2") (pinfunction "2_2") (pintype "passive"))
      (node (ref "U73") (pin "1") (pinfunction "B(2)_1") (pintype "input"))
    )
    (net (code "149") (name "Net-(U74-B(2))") (class "Default")
      (node (ref "R165") (pin "2") (pinfunction "2_2") (pintype "passive"))
      (node (ref "U74") (pin "1") (pinfunction "B(2)_1") (pintype "input"))
    )
    (net (code "150") (name "Net-(U75-B(2))") (class "Default")
      (node (ref "R166") (pin "2") (pinfunction "2_2") (pintype "passive"))
      (node (ref "U75") (pin "1") (pinfunction "B(2)_1") (pintype "input"))
    )
    (net (code "151") (name "P0_00") (class "Default")
      (node (ref "J4") (pin "P$2") (pinfunction "P$2_P$2") (pintype "bidirectional"))
      (node (ref "U3") (pin "169") (pinfunction "P0_0/AN0\\00_169") (pintype "bidirectional"))
    )
    (net (code "152") (name "P0_01") (class "Default")
      (node (ref "J4") (pin "P$1") (pinfunction "P$1_P$1") (pintype "bidirectional"))
      (node (ref "U3") (pin "168") (pinfunction "P0_1/AN001_168") (pintype "bidirectional"))
    )
    (net (code "153") (name "P0_02") (class "Default")
      (node (ref "J39") (pin "P$20") (pinfunction "P$20_P$20") (pintype "bidirectional"))
      (node (ref "R25") (pin "P$1") (pinfunction "1_P$1") (pintype "passive"))
      (node (ref "U3") (pin "167") (pinfunction "P0_2/AN002_167") (pintype "bidirectional"))
    )
    (net (code "154") (name "P0_03") (class "Default")
      (node (ref "J39") (pin "P$18") (pinfunction "P$18_P$18") (pintype "bidirectional"))
      (node (ref "R26") (pin "P$1") (pinfunction "1_P$1") (pintype "passive"))
      (node (ref "U3") (pin "166") (pinfunction "P0_3/PGAVSS000_166") (pintype "bidirectional"))
    )
    (net (code "155") (name "P0_04") (class "Default")
      (node (ref "J39") (pin "P$16") (pinfunction "P$16_P$16") (pintype "bidirectional"))
      (node (ref "R27") (pin "P$1") (pinfunction "1_P$1") (pintype "passive"))
      (node (ref "U3") (pin "165") (pinfunction "P0_4/AN100_165") (pintype "bidirectional"))
    )
    (net (code "156") (name "P0_05") (class "Default")
      (node (ref "J39") (pin "P$14") (pinfunction "P$14_P$14") (pintype "bidirectional"))
      (node (ref "R102") (pin "P$1") (pinfunction "1_P$1") (pintype "passive"))
      (node (ref "U3") (pin "164") (pinfunction "P0_5/AN101_164") (pintype "bidirectional"))
    )
    (net (code "157") (name "P0_06") (class "Default")
      (node (ref "J39") (pin "P$12") (pinfunction "P$12_P$12") (pintype "bidirectional"))
      (node (ref "R103") (pin "P$1") (pinfunction "1_P$1") (pintype "passive"))
      (node (ref "U3") (pin "163") (pinfunction "P0_6/AN102_163") (pintype "bidirectional"))
    )
    (net (code "158") (name "P0_07") (class "Default")
      (node (ref "J39") (pin "P$10") (pinfunction "P$10_P$10") (pintype "bidirectional"))
      (node (ref "R104") (pin "P$1") (pinfunction "1_P$1") (pintype "passive"))
      (node (ref "U3") (pin "162") (pinfunction "P0_7/PGVSS100_162") (pintype "bidirectional"))
    )
    (net (code "159") (name "P0_08") (class "Default")
      (node (ref "J39") (pin "P$8") (pinfunction "P$8_P$8") (pintype "bidirectional"))
      (node (ref "R105") (pin "P$1") (pinfunction "1_P$1") (pintype "passive"))
      (node (ref "U3") (pin "161") (pinfunction "P0_8/AN003_161") (pintype "bidirectional"))
    )
    (net (code "160") (name "P0_09") (class "Default")
      (node (ref "J39") (pin "P$6") (pinfunction "P$6_P$6") (pintype "bidirectional"))
      (node (ref "R106") (pin "P$1") (pinfunction "1_P$1") (pintype "passive"))
      (node (ref "U3") (pin "160") (pinfunction "P0_9/AN004_160") (pintype "bidirectional"))
    )
    (net (code "161") (name "P0_14") (class "Default")
      (node (ref "J39") (pin "P$4") (pinfunction "P$4_P$4") (pintype "bidirectional"))
      (node (ref "R107") (pin "P$1") (pinfunction "1_P$1") (pintype "passive"))
      (node (ref "U3") (pin "152") (pinfunction "P0_14/DA0/AN005/AN105_152") (pintype "bidirectional"))
    )
    (net (code "162") (name "P0_15") (class "Default")
      (node (ref "J39") (pin "P$2") (pinfunction "P$2_P$2") (pintype "bidirectional"))
      (node (ref "R108") (pin "P$1") (pinfunction "1_P$1") (pintype "passive"))
      (node (ref "U3") (pin "151") (pinfunction "P0_15/DA1/AN006/AN106_151") (pintype "bidirectional"))
    )
    (net (code "163") (name "P1_02") (class "Default")
      (node (ref "J8") (pin "P$10") (pinfunction "P$10_P$10") (pintype "bidirectional"))
      (node (ref "U3") (pin "130") (pinfunction "P1_2_130") (pintype "bidirectional"))
    )
    (net (code "164") (name "P1_03") (class "Default")
      (node (ref "J8") (pin "P$9") (pinfunction "P$9_P$9") (pintype "bidirectional"))
      (node (ref "U3") (pin "129") (pinfunction "P1_3_129") (pintype "bidirectional"))
    )
    (net (code "165") (name "P1_04") (class "Default")
      (node (ref "J8") (pin "P$11") (pinfunction "P$11_P$11") (pintype "bidirectional"))
      (node (ref "U3") (pin "128") (pinfunction "P1_4_128") (pintype "bidirectional"))
    )
    (net (code "166") (name "P1_05") (class "Default")
      (node (ref "J8") (pin "P$13") (pinfunction "P$13_P$13") (pintype "bidirectional"))
      (node (ref "U3") (pin "127") (pinfunction "P1_5_127") (pintype "bidirectional"))
    )
    (net (code "167") (name "P1_06") (class "Default")
      (node (ref "J8") (pin "P$15") (pinfunction "P$15_P$15") (pintype "bidirectional"))
      (node (ref "U3") (pin "126") (pinfunction "P1_6_126") (pintype "bidirectional"))
    )
    (net (code "168") (name "P1_07") (class "Default")
      (node (ref "J8") (pin "P$17") (pinfunction "P$17_P$17") (pintype "bidirectional"))
      (node (ref "U3") (pin "125") (pinfunction "P1_7_125") (pintype "bidirectional"))
    )
    (net (code "169") (name "P4_00") (class "Default")
      (node (ref "J4") (pin "P$7") (pinfunction "P$7_P$7") (pintype "bidirectional"))
      (node (ref "U3") (pin "1") (pinfunction "P4_0_1") (pintype "bidirectional"))
    )
    (net (code "170") (name "P4_01") (class "Default")
      (node (ref "J4") (pin "P$8") (pinfunction "P$8_P$8") (pintype "bidirectional"))
      (node (ref "U3") (pin "2") (pinfunction "P4_1_2") (pintype "bidirectional"))
    )
    (net (code "171") (name "P4_02") (class "Default")
      (node (ref "J4") (pin "P$9") (pinfunction "P$9_P$9") (pintype "bidirectional"))
      (node (ref "U3") (pin "3") (pinfunction "P4_2_3") (pintype "bidirectional"))
    )
    (net (code "172") (name "P4_08") (class "Default")
      (node (ref "J4") (pin "P$20") (pinfunction "P$20_P$20") (pintype "bidirectional"))
      (node (ref "U3") (pin "43") (pinfunction "P4_8_43") (pintype "bidirectional"))
    )
    (net (code "173") (name "P4_09") (class "Default")
      (node (ref "J4") (pin "P$19") (pinfunction "P$19_P$19") (pintype "bidirectional"))
      (node (ref "U3") (pin "42") (pinfunction "P4_9_42") (pintype "bidirectional"))
    )
    (net (code "174") (name "P4_10") (class "Default")
      (node (ref "J4") (pin "P$18") (pinfunction "P$18_P$18") (pintype "bidirectional"))
      (node (ref "U3") (pin "41") (pinfunction "P4_10_41") (pintype "bidirectional"))
    )
    (net (code "175") (name "P4_11") (class "Default")
      (node (ref "J4") (pin "P$17") (pinfunction "P$17_P$17") (pintype "bidirectional"))
      (node (ref "U3") (pin "40") (pinfunction "P4_11_40") (pintype "bidirectional"))
    )
    (net (code "176") (name "P4_12") (class "Default")
      (node (ref "J4") (pin "P$16") (pinfunction "P$16_P$16") (pintype "bidirectional"))
      (node (ref "U3") (pin "39") (pinfunction "P4_12_39") (pintype "bidirectional"))
    )
    (net (code "177") (name "P4_13") (class "Default")
      (node (ref "J4") (pin "P$15") (pinfunction "P$15_P$15") (pintype "bidirectional"))
      (node (ref "U3") (pin "38") (pinfunction "P4_13_38") (pintype "bidirectional"))
    )
    (net (code "178") (name "P4_14") (class "Default")
      (node (ref "J4") (pin "P$14") (pinfunction "P$14_P$14") (pintype "bidirectional"))
      (node (ref "U3") (pin "37") (pinfunction "P4_14_37") (pintype "bidirectional"))
    )
    (net (code "179") (name "P4_15") (class "Default")
      (node (ref "J4") (pin "P$13") (pinfunction "P$13_P$13") (pintype "bidirectional"))
      (node (ref "U3") (pin "36") (pinfunction "P4_15_36") (pintype "bidirectional"))
    )
    (net (code "180") (name "P5_11") (class "Default")
      (node (ref "J4") (pin "P$6") (pinfunction "P$6_P$6") (pintype "bidirectional"))
      (node (ref "U3") (pin "176") (pinfunction "P5_11_176") (pintype "bidirectional"))
    )
    (net (code "181") (name "P5_12") (class "Default")
      (node (ref "J4") (pin "P$5") (pinfunction "P$5_P$5") (pintype "bidirectional"))
      (node (ref "U3") (pin "175") (pinfunction "P5_12_175") (pintype "bidirectional"))
    )
    (net (code "182") (name "P5_13") (class "Default")
      (node (ref "J4") (pin "P$4") (pinfunction "P$4_P$4") (pintype "bidirectional"))
      (node (ref "U3") (pin "174") (pinfunction "P5_13_174") (pintype "bidirectional"))
    )
    (net (code "183") (name "P6_00") (class "Default")
      (node (ref "J8") (pin "P$19") (pinfunction "P$19_P$19") (pintype "bidirectional"))
      (node (ref "U3") (pin "122") (pinfunction "P6_0_122") (pintype "bidirectional"))
    )
    (net (code "184") (name "P7_06") (class "Default")
      (node (ref "J4") (pin "P$10") (pinfunction "P$10_P$10") (pintype "bidirectional"))
      (node (ref "U3") (pin "14") (pinfunction "P7_6_14") (pintype "bidirectional"))
    )
    (net (code "185") (name "P7_07") (class "Default")
      (node (ref "J4") (pin "P$11") (pinfunction "P$11_P$11") (pintype "bidirectional"))
      (node (ref "U3") (pin "15") (pinfunction "P7_7_15") (pintype "bidirectional"))
    )
    (net (code "186") (name "P8_00") (class "Default")
      (node (ref "J8") (pin "P$5") (pinfunction "P$5_P$5") (pintype "bidirectional"))
      (node (ref "U3") (pin "133") (pinfunction "P8_0_133") (pintype "bidirectional"))
    )
    (net (code "187") (name "P8_01") (class "Default")
      (node (ref "J8") (pin "P$3") (pinfunction "P$3_P$3") (pintype "bidirectional"))
      (node (ref "U3") (pin "134") (pinfunction "P8_1_134") (pintype "bidirectional"))
    )
    (net (code "188") (name "P8_02") (class "Default")
      (node (ref "J8") (pin "P$4") (pinfunction "P$4_P$4") (pintype "bidirectional"))
      (node (ref "U3") (pin "135") (pinfunction "P8_2_135") (pintype "bidirectional"))
    )
    (net (code "189") (name "P8_03") (class "Default")
      (node (ref "J8") (pin "P$1") (pinfunction "P$1_P$1") (pintype "bidirectional"))
      (node (ref "U3") (pin "136") (pinfunction "P8_3_136") (pintype "bidirectional"))
    )
    (net (code "190") (name "P8_04") (class "Default")
      (node (ref "J8") (pin "P$2") (pinfunction "P$2_P$2") (pintype "bidirectional"))
      (node (ref "U3") (pin "137") (pinfunction "P8_4_137") (pintype "bidirectional"))
    )
    (net (code "191") (name "P8_05") (class "Default")
      (node (ref "J4") (pin "P$3") (pinfunction "P$3_P$3") (pintype "bidirectional"))
      (node (ref "U3") (pin "173") (pinfunction "P8_5_173") (pintype "bidirectional"))
    )
    (net (code "192") (name "PB_00") (class "Default")
      (node (ref "J4") (pin "P$12") (pinfunction "P$12_P$12") (pintype "bidirectional"))
      (node (ref "U3") (pin "16") (pinfunction "PB_0_16") (pintype "bidirectional"))
    )
    (net (code "193") (name "R51") (class "Default")
      (node (ref "R7") (pin "P$1") (pinfunction "1_P$1") (pintype "passive"))
      (node (ref "RJ1") (pin "12") (pinfunction "YHI_12") (pintype "bidirectional"))
    )
    (net (code "194") (name "R52") (class "Default")
      (node (ref "R8") (pin "P$1") (pinfunction "1_P$1") (pintype "passive"))
      (node (ref "RJ1") (pin "9") (pinfunction "GHI_9") (pintype "bidirectional"))
    )
    (net (code "195") (name "RELAY_1") (class "Default")
      (node (ref "R29") (pin "P$1") (pinfunction "1_P$1") (pintype "passive"))
      (node (ref "U3") (pin "56") (pinfunction "P3_14_56") (pintype "bidirectional"))
    )
    (net (code "196") (name "RELAY_2") (class "Default")
      (node (ref "R30") (pin "P$1") (pinfunction "1_P$1") (pintype "passive"))
      (node (ref "U3") (pin "55") (pinfunction "P3_13_55") (pintype "bidirectional"))
    )
    (net (code "197") (name "RELAY_3") (class "Default")
      (node (ref "R49") (pin "P$1") (pinfunction "1_P$1") (pintype "passive"))
      (node (ref "U3") (pin "52") (pinfunction "P2_4_52") (pintype "bidirectional"))
    )
    (net (code "198") (name "RELAY_4") (class "Default")
      (node (ref "R50") (pin "P$1") (pinfunction "1_P$1") (pintype "passive"))
      (node (ref "U3") (pin "49") (pinfunction "P2_7_49") (pintype "bidirectional"))
    )
    (net (code "199") (name "RESET") (class "Default")
      (node (ref "C16") (pin "P$1") (pinfunction "1_P$1") (pintype "passive"))
      (node (ref "J3") (pin "9") (pinfunction "9_9") (pintype "passive"))
      (node (ref "R13") (pin "P$1") (pinfunction "1_P$1") (pintype "passive"))
      (node (ref "U3") (pin "67") (pinfunction "RES#_67") (pintype "bidirectional"))
    )
    (net (code "200") (name "REXT") (class "Default")
      (node (ref "C3") (pin "P$1") (pinfunction "1_P$1") (pintype "passive"))
      (node (ref "R1") (pin "P$2") (pinfunction "2_P$2") (pintype "passive"))
      (node (ref "U1") (pin "9") (pinfunction "REXT_9") (pintype "input"))
    )
    (net (code "201") (name "RO_NEG_1") (class "Default")
      (node (ref "J15") (pin "P$2") (pinfunction "P$2_P$2") (pintype "bidirectional"))
      (node (ref "U$1") (pin "P$3") (pinfunction "VO-_P$3") (pintype "bidirectional"))
    )
    (net (code "202") (name "RO_NEG_2") (class "Default")
      (node (ref "J16") (pin "P$2") (pinfunction "P$2_P$2") (pintype "bidirectional"))
      (node (ref "U$2") (pin "P$3") (pinfunction "VO-_P$3") (pintype "bidirectional"))
    )
    (net (code "203") (name "RO_NEG_3") (class "Default")
      (node (ref "J23") (pin "P$2") (pinfunction "P$2_P$2") (pintype "bidirectional"))
      (node (ref "U$7") (pin "P$3") (pinfunction "VO-_P$3") (pintype "bidirectional"))
    )
    (net (code "204") (name "RO_NEG_4") (class "Default")
      (node (ref "J24") (pin "P$2") (pinfunction "P$2_P$2") (pintype "bidirectional"))
      (node (ref "U$8") (pin "P$3") (pinfunction "VO-_P$3") (pintype "bidirectional"))
    )
    (net (code "205") (name "RO_POS_1") (class "Default")
      (node (ref "J15") (pin "P$1") (pinfunction "P$1_P$1") (pintype "bidirectional"))
      (node (ref "U$1") (pin "P$4") (pinfunction "VO+_P$4") (pintype "bidirectional"))
    )
    (net (code "206") (name "RO_POS_2") (class "Default")
      (node (ref "J16") (pin "P$1") (pinfunction "P$1_P$1") (pintype "bidirectional"))
      (node (ref "U$2") (pin "P$4") (pinfunction "VO+_P$4") (pintype "bidirectional"))
    )
    (net (code "207") (name "RO_POS_3") (class "Default")
      (node (ref "J23") (pin "P$1") (pinfunction "P$1_P$1") (pintype "bidirectional"))
      (node (ref "U$7") (pin "P$4") (pinfunction "VO+_P$4") (pintype "bidirectional"))
    )
    (net (code "208") (name "RO_POS_4") (class "Default")
      (node (ref "J24") (pin "P$1") (pinfunction "P$1_P$1") (pintype "bidirectional"))
      (node (ref "U$8") (pin "P$4") (pinfunction "VO+_P$4") (pintype "bidirectional"))
    )
    (net (code "209") (name "RXD0") (class "Default")
      (node (ref "R10") (pin "P$2") (pinfunction "2_P$2") (pintype "passive"))
      (node (ref "U1") (pin "13") (pinfunction "RXD0_13") (pintype "bidirectional"))
    )
    (net (code "210") (name "RXD1") (class "Default")
      (node (ref "R9") (pin "P$2") (pinfunction "2_P$2") (pintype "passive"))
      (node (ref "U1") (pin "12") (pinfunction "RXD1_12") (pintype "bidirectional"))
    )
    (net (code "211") (name "RXER") (class "Default")
      (node (ref "R11") (pin "P$2") (pinfunction "2_P$2") (pintype "passive"))
      (node (ref "U1") (pin "17") (pinfunction "RXER_17") (pintype "bidirectional"))
    )
    (net (code "212") (name "RXM") (class "Default")
      (node (ref "RJ1") (pin "6") (pinfunction "RD-_6") (pintype "bidirectional"))
      (node (ref "U1") (pin "3") (pinfunction "RXM_3") (pintype "bidirectional"))
    )
    (net (code "213") (name "RXP") (class "Default")
      (node (ref "RJ1") (pin "3") (pinfunction "RD+_3") (pintype "bidirectional"))
      (node (ref "U1") (pin "4") (pinfunction "RXP_4") (pintype "bidirectional"))
    )
    (net (code "214") (name "SD1_CD") (class "Default")
      (node (ref "J1") (pin "10") (pinfunction "CD_SWITCH2_10") (pintype "bidirectional"))
      (node (ref "U3") (pin "146") (pinfunction "P5_6/AN019_146") (pintype "bidirectional"))
    )
    (net (code "215") (name "SD1_CLK") (class "Default")
      (node (ref "J1") (pin "5") (pinfunction "CLOCK_5") (pintype "bidirectional"))
      (node (ref "U3") (pin "140") (pinfunction "P5_0/AN016_140") (pintype "bidirectional"))
    )
    (net (code "216") (name "SD1_CMD") (class "Default")
      (node (ref "J1") (pin "3") (pinfunction "COMMAND/RESPONSE_3") (pintype "bidirectional"))
      (node (ref "U3") (pin "141") (pinfunction "P5_1/AN116_141") (pintype "bidirectional"))
    )
    (net (code "217") (name "SD1_DAT0") (class "Default")
      (node (ref "J1") (pin "7") (pinfunction "DATA_LINE[BIT_0]_7") (pintype "bidirectional"))
      (node (ref "U3") (pin "142") (pinfunction "P5_2/AN017_142") (pintype "bidirectional"))
    )
    (net (code "218") (name "SD1_DAT1") (class "Default")
      (node (ref "J1") (pin "8") (pinfunction "DATA_LINE[BIT_1]_8") (pintype "bidirectional"))
      (node (ref "U3") (pin "143") (pinfunction "P5_3/AN117_143") (pintype "bidirectional"))
    )
    (net (code "219") (name "SD1_DAT2") (class "Default")
      (node (ref "J1") (pin "1") (pinfunction "DATA_LINE[BIT_2]_1") (pintype "bidirectional"))
      (node (ref "U3") (pin "144") (pinfunction "P5_4/AN018_144") (pintype "bidirectional"))
    )
    (net (code "220") (name "SD1_DAT3") (class "Default")
      (node (ref "J1") (pin "2") (pinfunction "CARD_DETECT/DATA_LINE[BIT_3]_2") (pintype "bidirectional"))
      (node (ref "U3") (pin "145") (pinfunction "P5_5/AN118_145") (pintype "bidirectional"))
    )
    (net (code "221") (name "SD1_WP") (class "Default")
      (node (ref "J1") (pin "9") (pinfunction "CD_SWITCH1_9") (pintype "bidirectional"))
      (node (ref "U3") (pin "147") (pinfunction "P5_7/AN119_147") (pintype "bidirectional"))
    )
    (net (code "222") (name "TCK") (class "Default")
      (node (ref "J3") (pin "7") (pinfunction "7_7") (pintype "passive"))
      (node (ref "U3") (pin "88") (pinfunction "P3_0_88") (pintype "bidirectional"))
    )
    (net (code "223") (name "TDI") (class "Default")
      (node (ref "J3") (pin "1") (pinfunction "1_1") (pintype "passive"))
      (node (ref "U3") (pin "91") (pinfunction "P1_10_91") (pintype "bidirectional"))
    )
    (net (code "224") (name "TDO") (class "Default")
      (node (ref "J3") (pin "3") (pinfunction "3_3") (pintype "passive"))
      (node (ref "U3") (pin "90") (pinfunction "P1_9_90") (pintype "bidirectional"))
    )
    (net (code "225") (name "TMS") (class "Default")
      (node (ref "J3") (pin "5") (pinfunction "5_5") (pintype "passive"))
      (node (ref "U3") (pin "89") (pinfunction "P1_8_89") (pintype "bidirectional"))
    )
    (net (code "226") (name "TXM") (class "Default")
      (node (ref "RJ1") (pin "2") (pinfunction "TD-_2") (pintype "bidirectional"))
      (node (ref "U1") (pin "5") (pinfunction "TXM_5") (pintype "bidirectional"))
    )
    (net (code "227") (name "TXP") (class "Default")
      (node (ref "RJ1") (pin "1") (pinfunction "TD+_1") (pintype "bidirectional"))
      (node (ref "U1") (pin "6") (pinfunction "TXP_6") (pintype "bidirectional"))
    )
    (net (code "228") (name "USBHS_FAULT") (class "Default")
      (node (ref "R19") (pin "P$1") (pinfunction "1_P$1") (pintype "passive"))
      (node (ref "U2") (pin "3") (pinfunction "FLG_3") (pintype "input"))
      (node (ref "U3") (pin "78") (pinfunction "P3_8_78") (pintype "bidirectional"))
    )
    (net (code "229") (name "USBHS_N") (class "Default")
      (node (ref "J6") (pin "D-") (pinfunction "D-_D-") (pintype "bidirectional"))
      (node (ref "U3") (pin "31") (pinfunction "USBHS_DM_31") (pintype "bidirectional"))
    )
    (net (code "230") (name "USBHS_P") (class "Default")
      (node (ref "J6") (pin "D+") (pinfunction "D+_D+") (pintype "bidirectional"))
      (node (ref "U3") (pin "32") (pinfunction "USBHS_DP_32") (pintype "bidirectional"))
    )
    (net (code "231") (name "USBHS_VBUS") (class "Default")
      (node (ref "C29") (pin "P$1") (pinfunction "1_P$1") (pintype "passive"))
      (node (ref "C31") (pin "1") (pinfunction "1_1") (pintype "passive"))
      (node (ref "J6") (pin "VBUS") (pinfunction "VBUS_VBUS") (pintype "power_in"))
      (node (ref "U2") (pin "5") (pinfunction "OUT_5") (pintype "input"))
      (node (ref "U3") (pin "17") (pinfunction "PB_1_17") (pintype "bidirectional"))
    )
    (net (code "232") (name "USBHS_VBUSEN") (class "Default")
      (node (ref "R20") (pin "P$1") (pinfunction "1_P$1") (pintype "passive"))
      (node (ref "U2") (pin "1") (pinfunction "EN_1") (pintype "input"))
    )
    (net (code "233") (name "USB_N") (class "Default")
      (node (ref "R17") (pin "P$1") (pinfunction "1_P$1") (pintype "passive"))
      (node (ref "U3") (pin "46") (pinfunction "USB_DM_46") (pintype "bidirectional"))
    )
    (net (code "234") (name "USB_P") (class "Default")
      (node (ref "R18") (pin "P$1") (pinfunction "1_P$1") (pintype "passive"))
      (node (ref "U3") (pin "47") (pinfunction "USB_DP_47") (pintype "bidirectional"))
    )
    (net (code "235") (name "USB_VBUS_B") (class "Default")
      (node (ref "R16") (pin "P$1") (pinfunction "1_P$1") (pintype "passive"))
      (node (ref "U3") (pin "44") (pinfunction "P4_7_44") (pintype "bidirectional"))
    )
    (net (code "236") (name "VCL_F(FLASH)") (class "Default")
      (node (ref "C34") (pin "P$2") (pinfunction "2_P$2") (pintype "passive"))
      (node (ref "U3") (pin "112") (pinfunction "VCL_F(FLASH)_112") (pintype "bidirectional"))
    )
    (net (code "237") (name "VDD") (class "Default")
      (node (ref "C14") (pin "P$1") (pinfunction "1_P$1") (pintype "passive"))
      (node (ref "C15") (pin "P$1") (pinfunction "1_P$1") (pintype "passive"))
      (node (ref "C19") (pin "P$2") (pinfunction "2_P$2") (pintype "passive"))
      (node (ref "C20") (pin "P$2") (pinfunction "2_P$2") (pintype "passive"))
      (node (ref "C21") (pin "P$2") (pinfunction "2_P$2") (pintype "passive"))
      (node (ref "C22") (pin "P$2") (pinfunction "2_P$2") (pintype "passive"))
      (node (ref "C25") (pin "P$2") (pinfunction "2_P$2") (pintype "passive"))
      (node (ref "C27") (pin "P$2") (pinfunction "2_P$2") (pintype "passive"))
      (node (ref "C30") (pin "P$2") (pinfunction "2_P$2") (pintype "passive"))
      (node (ref "C35") (pin "P$2") (pinfunction "2_P$2") (pintype "passive"))
      (node (ref "C36") (pin "P$1") (pinfunction "1_P$1") (pintype "passive"))
      (node (ref "C38") (pin "P$2") (pinfunction "2_P$2") (pintype "passive"))
      (node (ref "C39") (pin "P$1") (pinfunction "1_P$1") (pintype "passive"))
      (node (ref "C4") (pin "P$1") (pinfunction "1_P$1") (pintype "passive"))
      (node (ref "C40") (pin "P$1") (pinfunction "1_P$1") (pintype "passive"))
      (node (ref "C41") (pin "P$1") (pinfunction "1_P$1") (pintype "passive"))
      (node (ref "C43") (pin "P$2") (pinfunction "2_P$2") (pintype "passive"))
      (node (ref "C5") (pin "P$1") (pinfunction "1_P$1") (pintype "passive"))
      (node (ref "C7") (pin "P$1") (pinfunction "1_P$1") (pintype "passive"))
      (node (ref "FB1") (pin "1") (pinfunction "P$1_1") (pintype "bidirectional"))
      (node (ref "J1") (pin "4") (pinfunction "SUPPLY_VOLTAGE_4") (pintype "power_in"))
      (node (ref "J3") (pin "2") (pinfunction "2_2") (pintype "passive"))
      (node (ref "J3") (pin "4") (pinfunction "4_4") (pintype "passive"))
      (node (ref "L1") (pin "2") (pinfunction "P$2_2") (pintype "bidirectional"))
      (node (ref "R102") (pin "P$2") (pinfunction "2_P$2") (pintype "passive"))
      (node (ref "R103") (pin "P$2") (pinfunction "2_P$2") (pintype "passive"))
      (node (ref "R104") (pin "P$2") (pinfunction "2_P$2") (pintype "passive"))
      (node (ref "R105") (pin "P$2") (pinfunction "2_P$2") (pintype "passive"))
      (node (ref "R106") (pin "P$2") (pinfunction "2_P$2") (pintype "passive"))
      (node (ref "R107") (pin "P$2") (pinfunction "2_P$2") (pintype "passive"))
      (node (ref "R108") (pin "P$2") (pinfunction "2_P$2") (pintype "passive"))
      (node (ref "R13") (pin "P$2") (pinfunction "2_P$2") (pintype "passive"))
      (node (ref "R14") (pin "P$1") (pinfunction "1_P$1") (pintype "passive"))
      (node (ref "R15") (pin "P$1") (pinfunction "1_P$1") (pintype "passive"))
      (node (ref "R2") (pin "P$2") (pinfunction "2_P$2") (pintype "passive"))
      (node (ref "R25") (pin "P$2") (pinfunction "2_P$2") (pintype "passive"))
      (node (ref "R26") (pin "P$2") (pinfunction "2_P$2") (pintype "passive"))
      (node (ref "R27") (pin "P$2") (pinfunction "2_P$2") (pintype "passive"))
      (node (ref "R3") (pin "P$2") (pinfunction "2_P$2") (pintype "passive"))
      (node (ref "R4") (pin "P$2") (pinfunction "2_P$2") (pintype "passive"))
      (node (ref "R5") (pin "P$2") (pinfunction "2_P$2") (pintype "passive"))
      (node (ref "R6") (pin "P$2") (pinfunction "2_P$2") (pintype "passive"))
      (node (ref "R7") (pin "P$2") (pinfunction "2_P$2") (pintype "passive"))
      (node (ref "R8") (pin "P$2") (pinfunction "2_P$2") (pintype "passive"))
      (node (ref "U1") (pin "14") (pinfunction "VDDIO_14") (pintype "power_in"))
      (node (ref "U18") (pin "3") (pinfunction "C(3)_3") (pintype "input"))
      (node (ref "U19") (pin "3") (pinfunction "C(3)_3") (pintype "input"))
      (node (ref "U20") (pin "3") (pinfunction "C(3)_3") (pintype "input"))
      (node (ref "U21") (pin "3") (pinfunction "C(3)_3") (pintype "input"))
      (node (ref "U28") (pin "3") (pinfunction "C(3)_3") (pintype "input"))
      (node (ref "U29") (pin "3") (pinfunction "C(3)_3") (pintype "input"))
      (node (ref "U3") (pin "110") (pinfunction "VCC(IO)5_110") (pintype "bidirectional"))
      (node (ref "U3") (pin "123") (pinfunction "VCC(IO)6_123") (pintype "bidirectional"))
      (node (ref "U3") (pin "138") (pinfunction "VCC(IO)7_138") (pintype "bidirectional"))
      (node (ref "U3") (pin "149") (pinfunction "VCC(IO)8_149") (pintype "bidirectional"))
      (node (ref "U3") (pin "154") (pinfunction "VREFH_154") (pintype "bidirectional"))
      (node (ref "U3") (pin "155") (pinfunction "AVCC0_155") (pintype "bidirectional"))
      (node (ref "U3") (pin "158") (pinfunction "VREFH0_158") (pintype "bidirectional"))
      (node (ref "U3") (pin "171") (pinfunction "VCC(IO)9_171") (pintype "bidirectional"))
      (node (ref "U3") (pin "25") (pinfunction "VCC1_25") (pintype "bidirectional"))
      (node (ref "U3") (pin "26") (pinfunction "AVCC_SUBHS_26") (pintype "bidirectional"))
      (node (ref "U3") (pin "34") (pinfunction "VCC_USBHS_34") (pintype "bidirectional"))
      (node (ref "U3") (pin "48") (pinfunction "VCC_USB_48") (pintype "bidirectional"))
      (node (ref "U3") (pin "61") (pinfunction "VCC(IO)2_61") (pintype "bidirectional"))
      (node (ref "U3") (pin "84") (pinfunction "VCC(IO)3_84") (pintype "bidirectional"))
      (node (ref "U3") (pin "97") (pinfunction "VCC(IO)4_97") (pintype "bidirectional"))
      (node (ref "U30") (pin "3") (pinfunction "C(3)_3") (pintype "input"))
      (node (ref "U5") (pin "3") (pinfunction "C(3)_3") (pintype "input"))
      (node (ref "U8") (pin "3") (pinfunction "C(3)_3") (pintype "input"))
      (node (ref "U9") (pin "3") (pinfunction "C(3)_3") (pintype "input"))
    )
    (net (code "238") (name "VDD5") (class "Default")
      (node (ref "C23") (pin "P$1") (pinfunction "1_P$1") (pintype "passive"))
      (node (ref "C26") (pin "P$1") (pinfunction "1_P$1") (pintype "passive"))
      (node (ref "J2") (pin "P$3") (pinfunction "P$3_P$3") (pintype "bidirectional"))
      (node (ref "R19") (pin "P$2") (pinfunction "2_P$2") (pintype "passive"))
      (node (ref "R20") (pin "P$2") (pinfunction "2_P$2") (pintype "passive"))
      (node (ref "R31") (pin "P$2") (pinfunction "2_P$2") (pintype "passive"))
      (node (ref "R32") (pin "P$2") (pinfunction "2_P$2") (pintype "passive"))
      (node (ref "R51") (pin "P$2") (pinfunction "2_P$2") (pintype "passive"))
      (node (ref "R52") (pin "P$2") (pinfunction "2_P$2") (pintype "passive"))
      (node (ref "U$1") (pin "P$2") (pinfunction "VC+_P$2") (pintype "bidirectional"))
      (node (ref "U$2") (pin "P$2") (pinfunction "VC+_P$2") (pintype "bidirectional"))
      (node (ref "U$7") (pin "P$2") (pinfunction "VC+_P$2") (pintype "bidirectional"))
      (node (ref "U$8") (pin "P$2") (pinfunction "VC+_P$2") (pintype "bidirectional"))
      (node (ref "U2") (pin "4") (pinfunction "VIN_4") (pintype "input"))
    )
    (net (code "239") (name "VDD12") (class "Default")
      (node (ref "J10") (pin "3") (pinfunction "3_3") (pintype "passive"))
      (node (ref "J11") (pin "3") (pinfunction "3_3") (pintype "passive"))
      (node (ref "J12") (pin "3") (pinfunction "3_3") (pintype "passive"))
      (node (ref "J13") (pin "1") (pinfunction "1-HLFB+_1") (pintype "passive"))
      (node (ref "J13") (pin "2") (pinfunction "2-INPUT_B+_2") (pintype "passive"))
      (node (ref "J13") (pin "3") (pinfunction "3-INPUT_A+_3") (pintype "passive"))
      (node (ref "J13") (pin "4") (pinfunction "4-ENABLE+_4") (pintype "passive"))
      (node (ref "J14") (pin "1") (pinfunction "1-HLFB+_1") (pintype "passive"))
      (node (ref "J14") (pin "2") (pinfunction "2-INPUT_B+_2") (pintype "passive"))
      (node (ref "J14") (pin "3") (pinfunction "3-INPUT_A+_3") (pintype "passive"))
      (node (ref "J14") (pin "4") (pinfunction "4-ENABLE+_4") (pintype "passive"))
      (node (ref "J17") (pin "1") (pinfunction "1-HLFB+_1") (pintype "passive"))
      (node (ref "J17") (pin "2") (pinfunction "2-INPUT_B+_2") (pintype "passive"))
      (node (ref "J17") (pin "3") (pinfunction "3-INPUT_A+_3") (pintype "passive"))
      (node (ref "J17") (pin "4") (pinfunction "4-ENABLE+_4") (pintype "passive"))
      (node (ref "J18") (pin "1") (pinfunction "1-HLFB+_1") (pintype "passive"))
      (node (ref "J18") (pin "2") (pinfunction "2-INPUT_B+_2") (pintype "passive"))
      (node (ref "J18") (pin "3") (pinfunction "3-INPUT_A+_3") (pintype "passive"))
      (node (ref "J18") (pin "4") (pinfunction "4-ENABLE+_4") (pintype "passive"))
      (node (ref "J19") (pin "3") (pinfunction "3_3") (pintype "passive"))
      (node (ref "J20") (pin "3") (pinfunction "3_3") (pintype "passive"))
      (node (ref "J21") (pin "1") (pinfunction "1-HLFB+_1") (pintype "passive"))
      (node (ref "J21") (pin "2") (pinfunction "2-INPUT_B+_2") (pintype "passive"))
      (node (ref "J21") (pin "3") (pinfunction "3-INPUT_A+_3") (pintype "passive"))
      (node (ref "J21") (pin "4") (pinfunction "4-ENABLE+_4") (pintype "passive"))
      (node (ref "J22") (pin "1") (pinfunction "1-HLFB+_1") (pintype "passive"))
      (node (ref "J22") (pin "2") (pinfunction "2-INPUT_B+_2") (pintype "passive"))
      (node (ref "J22") (pin "3") (pinfunction "3-INPUT_A+_3") (pintype "passive"))
      (node (ref "J22") (pin "4") (pinfunction "4-ENABLE+_4") (pintype "passive"))
      (node (ref "J25") (pin "1") (pinfunction "1-HLFB+_1") (pintype "passive"))
      (node (ref "J25") (pin "2") (pinfunction "2-INPUT_B+_2") (pintype "passive"))
      (node (ref "J25") (pin "3") (pinfunction "3-INPUT_A+_3") (pintype "passive"))
      (node (ref "J25") (pin "4") (pinfunction "4-ENABLE+_4") (pintype "passive"))
      (node (ref "J26") (pin "1") (pinfunction "1-HLFB+_1") (pintype "passive"))
      (node (ref "J26") (pin "2") (pinfunction "2-INPUT_B+_2") (pintype "passive"))
      (node (ref "J26") (pin "3") (pinfunction "3-INPUT_A+_3") (pintype "passive"))
      (node (ref "J26") (pin "4") (pinfunction "4-ENABLE+_4") (pintype "passive"))
      (node (ref "J27") (pin "3") (pinfunction "3_3") (pintype "passive"))
      (node (ref "J28") (pin "3") (pinfunction "3_3") (pintype "passive"))
      (node (ref "J29") (pin "1") (pinfunction "1-HLFB+_1") (pintype "passive"))
      (node (ref "J29") (pin "2") (pinfunction "2-INPUT_B+_2") (pintype "passive"))
      (node (ref "J29") (pin "3") (pinfunction "3-INPUT_A+_3") (pintype "passive"))
      (node (ref "J29") (pin "4") (pinfunction "4-ENABLE+_4") (pintype "passive"))
      (node (ref "J30") (pin "1") (pinfunction "1-HLFB+_1") (pintype "passive"))
      (node (ref "J30") (pin "2") (pinfunction "2-INPUT_B+_2") (pintype "passive"))
      (node (ref "J30") (pin "3") (pinfunction "3-INPUT_A+_3") (pintype "passive"))
      (node (ref "J30") (pin "4") (pinfunction "4-ENABLE+_4") (pintype "passive"))
      (node (ref "J31") (pin "3") (pinfunction "3_3") (pintype "passive"))
      (node (ref "J32") (pin "3") (pinfunction "3_3") (pintype "passive"))
      (node (ref "J33") (pin "1") (pinfunction "1-HLFB+_1") (pintype "passive"))
      (node (ref "J33") (pin "2") (pinfunction "2-INPUT_B+_2") (pintype "passive"))
      (node (ref "J33") (pin "3") (pinfunction "3-INPUT_A+_3") (pintype "passive"))
      (node (ref "J33") (pin "4") (pinfunction "4-ENABLE+_4") (pintype "passive"))
      (node (ref "J34") (pin "1") (pinfunction "1-HLFB+_1") (pintype "passive"))
      (node (ref "J34") (pin "2") (pinfunction "2-INPUT_B+_2") (pintype "passive"))
      (node (ref "J34") (pin "3") (pinfunction "3-INPUT_A+_3") (pintype "passive"))
      (node (ref "J34") (pin "4") (pinfunction "4-ENABLE+_4") (pintype "passive"))
      (node (ref "J5") (pin "3") (pinfunction "3_3") (pintype "passive"))
      (node (ref "J9") (pin "P$1") (pinfunction "P$1_P$1") (pintype "bidirectional"))
      (node (ref "J9") (pin "P$2") (pinfunction "P$2_P$2") (pintype "bidirectional"))
      (node (ref "R109") (pin "2") (pinfunction "2_2") (pintype "passive"))
      (node (ref "R113") (pin "2") (pinfunction "2_2") (pintype "passive"))
      (node (ref "R114") (pin "2") (pinfunction "2_2") (pintype "passive"))
      (node (ref "R115") (pin "2") (pinfunction "2_2") (pintype "passive"))
      (node (ref "R119") (pin "2") (pinfunction "2_2") (pintype "passive"))
      (node (ref "R120") (pin "2") (pinfunction "2_2") (pintype "passive"))
      (node (ref "R133") (pin "2") (pinfunction "2_2") (pintype "passive"))
      (node (ref "R137") (pin "2") (pinfunction "2_2") (pintype "passive"))
      (node (ref "R138") (pin "2") (pinfunction "2_2") (pintype "passive"))
      (node (ref "R139") (pin "2") (pinfunction "2_2") (pintype "passive"))
      (node (ref "R143") (pin "2") (pinfunction "2_2") (pintype "passive"))
      (node (ref "R144") (pin "2") (pinfunction "2_2") (pintype "passive"))
      (node (ref "R157") (pin "2") (pinfunction "2_2") (pintype "passive"))
      (node (ref "R161") (pin "2") (pinfunction "2_2") (pintype "passive"))
      (node (ref "R162") (pin "2") (pinfunction "2_2") (pintype "passive"))
      (node (ref "R163") (pin "2") (pinfunction "2_2") (pintype "passive"))
      (node (ref "R167") (pin "2") (pinfunction "2_2") (pintype "passive"))
      (node (ref "R168") (pin "2") (pinfunction "2_2") (pintype "passive"))
      (node (ref "R37") (pin "2") (pinfunction "2_2") (pintype "passive"))
      (node (ref "R41") (pin "2") (pinfunction "2_2") (pintype "passive"))
      (node (ref "R42") (pin "2") (pinfunction "2_2") (pintype "passive"))
      (node (ref "R43") (pin "2") (pinfunction "2_2") (pintype "passive"))
      (node (ref "R47") (pin "2") (pinfunction "2_2") (pintype "passive"))
      (node (ref "R48") (pin "2") (pinfunction "2_2") (pintype "passive"))
      (node (ref "R61") (pin "2") (pinfunction "2_2") (pintype "passive"))
      (node (ref "R65") (pin "2") (pinfunction "2_2") (pintype "passive"))
      (node (ref "R66") (pin "2") (pinfunction "2_2") (pintype "passive"))
      (node (ref "R67") (pin "2") (pinfunction "2_2") (pintype "passive"))
      (node (ref "R71") (pin "2") (pinfunction "2_2") (pintype "passive"))
      (node (ref "R72") (pin "2") (pinfunction "2_2") (pintype "passive"))
      (node (ref "R85") (pin "2") (pinfunction "2_2") (pintype "passive"))
      (node (ref "R89") (pin "2") (pinfunction "2_2") (pintype "passive"))
      (node (ref "R90") (pin "2") (pinfunction "2_2") (pintype "passive"))
      (node (ref "R91") (pin "2") (pinfunction "2_2") (pintype "passive"))
      (node (ref "R95") (pin "2") (pinfunction "2_2") (pintype "passive"))
      (node (ref "R96") (pin "2") (pinfunction "2_2") (pintype "passive"))
    )
    (net (code "240") (name "VDDIN") (class "Default")
      (node (ref "J2") (pin "P$2") (pinfunction "P$2_P$2") (pintype "bidirectional"))
      (node (ref "L1") (pin "1") (pinfunction "P$1_1") (pintype "bidirectional"))
    )
    (net (code "241") (name "VDD_1.2") (class "Default")
      (node (ref "C10") (pin "P$1") (pinfunction "1_P$1") (pintype "passive"))
      (node (ref "C11") (pin "P$1") (pinfunction "1_P$1") (pintype "passive"))
      (node (ref "U1") (pin "1") (pinfunction "VDD_1.2_1") (pintype "power_in"))
    )
    (net (code "242") (name "WF_A_DIR") (class "Default")
      (node (ref "R159") (pin "1") (pinfunction "1_1") (pintype "passive"))
      (node (ref "U3") (pin "99") (pinfunction "P6_8_99") (pintype "bidirectional"))
    )
    (net (code "243") (name "WF_A_ENABLE") (class "Default")
      (node (ref "R160") (pin "1") (pinfunction "1_1") (pintype "passive"))
      (node (ref "U3") (pin "96") (pinfunction "P1_15_96") (pintype "bidirectional"))
    )
    (net (code "244") (name "WF_A_HLFB_OUT") (class "Default")
      (node (ref "J33") (pin "5") (pinfunction "5-HLFB-_5") (pintype "passive"))
    )
    (net (code "245") (name "WF_A_MI_DIR") (class "Default")
      (node (ref "J33") (pin "7") (pinfunction "7-INPUT_A-_7") (pintype "passive"))
      (node (ref "R161") (pin "1") (pinfunction "1_1") (pintype "passive"))
      (node (ref "U71") (pin "3") (pinfunction "C(3)_3") (pintype "input"))
    )
    (net (code "246") (name "WF_A_MI_ENABLE") (class "Default")
      (node (ref "J33") (pin "8") (pinfunction "8-ENABLE-_8") (pintype "passive"))
      (node (ref "R162") (pin "1") (pinfunction "1_1") (pintype "passive"))
      (node (ref "U72") (pin "3") (pinfunction "C(3)_3") (pintype "input"))
    )
    (net (code "247") (name "WF_A_MI_STEP") (class "Default")
      (node (ref "J33") (pin "6") (pinfunction "6-INPUT_B-_6") (pintype "passive"))
      (node (ref "R157") (pin "1") (pinfunction "1_1") (pintype "passive"))
      (node (ref "U70") (pin "3") (pinfunction "C(3)_3") (pintype "input"))
    )
    (net (code "248") (name "WF_A_STEP") (class "Default")
      (node (ref "R158") (pin "1") (pinfunction "1_1") (pintype "passive"))
      (node (ref "U3") (pin "100") (pinfunction "P6_9_100") (pintype "bidirectional"))
    )
    (net (code "249") (name "WF_B_DIR") (class "Default")
      (node (ref "R165") (pin "1") (pinfunction "1_1") (pintype "passive"))
      (node (ref "U3") (pin "94") (pinfunction "P1_13_94") (pintype "bidirectional"))
    )
    (net (code "250") (name "WF_B_ENABLE") (class "Default")
      (node (ref "R166") (pin "1") (pinfunction "1_1") (pintype "passive"))
      (node (ref "U3") (pin "93") (pinfunction "P1_12_93") (pintype "bidirectional"))
    )
    (net (code "251") (name "WF_B_HLFB_OUT") (class "Default")
      (node (ref "J34") (pin "5") (pinfunction "5-HLFB-_5") (pintype "passive"))
    )
    (net (code "252") (name "WF_B_MI_ENABLE") (class "Default")
      (node (ref "J34") (pin "8") (pinfunction "8-ENABLE-_8") (pintype "passive"))
      (node (ref "R168") (pin "1") (pinfunction "1_1") (pintype "passive"))
      (node (ref "U75") (pin "3") (pinfunction "C(3)_3") (pintype "input"))
    )
    (net (code "253") (name "WF_B_MI_STEP") (class "Default")
      (node (ref "J34") (pin "6") (pinfunction "6-INPUT_B-_6") (pintype "passive"))
      (node (ref "R163") (pin "1") (pinfunction "1_1") (pintype "passive"))
      (node (ref "U73") (pin "3") (pinfunction "C(3)_3") (pintype "input"))
    )
    (net (code "254") (name "WF_B_STEP") (class "Default")
      (node (ref "R164") (pin "1") (pinfunction "1_1") (pintype "passive"))
      (node (ref "U3") (pin "95") (pinfunction "P1_14_95") (pintype "bidirectional"))
    )
    (net (code "255") (name "XCIN") (class "Default")
      (node (ref "C32") (pin "P$1") (pinfunction "1_P$1") (pintype "passive"))
      (node (ref "U3") (pin "20") (pinfunction "XCIN_20") (pintype "bidirectional"))
      (node (ref "X3") (pin "P$1") (pinfunction "P$1_P$1") (pintype "bidirectional"))
    )
    (net (code "256") (name "XCOUT") (class "Default")
      (node (ref "C37") (pin "P$1") (pinfunction "1_P$1") (pintype "passive"))
      (node (ref "U3") (pin "21") (pinfunction "XCOUT_21") (pintype "bidirectional"))
      (node (ref "X3") (pin "P$2") (pinfunction "P$2_P$2") (pintype "bidirectional"))
    )
    (net (code "257") (name "XII") (class "Default")
      (node (ref "C1") (pin "P$1") (pinfunction "1_P$1") (pintype "passive"))
      (node (ref "U1") (pin "8") (pinfunction "XI_8") (pintype "input"))
      (node (ref "X1") (pin "1") (pinfunction "1_1") (pintype "bidirectional"))
    )
    (net (code "258") (name "XOO") (class "Default")
      (node (ref "C2") (pin "P$1") (pinfunction "1_P$1") (pintype "passive"))
      (node (ref "U1") (pin "7") (pinfunction "XO_7") (pintype "output"))
      (node (ref "X1") (pin "3") (pinfunction "3_3") (pintype "bidirectional"))
    )
    (net (code "259") (name "XTAL1") (class "Default")
      (node (ref "C17") (pin "P$1") (pinfunction "1_P$1") (pintype "passive"))
      (node (ref "U3") (pin "23") (pinfunction "P2_13/XTAL_23") (pintype "bidirectional"))
      (node (ref "X2") (pin "1") (pinfunction "1_1") (pintype "bidirectional"))
    )
    (net (code "260") (name "XTAL2") (class "Default")
      (node (ref "C18") (pin "P$1") (pinfunction "1_P$1") (pintype "passive"))
      (node (ref "U3") (pin "24") (pinfunction "P2_12/EXTAL_24") (pintype "bidirectional"))
      (node (ref "X2") (pin "3") (pinfunction "3_3") (pintype "bidirectional"))
    )
    (net (code "261") (name "X_A_DIR") (class "Default")
      (node (ref "R39") (pin "1") (pinfunction "1_1") (pintype "passive"))
      (node (ref "U3") (pin "117") (pinfunction "P6_5_117") (pintype "bidirectional"))
    )
    (net (code "262") (name "X_A_ENABLE") (class "Default")
      (node (ref "R40") (pin "1") (pinfunction "1_1") (pintype "passive"))
      (node (ref "U3") (pin "116") (pinfunction "P6_6_116") (pintype "bidirectional"))
    )
    (net (code "263") (name "X_A_HLFB_OUT") (class "Default")
      (node (ref "J13") (pin "5") (pinfunction "5-HLFB-_5") (pintype "passive"))
    )
    (net (code "264") (name "X_A_MI_DIR") (class "Default")
      (node (ref "J13") (pin "7") (pinfunction "7-INPUT_A-_7") (pintype "passive"))
      (node (ref "R41") (pin "1") (pinfunction "1_1") (pintype "passive"))
      (node (ref "U11") (pin "3") (pinfunction "C(3)_3") (pintype "input"))
    )
    (net (code "265") (name "X_A_MI_ENABLE") (class "Default")
      (node (ref "J13") (pin "8") (pinfunction "8-ENABLE-_8") (pintype "passive"))
      (node (ref "R42") (pin "1") (pinfunction "1_1") (pintype "passive"))
      (node (ref "U12") (pin "3") (pinfunction "C(3)_3") (pintype "input"))
    )
    (net (code "266") (name "X_A_MI_STEP") (class "Default")
      (node (ref "J13") (pin "6") (pinfunction "6-INPUT_B-_6") (pintype "passive"))
      (node (ref "R37") (pin "1") (pinfunction "1_1") (pintype "passive"))
      (node (ref "U10") (pin "3") (pinfunction "C(3)_3") (pintype "input"))
    )
    (net (code "267") (name "X_A_STEP") (class "Default")
      (node (ref "R38") (pin "1") (pinfunction "1_1") (pintype "passive"))
      (node (ref "U3") (pin "118") (pinfunction "P6_4_118") (pintype "bidirectional"))
    )
    (net (code "268") (name "X_B_DIR") (class "Default")
      (node (ref "R45") (pin "1") (pinfunction "1_1") (pintype "passive"))
      (node (ref "U3") (pin "120") (pinfunction "P6_2_120") (pintype "bidirectional"))
    )
    (net (code "269") (name "X_B_ENABLE") (class "Default")
      (node (ref "R46") (pin "1") (pinfunction "1_1") (pintype "passive"))
      (node (ref "U3") (pin "119") (pinfunction "P6_3_119") (pintype "bidirectional"))
    )
    (net (code "270") (name "X_B_HLFB_OUT") (class "Default")
      (node (ref "J14") (pin "5") (pinfunction "5-HLFB-_5") (pintype "passive"))
    )
    (net (code "271") (name "X_B_MI_DIR") (class "Default")
      (node (ref "J14") (pin "7") (pinfunction "7-INPUT_A-_7") (pintype "passive"))
      (node (ref "R47") (pin "1") (pinfunction "1_1") (pintype "passive"))
      (node (ref "U14") (pin "3") (pinfunction "C(3)_3") (pintype "input"))
    )
    (net (code "272") (name "X_B_MI_ENABLE") (class "Default")
      (node (ref "J14") (pin "8") (pinfunction "8-ENABLE-_8") (pintype "passive"))
      (node (ref "R48") (pin "1") (pinfunction "1_1") (pintype "passive"))
      (node (ref "U15") (pin "3") (pinfunction "C(3)_3") (pintype "input"))
    )
    (net (code "273") (name "X_B_MI_STEP") (class "Default")
      (node (ref "J14") (pin "6") (pinfunction "6-INPUT_B-_6") (pintype "passive"))
      (node (ref "R43") (pin "1") (pinfunction "1_1") (pintype "passive"))
      (node (ref "U13") (pin "3") (pinfunction "C(3)_3") (pintype "input"))
    )
    (net (code "274") (name "X_B_STEP") (class "Default")
      (node (ref "R44") (pin "1") (pinfunction "1_1") (pintype "passive"))
      (node (ref "U3") (pin "121") (pinfunction "P6_1_121") (pintype "bidirectional"))
    )
    (net (code "275") (name "Y_A_DIR") (class "Default")
      (node (ref "R63") (pin "1") (pinfunction "1_1") (pintype "passive"))
      (node (ref "U3") (pin "114") (pinfunction "PA_0_114") (pintype "bidirectional"))
    )
    (net (code "276") (name "Y_A_ENABLE") (class "Default")
      (node (ref "R64") (pin "1") (pinfunction "1_1") (pintype "passive"))
      (node (ref "U3") (pin "113") (pinfunction "PA_1_113") (pintype "bidirectional"))
    )
    (net (code "277") (name "Y_A_HLFB_OUT") (class "Default")
      (node (ref "J17") (pin "5") (pinfunction "5-HLFB-_5") (pintype "passive"))
    )
    (net (code "278") (name "Y_A_MI_DIR") (class "Default")
      (node (ref "J17") (pin "7") (pinfunction "7-INPUT_A-_7") (pintype "passive"))
      (node (ref "R65") (pin "1") (pinfunction "1_1") (pintype "passive"))
      (node (ref "U23") (pin "3") (pinfunction "C(3)_3") (pintype "input"))
    )
    (net (code "279") (name "Y_A_MI_ENABLE") (class "Default")
      (node (ref "J17") (pin "8") (pinfunction "8-ENABLE-_8") (pintype "passive"))
      (node (ref "R66") (pin "1") (pinfunction "1_1") (pintype "passive"))
      (node (ref "U24") (pin "3") (pinfunction "C(3)_3") (pintype "input"))
    )
    (net (code "280") (name "Y_A_MI_STEP") (class "Default")
      (node (ref "J17") (pin "6") (pinfunction "6-INPUT_B-_6") (pintype "passive"))
      (node (ref "R61") (pin "1") (pinfunction "1_1") (pintype "passive"))
      (node (ref "U22") (pin "3") (pinfunction "C(3)_3") (pintype "input"))
    )
    (net (code "281") (name "Y_A_STEP") (class "Default")
      (node (ref "R62") (pin "1") (pinfunction "1_1") (pintype "passive"))
      (node (ref "U3") (pin "115") (pinfunction "P6_7_115") (pintype "bidirectional"))
    )
    (net (code "282") (name "Y_B_DIR") (class "Default")
      (node (ref "R69") (pin "1") (pinfunction "1_1") (pintype "passive"))
      (node (ref "U3") (pin "108") (pinfunction "PA_9_108") (pintype "bidirectional"))
    )
    (net (code "283") (name "Y_B_ENABLE") (class "Default")
      (node (ref "R70") (pin "1") (pinfunction "1_1") (pintype "passive"))
      (node (ref "U3") (pin "107") (pinfunction "PA_8_107") (pintype "bidirectional"))
    )
    (net (code "284") (name "Y_B_HLFB_OUT") (class "Default")
      (node (ref "J18") (pin "5") (pinfunction "5-HLFB-_5") (pintype "passive"))
    )
    (net (code "285") (name "Y_B_MI_DIR") (class "Default")
      (node (ref "J18") (pin "7") (pinfunction "7-INPUT_A-_7") (pintype "passive"))
      (node (ref "R71") (pin "1") (pinfunction "1_1") (pintype "passive"))
      (node (ref "U26") (pin "3") (pinfunction "C(3)_3") (pintype "input"))
    )
    (net (code "286") (name "Y_B_MI_ENABLE") (class "Default")
      (node (ref "J18") (pin "8") (pinfunction "8-ENABLE-_8") (pintype "passive"))
      (node (ref "R72") (pin "1") (pinfunction "1_1") (pintype "passive"))
      (node (ref "U27") (pin "3") (pinfunction "C(3)_3") (pintype "input"))
    )
    (net (code "287") (name "Y_B_MI_STEP") (class "Default")
      (node (ref "J18") (pin "6") (pinfunction "6-INPUT_B-_6") (pintype "passive"))
      (node (ref "R67") (pin "1") (pinfunction "1_1") (pintype "passive"))
      (node (ref "U25") (pin "3") (pinfunction "C(3)_3") (pintype "input"))
    )
    (net (code "288") (name "Y_B_STEP") (class "Default")
      (node (ref "R68") (pin "1") (pinfunction "1_1") (pintype "passive"))
      (node (ref "U3") (pin "109") (pinfunction "PA_10_109") (pintype "bidirectional"))
    )
    (net (code "289") (name "Z_A_DIR") (class "Default")
      (node (ref "R87") (pin "1") (pinfunction "1_1") (pintype "passive"))
      (node (ref "U3") (pin "105") (pinfunction "P6_14_105") (pintype "bidirectional"))
    )
    (net (code "290") (name "Z_A_ENABLE") (class "Default")
      (node (ref "R88") (pin "1") (pinfunction "1_1") (pintype "passive"))
      (node (ref "U3") (pin "104") (pinfunction "P6_13_104") (pintype "bidirectional"))
    )
    (net (code "291") (name "Z_A_HLFB_OUT") (class "Default")
      (node (ref "J21") (pin "5") (pinfunction "5-HLFB-_5") (pintype "passive"))
    )
    (net (code "292") (name "Z_A_MI_DIR") (class "Default")
      (node (ref "J21") (pin "7") (pinfunction "7-INPUT_A-_7") (pintype "passive"))
      (node (ref "R89") (pin "1") (pinfunction "1_1") (pintype "passive"))
      (node (ref "U35") (pin "3") (pinfunction "C(3)_3") (pintype "input"))
    )
    (net (code "293") (name "Z_A_MI_ENABLE") (class "Default")
      (node (ref "J21") (pin "8") (pinfunction "8-ENABLE-_8") (pintype "passive"))
      (node (ref "R90") (pin "1") (pinfunction "1_1") (pintype "passive"))
      (node (ref "U36") (pin "3") (pinfunction "C(3)_3") (pintype "input"))
    )
    (net (code "294") (name "Z_A_MI_STEP") (class "Default")
      (node (ref "J21") (pin "6") (pinfunction "6-INPUT_B-_6") (pintype "passive"))
      (node (ref "R85") (pin "1") (pinfunction "1_1") (pintype "passive"))
      (node (ref "U34") (pin "3") (pinfunction "C(3)_3") (pintype "input"))
    )
    (net (code "295") (name "Z_A_STEP") (class "Default")
      (node (ref "R86") (pin "1") (pinfunction "1_1") (pintype "passive"))
      (node (ref "U3") (pin "106") (pinfunction "P6_15_106") (pintype "bidirectional"))
    )
    (net (code "296") (name "Z_B_DIR") (class "Default")
      (node (ref "R93") (pin "1") (pinfunction "1_1") (pintype "passive"))
      (node (ref "U3") (pin "102") (pinfunction "P6_11_102") (pintype "bidirectional"))
    )
    (net (code "297") (name "Z_B_ENABLE") (class "Default")
      (node (ref "R94") (pin "1") (pinfunction "1_1") (pintype "passive"))
      (node (ref "U3") (pin "101") (pinfunction "P6_10_101") (pintype "bidirectional"))
    )
    (net (code "298") (name "Z_B_HLFB_OUT") (class "Default")
      (node (ref "J22") (pin "5") (pinfunction "5-HLFB-_5") (pintype "passive"))
    )
    (net (code "299") (name "Z_B_MI_DIR") (class "Default")
      (node (ref "J22") (pin "7") (pinfunction "7-INPUT_A-_7") (pintype "passive"))
      (node (ref "R95") (pin "1") (pinfunction "1_1") (pintype "passive"))
      (node (ref "U38") (pin "3") (pinfunction "C(3)_3") (pintype "input"))
    )
    (net (code "300") (name "Z_B_MI_ENABLE") (class "Default")
      (node (ref "J22") (pin "8") (pinfunction "8-ENABLE-_8") (pintype "passive"))
      (node (ref "R96") (pin "1") (pinfunction "1_1") (pintype "passive"))
      (node (ref "U39") (pin "3") (pinfunction "C(3)_3") (pintype "input"))
    )
    (net (code "301") (name "Z_B_MI_STEP") (class "Default")
      (node (ref "J22") (pin "6") (pinfunction "6-INPUT_B-_6") (pintype "passive"))
      (node (ref "R91") (pin "1") (pinfunction "1_1") (pintype "passive"))
      (node (ref "U37") (pin "3") (pinfunction "C(3)_3") (pintype "input"))
    )
    (net (code "302") (name "Z_B_STEP") (class "Default")
      (node (ref "R92") (pin "1") (pinfunction "1_1") (pintype "passive"))
      (node (ref "U3") (pin "103") (pinfunction "P6_12_103") (pintype "bidirectional"))
    )
    (net (code "303") (name "unconnected-(U3-VBAT-Pad18)") (class "Default")
      (node (ref "U3") (pin "18") (pinfunction "VBAT_18") (pintype "bidirectional"))
    )
  )
)
